# Lisa_CPU_Card_-_EasyEDA.net
KiCad netlist of a schematic drawn in EasyEDA
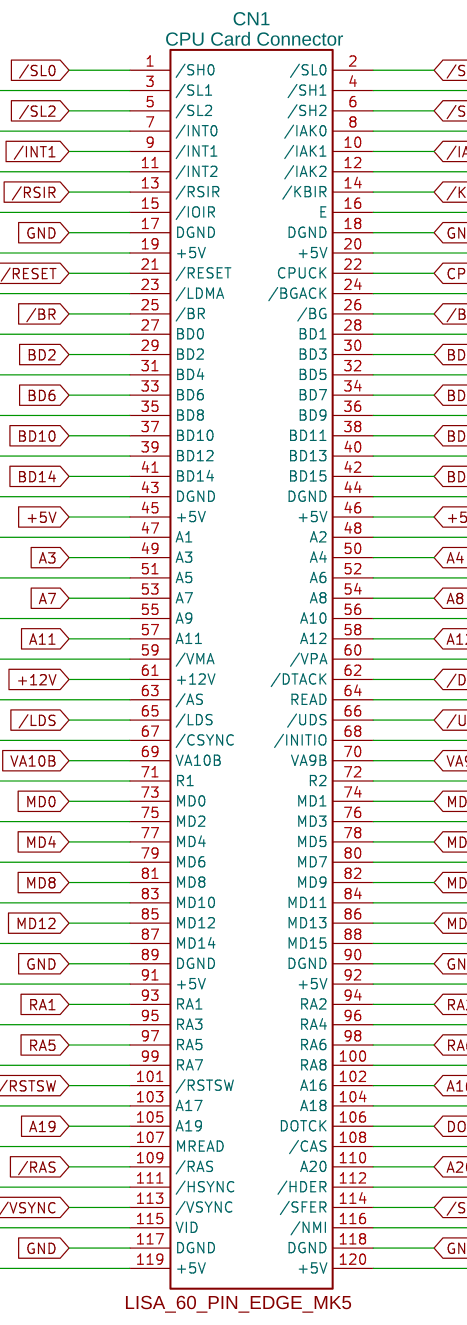
[diagram p0: CONNECTOR]
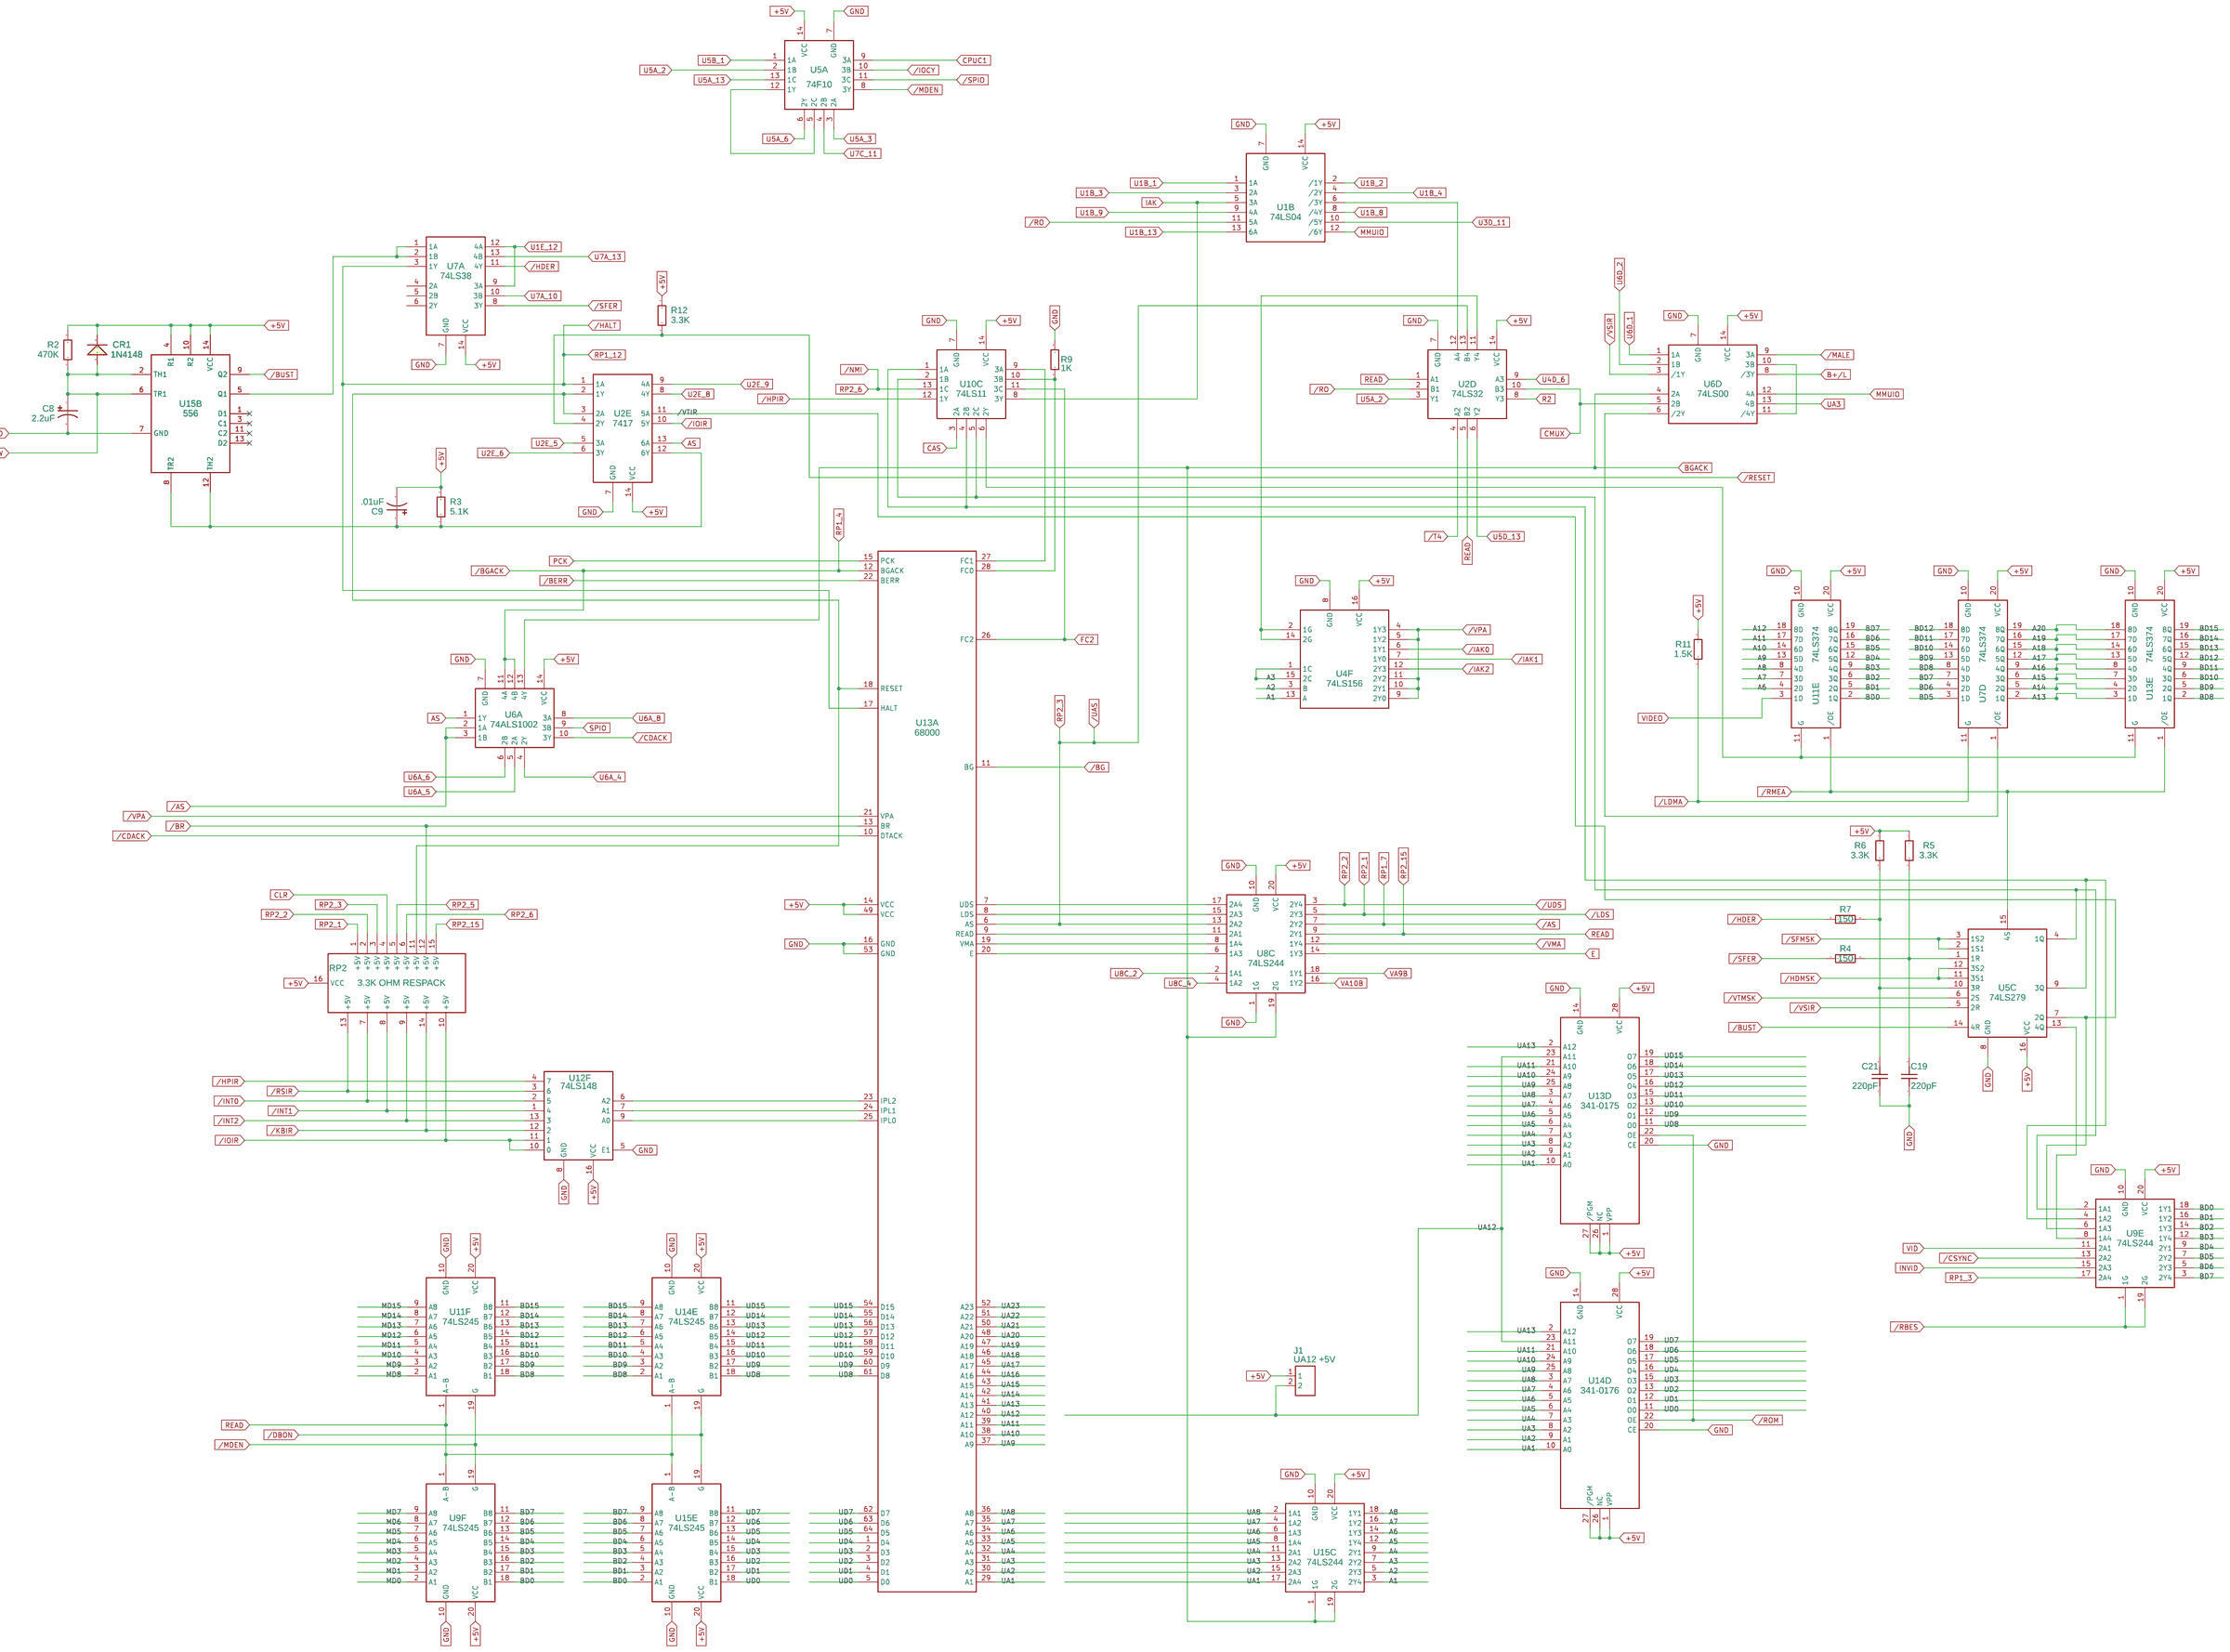
[diagram p1: CPU]
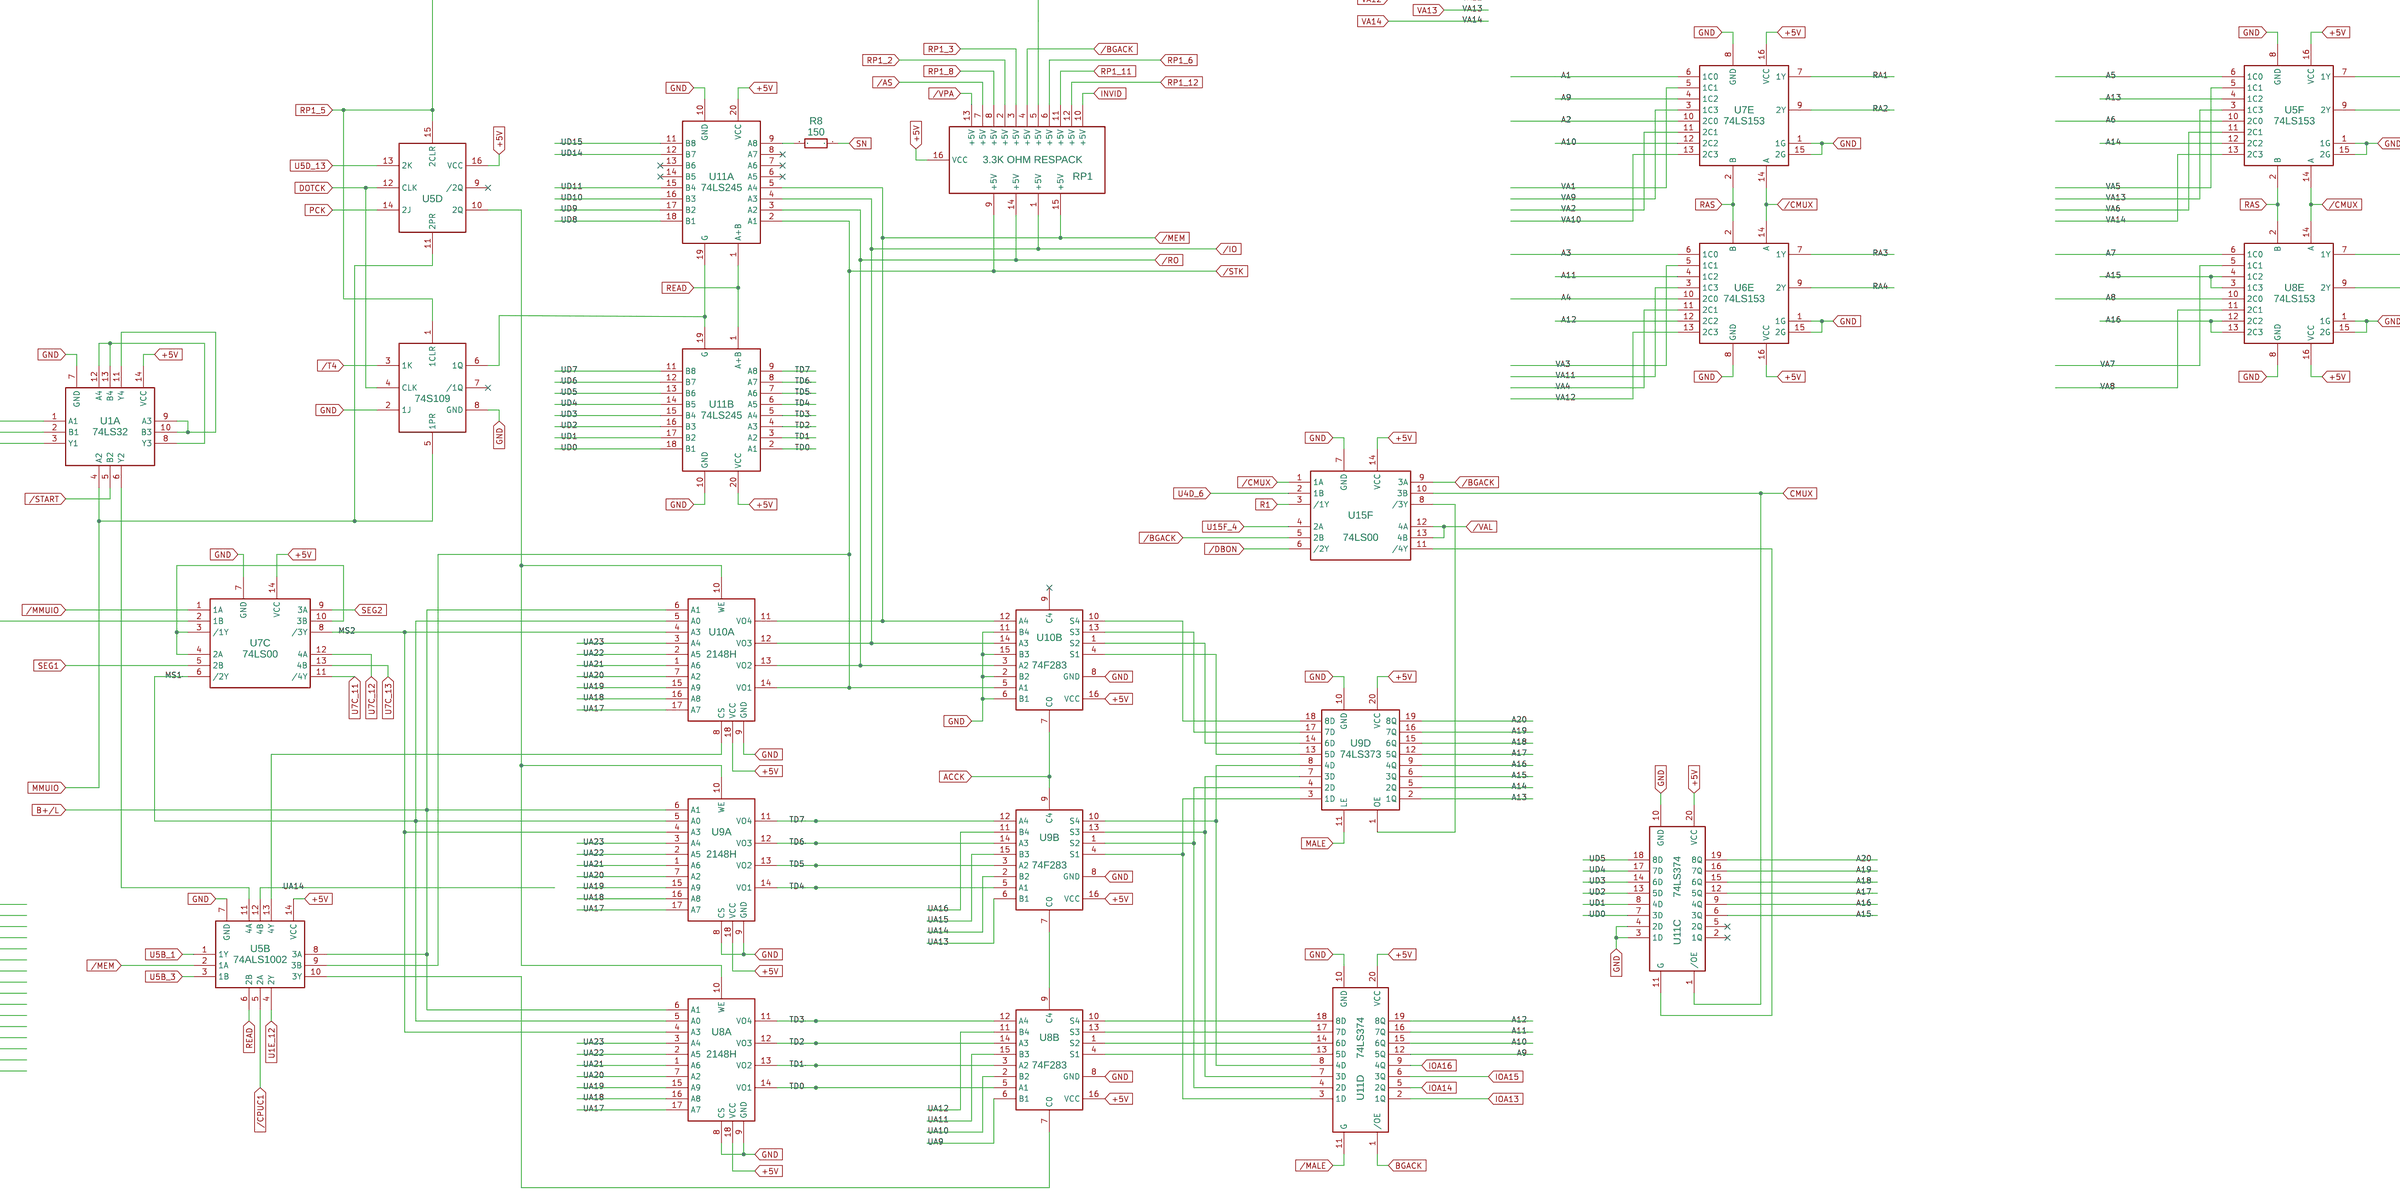
[diagram p2: MMU]
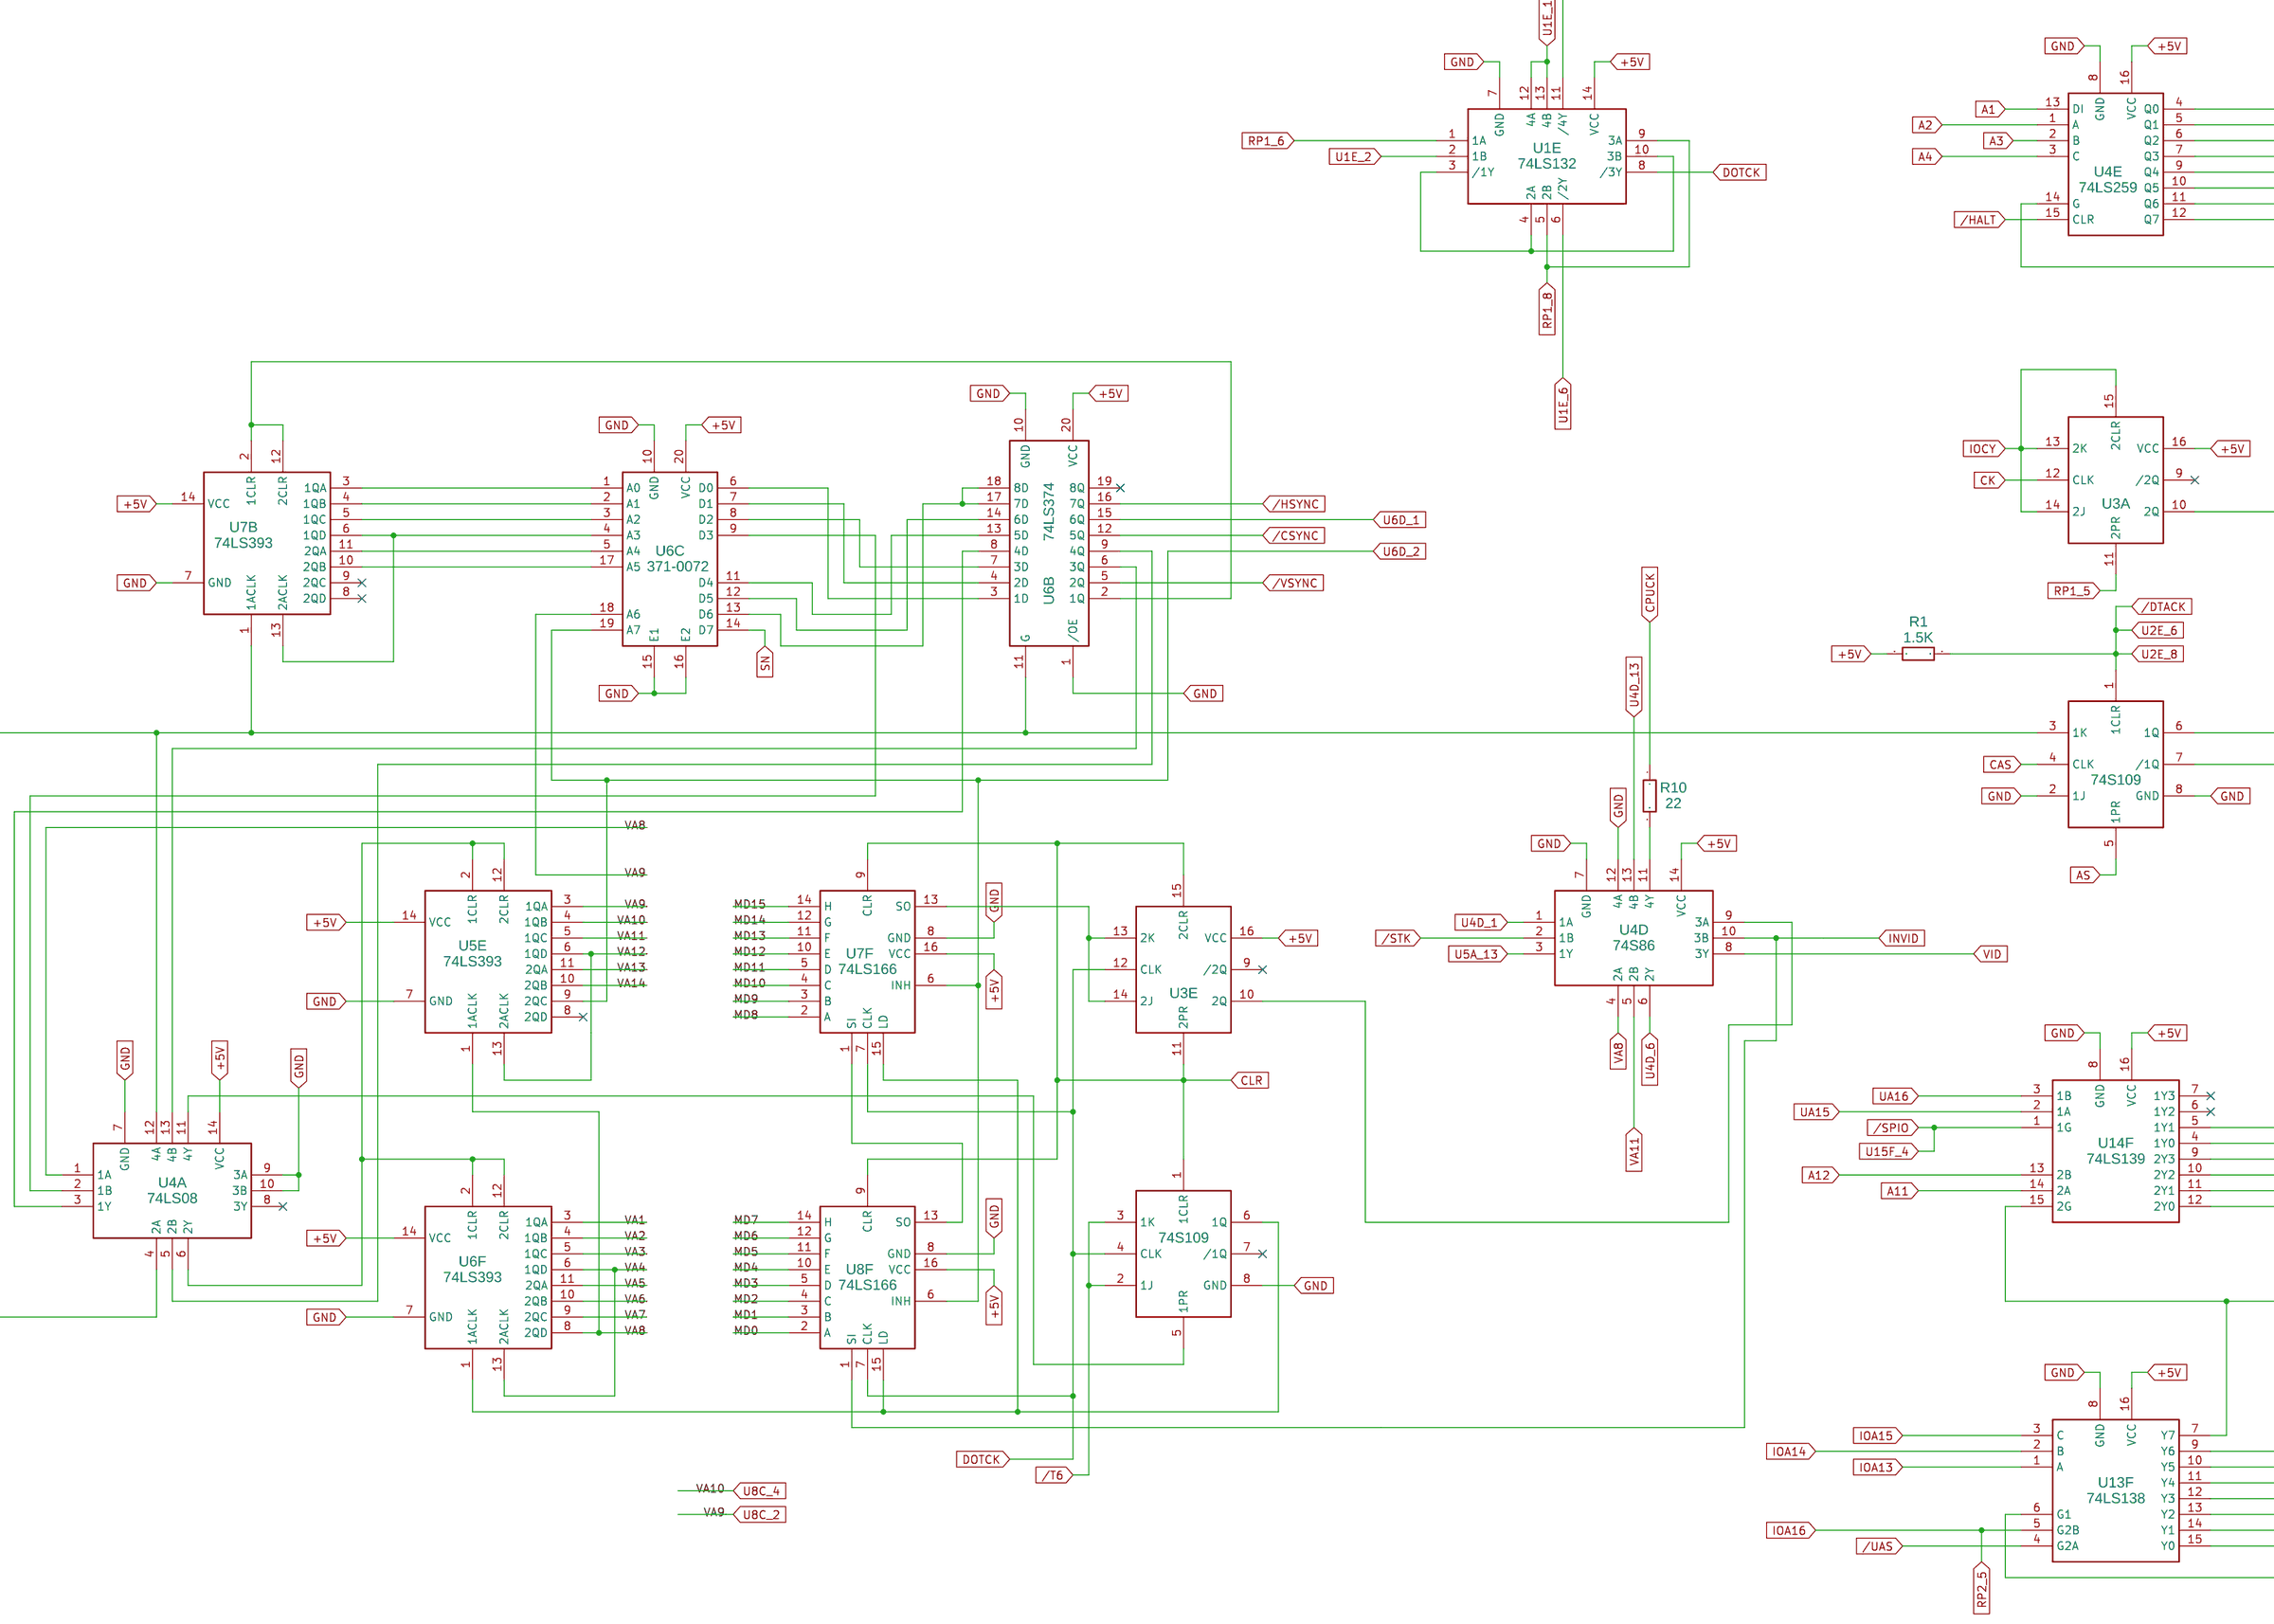
[diagram p3: VIDEO]
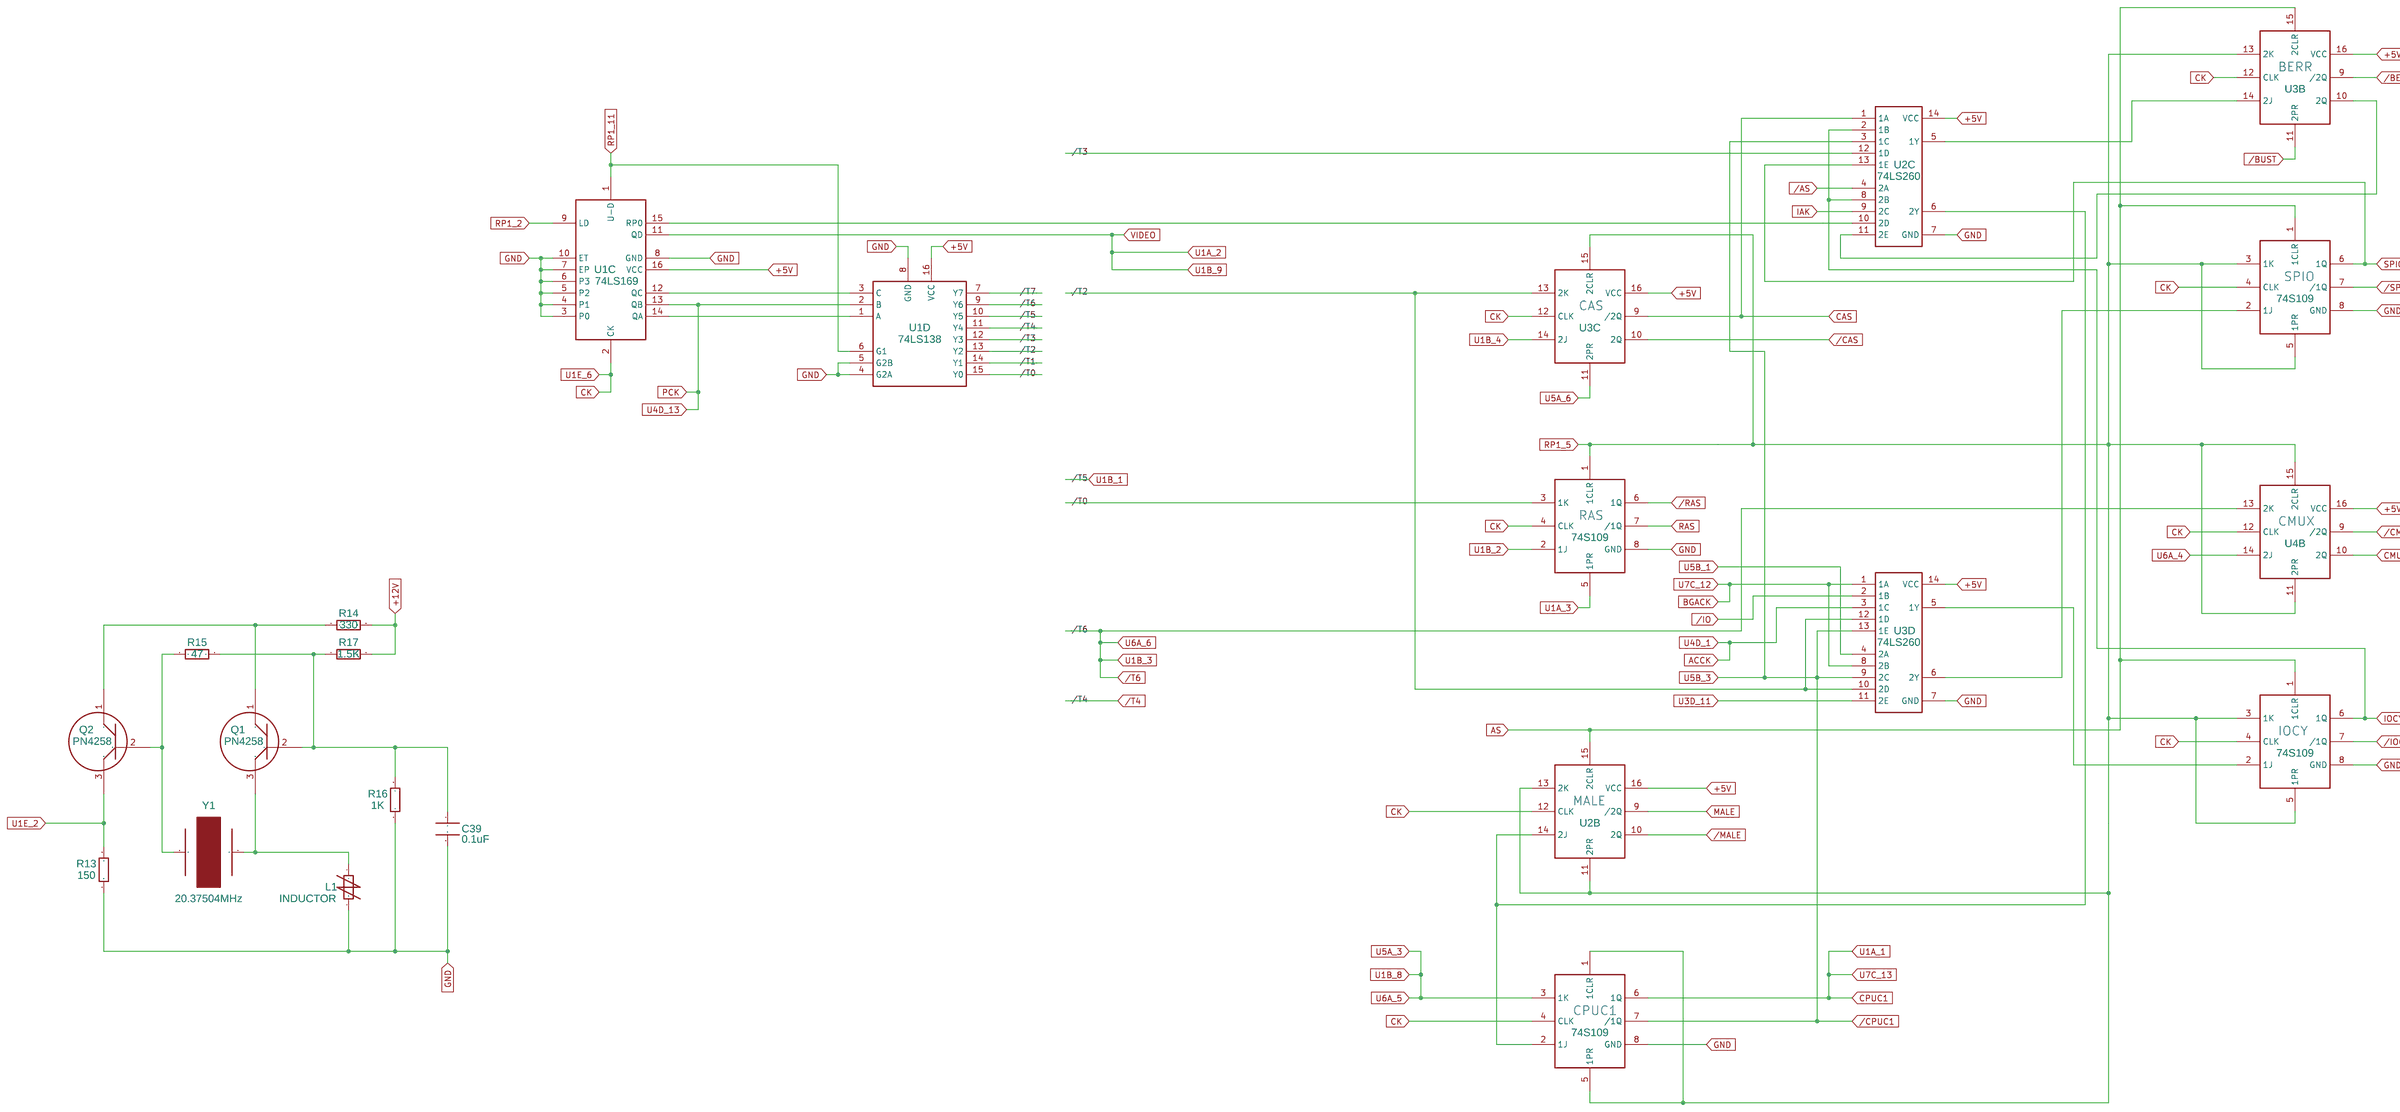
[diagram p4: CLOCK+IO]
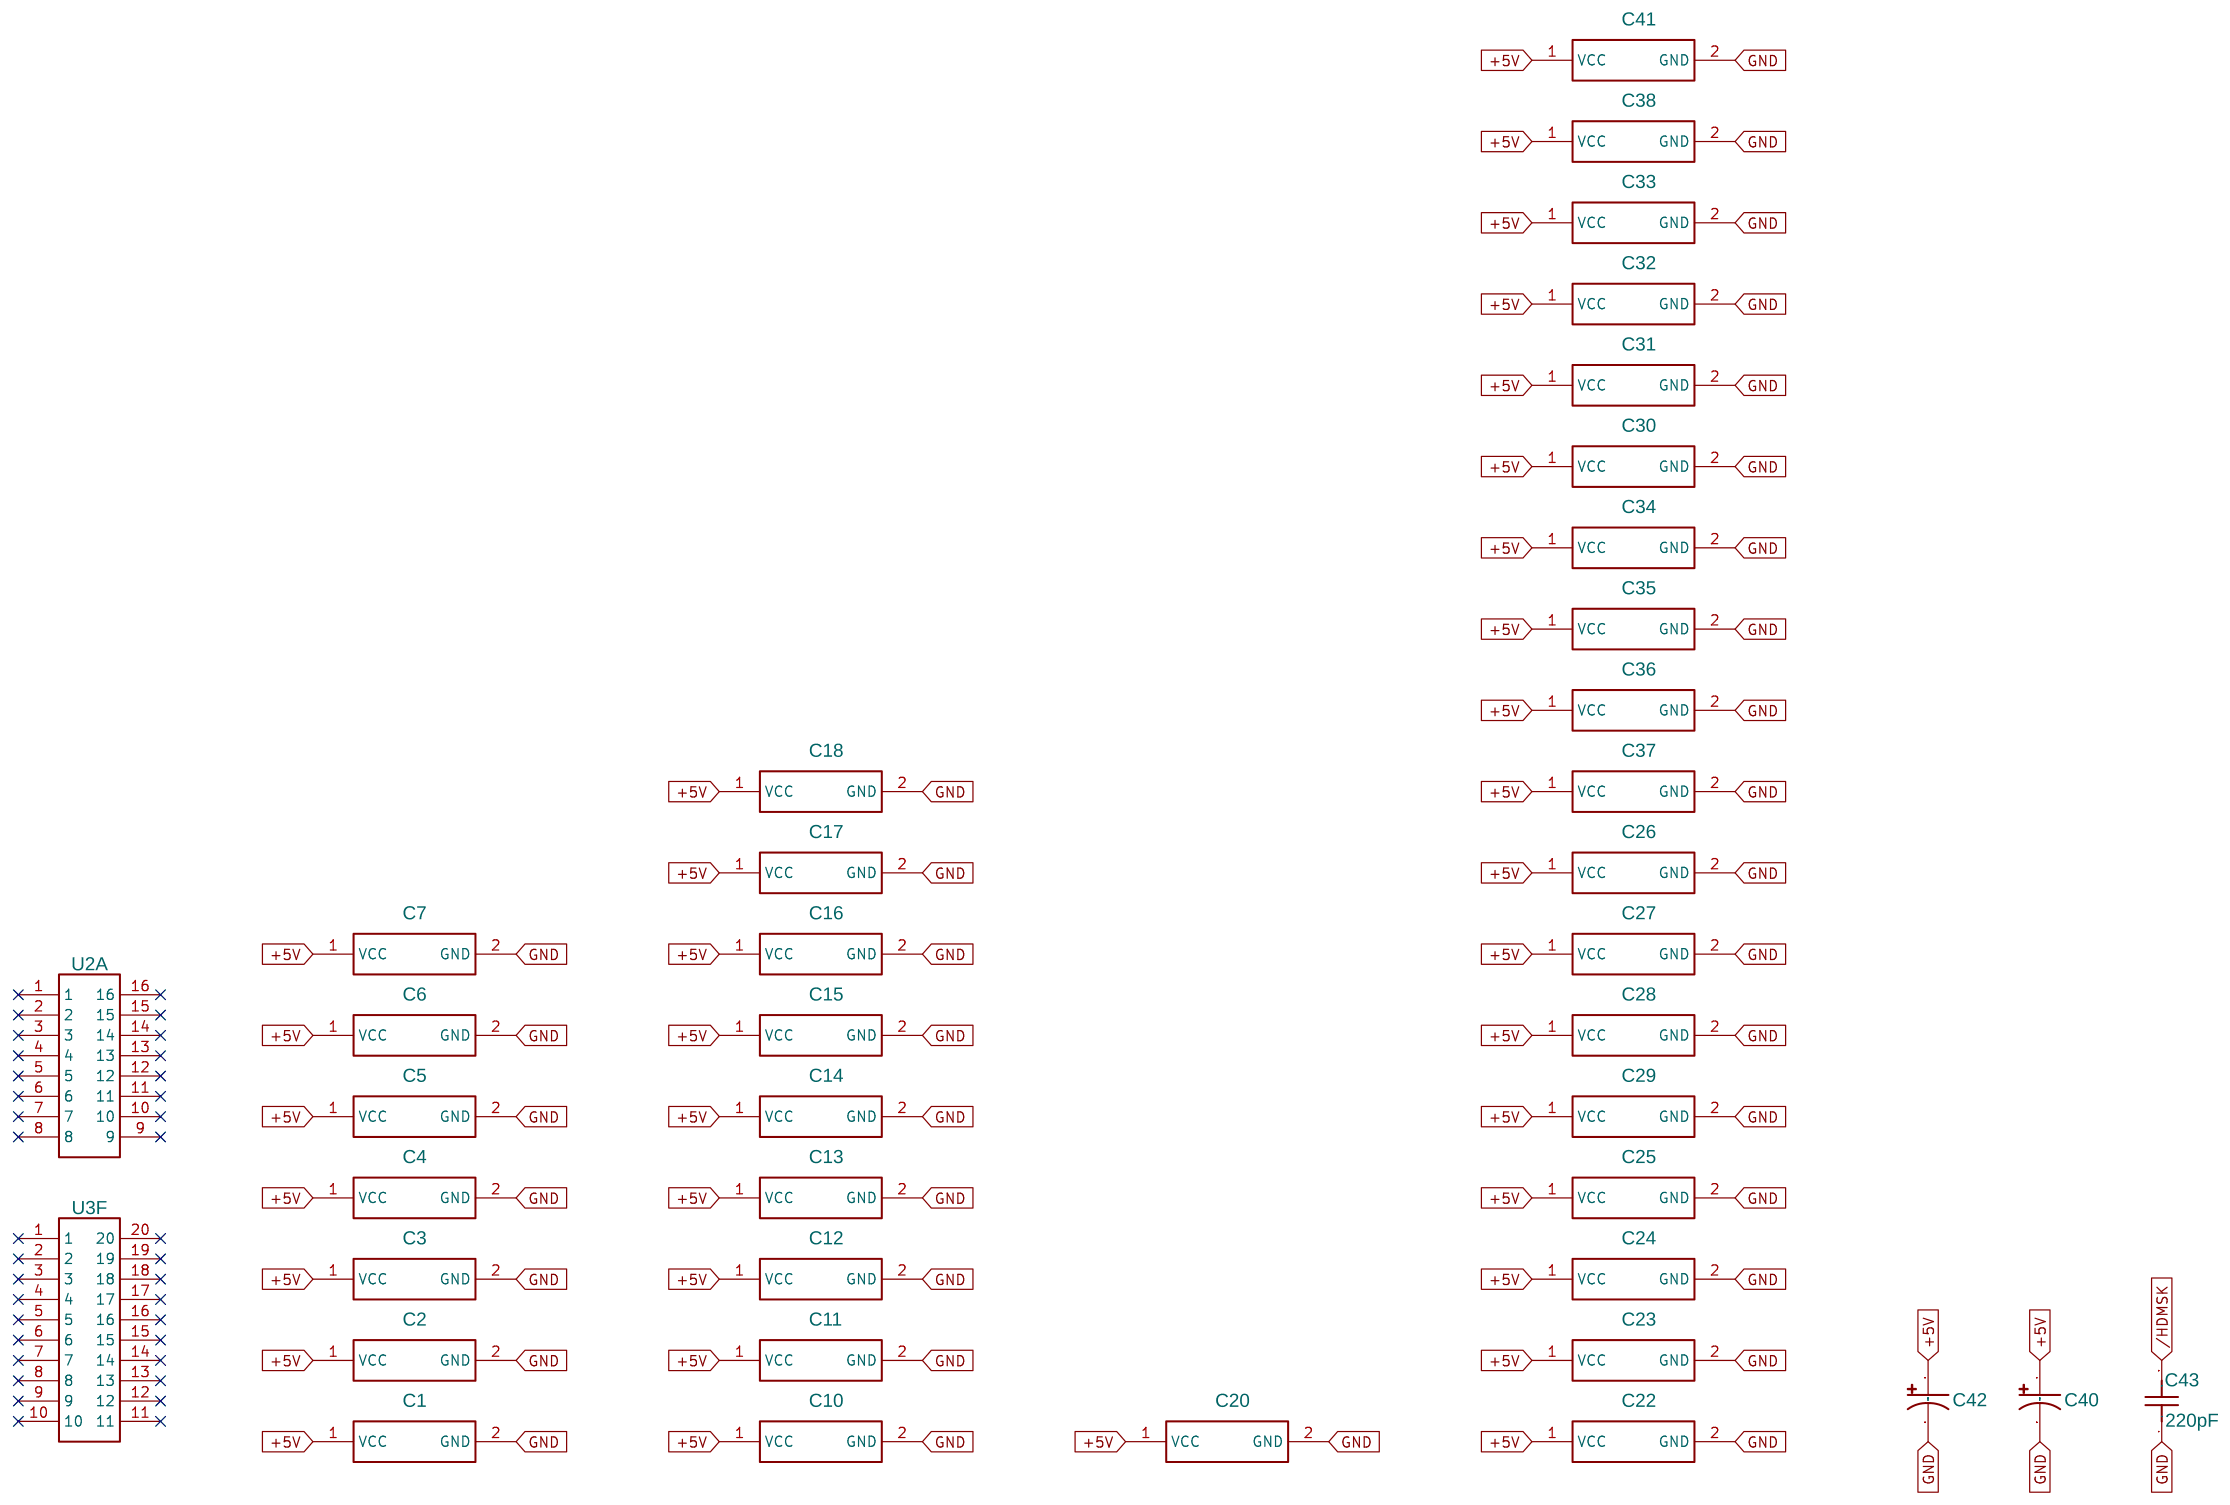
[diagram p5: MISC]

(export (version "E")
  (design (tool "Eeschema 10.0.6"))
  (components
    (comp (ref "CN1") (value "CPU Card Connector") (libsource (lib "") (part "Lisa CPU Connector")))
    (comp (ref "C8") (value "2.2uF") (libsource (lib "") (part "LISA_CPU_AXIAL_CAP_1")))
    (comp (ref "C9") (value ".01uF") (libsource (lib "") (part "LISA_CPU_AXIAL_CAP")))
    (comp (ref "C19") (value "220pF") (libsource (lib "") (part "LISA_CPU_CERAMIC_CAP")))
    (comp (ref "C21") (value "220pF") (libsource (lib "") (part "LISA_CPU_CERAMIC_CAP")))
    (comp (ref "CR1") (value "1N4148") (libsource (lib "") (part "LISA_CPU_DIODE")))
    (comp (ref "J1")
      (value "UA12 +5V")
      (fields (field (name "BOM_Manufacturer Part") "Jumper2") (field (name "BOM_Supplier Part") "C2940092"))
      (libsource (lib "") (part "JUMPER2"))
    )
    (comp (ref "R2") (value "470K") (libsource (lib "") (part "LISA_CPU_RESISTOR_1")))
    (comp (ref "R3") (value "5.1K") (libsource (lib "") (part "LISA_CPU_RESISTOR_1")))
    (comp (ref "R4") (value "150") (libsource (lib "") (part "LISA_CPU_RESISTOR_2")))
    (comp (ref "R5") (value "3.3K") (libsource (lib "") (part "LISA_CPU_RESISTOR")))
    (comp (ref "R6") (value "3.3K") (libsource (lib "") (part "LISA_CPU_RESISTOR")))
    (comp (ref "R7") (value "150") (libsource (lib "") (part "LISA_CPU_RESISTOR_2")))
    (comp (ref "R9") (value "1K") (libsource (lib "") (part "LISA_CPU_RESISTOR")))
    (comp (ref "R11") (value "1.5K") (libsource (lib "") (part "LISA_CPU_RESISTOR")))
    (comp (ref "R12") (value "3.3K") (libsource (lib "") (part "LISA_CPU_RESISTOR_1")))
    (comp (ref "RP2") (value "3.3K OHM RESPACK") (libsource (lib "") (part "LISA_CPU_RP2")))
    (comp (ref "U1B") (value "74LS04") (libsource (lib "") (part "LISA_CPU_74LS04")))
    (comp (ref "U2D") (value "74LS32") (libsource (lib "") (part "LISA_CPU_74LS32")))
    (comp (ref "U2E") (value "7417") (libsource (lib "") (part "LISA_CPU_7417")))
    (comp (ref "U4F") (value "74LS156") (libsource (lib "") (part "LISA_CPU_74LS156")))
    (comp (ref "U5A") (value "74F10") (libsource (lib "") (part "LISA_CPU_74F10")))
    (comp (ref "U5C") (value "74LS279") (libsource (lib "") (part "LISA_CPU_74LS279")))
    (comp (ref "U6A") (value "74ALS1002") (libsource (lib "") (part "LISA_CPU_74ALS1002")))
    (comp (ref "U6D") (value "74LS00") (libsource (lib "") (part "LISA_CPU_74LS00")))
    (comp (ref "U7A") (value "74LS38") (libsource (lib "") (part "LISA_CPU_74LS38")))
    (comp (ref "U7D") (value "74LS374") (libsource (lib "") (part "LISA_CPU_74LS374_1")))
    (comp (ref "U8C") (value "74LS244") (libsource (lib "") (part "LISA_CPU_74LS244_CTL")))
    (comp (ref "U9E") (value "74LS244") (libsource (lib "") (part "LISA_CPU_74LS244")))
    (comp (ref "U9F") (value "74LS245") (libsource (lib "") (part "LISA_CPU_74LS245_LOWER")))
    (comp (ref "U10C") (value "74LS11") (libsource (lib "") (part "LISA_CPU_74LS11")))
    (comp (ref "U11E") (value "74LS374") (libsource (lib "") (part "LISA_CPU_74LS374_2")))
    (comp (ref "U11F") (value "74LS245") (libsource (lib "") (part "LISA_CPU_74LS245_UPPER_1")))
    (comp (ref "U12F") (value "74LS148") (libsource (lib "") (part "LISA_CPU_74LS148")))
    (comp (ref "U13A") (value "68000") (libsource (lib "") (part "68000 (LISA)")))
    (comp (ref "U13D") (value "341-0175") (libsource (lib "") (part "LISA_CPU_EPROM")))
    (comp (ref "U13E") (value "74LS374") (libsource (lib "") (part "LISA_CPU_74LS374")))
    (comp (ref "U14D") (value "341-0176") (libsource (lib "") (part "LISA_CPU_EPROM_1")))
    (comp (ref "U14E") (value "74LS245") (libsource (lib "") (part "LISA_CPU_74LS245_UPPER")))
    (comp (ref "U15B") (value "556") (libsource (lib "") (part "LISA_CPU_556")))
    (comp (ref "U15C") (value "74LS244") (libsource (lib "") (part "LISA_CPU_74LS244_1")))
    (comp (ref "U15E") (value "74LS245") (libsource (lib "") (part "LISA_CPU_74LS245_LOWER_1")))
    (comp (ref "R8") (value "150") (libsource (lib "") (part "LISA_CPU_RESISTOR")))
    (comp (ref "RP1") (value "3.3K OHM RESPACK") (libsource (lib "") (part "LISA_CPU_RP1")))
    (comp (ref "U1A") (value "74LS32") (libsource (lib "") (part "LISA_CPU_74LS32")))
    (comp (ref "U5B") (value "74ALS1002") (libsource (lib "") (part "LISA_CPU_74ALS1002")))
    (comp (ref "U5D") (value "74S109") (libsource (lib "") (part "LISA_CPU_74S109")))
    (comp (ref "U5F") (value "74LS153") (libsource (lib "") (part "LISA_CPU_74LS153_UPPER")))
    (comp (ref "U6E") (value "74LS153") (libsource (lib "") (part "LISA_CPU_74LS153_LOWER_1")))
    (comp (ref "U7C") (value "74LS00") (libsource (lib "") (part "LISA_CPU_74LS00")))
    (comp (ref "U7E") (value "74LS153") (libsource (lib "") (part "LISA_CPU_74LS153_UPPER_1")))
    (comp (ref "U8A") (value "2148H") (libsource (lib "") (part "LISA_CPU_2148H")))
    (comp (ref "U8B") (value "74F283") (libsource (lib "") (part "LISA_CPU_74F283_1")))
    (comp (ref "U8E") (value "74LS153") (libsource (lib "") (part "LISA_CPU_74LS153_LOWER")))
    (comp (ref "U9A") (value "2148H") (libsource (lib "") (part "LISA_CPU_2148H_1")))
    (comp (ref "U9B") (value "74F283") (libsource (lib "") (part "LISA_CPU_74F283")))
    (comp (ref "U9D") (value "74LS373") (libsource (lib "") (part "LISA_CPU_74LS373")))
    (comp (ref "U10A") (value "2148H") (libsource (lib "") (part "LISA_CPU_2148H_2")))
    (comp (ref "U10B") (value "74F283") (libsource (lib "") (part "LISA_CPU_74F283_2")))
    (comp (ref "U11A") (value "74LS245") (libsource (lib "") (part "LISA_CPU_74LS245_U11A")))
    (comp (ref "U11B") (value "74LS245") (libsource (lib "") (part "LISA_CPU_74LS245_U11B")))
    (comp (ref "U11C") (value "74LS374") (libsource (lib "") (part "LISA_CPU_74LS374_1")))
    (comp (ref "U11D") (value "74LS374") (libsource (lib "") (part "LISA_CPU_74LS374")))
    (comp (ref "U15F") (value "74LS00") (libsource (lib "") (part "LISA_CPU_74LS00_1")))
    (comp (ref "R1") (value "1.5K") (libsource (lib "") (part "LISA_CPU_RESISTOR")))
    (comp (ref "R10") (value "22") (libsource (lib "") (part "LISA_CPU_RESISTOR_1")))
    (comp (ref "U1E") (value "74LS132") (libsource (lib "") (part "LISA_CPU_74LS132")))
    (comp (ref "U3A") (value "74S109") (libsource (lib "") (part "LISA_CPU_74S109_1")))
    (comp (ref "U3E") (value "74S109") (libsource (lib "") (part "LISA_CPU_74S109")))
    (comp (ref "U4A") (value "74LS08") (libsource (lib "") (part "LISA_CPU_74LS08")))
    (comp (ref "U4D") (value "74S86") (libsource (lib "") (part "LISA_CPU_74S86")))
    (comp (ref "U4E") (value "74LS259") (libsource (lib "") (part "LISA_CPU_74LS259")))
    (comp (ref "U5E") (value "74LS393") (libsource (lib "") (part "LISA_CPU_74LS393_2")))
    (comp (ref "U6B") (value "74LS374") (libsource (lib "") (part "LISA_CPU_74LS374")))
    (comp (ref "U6C") (value "371-0072") (libsource (lib "") (part "LISA_CPU_371-0072_VIDEO_ROM")))
    (comp (ref "U6F") (value "74LS393") (libsource (lib "") (part "LISA_CPU_74LS393_1")))
    (comp (ref "U7B") (value "74LS393") (libsource (lib "") (part "LISA_CPU_74LS393")))
    (comp (ref "U7F") (value "74LS166") (libsource (lib "") (part "LISA_CPU_74LS166_1")))
    (comp (ref "U8F") (value "74LS166") (libsource (lib "") (part "LISA_CPU_74LS166")))
    (comp (ref "U13F") (value "74LS138") (libsource (lib "") (part "LISA_CPU_74LS138")))
    (comp (ref "U14F") (value "74LS139") (libsource (lib "") (part "LISA_CPU_74LS139")))
    (comp (ref "C39") (value "0.1uF") (libsource (lib "") (part "LISA_CPU_GLASS_CAP")))
    (comp (ref "L1") (value "INDUCTOR") (libsource (lib "") (part "LISA_CPU_INDUCTOR")))
    (comp (ref "Q1") (value "PN4258") (libsource (lib "") (part "LISA_CPU_TRANSISTOR")))
    (comp (ref "Q2") (value "PN4258") (libsource (lib "") (part "LISA_CPU_TRANSISTOR")))
    (comp (ref "R13") (value "150") (libsource (lib "") (part "LISA_CPU_RESISTOR_1")))
    (comp (ref "R14") (value "330") (libsource (lib "") (part "LISA_CPU_RESISTOR")))
    (comp (ref "R15") (value "47") (libsource (lib "") (part "LISA_CPU_RESISTOR")))
    (comp (ref "R16") (value "1K") (libsource (lib "") (part "LISA_CPU_RESISTOR_1")))
    (comp (ref "R17") (value "1.5K") (libsource (lib "") (part "LISA_CPU_RESISTOR")))
    (comp (ref "U1C") (value "74LS169") (libsource (lib "") (part "LISA_CPU_74LS169")))
    (comp (ref "U1D") (value "74LS138") (libsource (lib "") (part "LISA_CPU_74LS138")))
    (comp (ref "U2B") (value "74S109") (libsource (lib "") (part "LISA_CPU_74S109_3")))
    (comp (ref "U2C") (value "74LS260") (libsource (lib "") (part "LISA_CPU_74LS260_1")))
    (comp (ref "U3B") (value "74S109") (libsource (lib "") (part "LISA_CPU_74S109_1")))
    (comp (ref "U3C") (value "74S109") (libsource (lib "") (part "LISA_CPU_74S109")))
    (comp (ref "U3D") (value "74LS260") (libsource (lib "") (part "LISA_CPU_74LS260")))
    (comp (ref "U4B") (value "74S109") (libsource (lib "") (part "LISA_CPU_74S109_2")))
    (comp (ref "Y1") (value "20.37504MHz") (libsource (lib "") (part "LISA_CPU_XTAL")))
    (comp (ref "C1")
      (value "LISA_CPU_DECOUPLER_CERAMIC_CAP")
      (libsource (lib "") (part "LISA_CPU_DECOUPLER_CERAMIC_CAP"))
    )
    (comp (ref "C2")
      (value "LISA_CPU_DECOUPLER_CERAMIC_CAP")
      (libsource (lib "") (part "LISA_CPU_DECOUPLER_CERAMIC_CAP"))
    )
    (comp (ref "C3")
      (value "LISA_CPU_DECOUPLER_CERAMIC_CAP")
      (libsource (lib "") (part "LISA_CPU_DECOUPLER_CERAMIC_CAP"))
    )
    (comp (ref "C4")
      (value "LISA_CPU_DECOUPLER_CERAMIC_CAP")
      (libsource (lib "") (part "LISA_CPU_DECOUPLER_CERAMIC_CAP"))
    )
    (comp (ref "C5")
      (value "LISA_CPU_DECOUPLER_CERAMIC_CAP")
      (libsource (lib "") (part "LISA_CPU_DECOUPLER_CERAMIC_CAP"))
    )
    (comp (ref "C6")
      (value "LISA_CPU_DECOUPLER_CERAMIC_CAP")
      (libsource (lib "") (part "LISA_CPU_DECOUPLER_CERAMIC_CAP"))
    )
    (comp (ref "C7")
      (value "LISA_CPU_DECOUPLER_CERAMIC_CAP")
      (libsource (lib "") (part "LISA_CPU_DECOUPLER_CERAMIC_CAP"))
    )
    (comp (ref "C10")
      (value "LISA_CPU_DECOUPLER_CERAMIC_CAP")
      (libsource (lib "") (part "LISA_CPU_DECOUPLER_CERAMIC_CAP"))
    )
    (comp (ref "C11")
      (value "LISA_CPU_DECOUPLER_CERAMIC_CAP")
      (libsource (lib "") (part "LISA_CPU_DECOUPLER_CERAMIC_CAP"))
    )
    (comp (ref "C12")
      (value "LISA_CPU_DECOUPLER_CERAMIC_CAP")
      (libsource (lib "") (part "LISA_CPU_DECOUPLER_CERAMIC_CAP"))
    )
    (comp (ref "C13")
      (value "LISA_CPU_DECOUPLER_CERAMIC_CAP")
      (libsource (lib "") (part "LISA_CPU_DECOUPLER_CERAMIC_CAP"))
    )
    (comp (ref "C14")
      (value "LISA_CPU_DECOUPLER_CERAMIC_CAP")
      (libsource (lib "") (part "LISA_CPU_DECOUPLER_CERAMIC_CAP"))
    )
    (comp (ref "C15")
      (value "LISA_CPU_DECOUPLER_CERAMIC_CAP")
      (libsource (lib "") (part "LISA_CPU_DECOUPLER_CERAMIC_CAP"))
    )
    (comp (ref "C16")
      (value "LISA_CPU_DECOUPLER_CERAMIC_CAP")
      (libsource (lib "") (part "LISA_CPU_DECOUPLER_CERAMIC_CAP"))
    )
    (comp (ref "C17")
      (value "LISA_CPU_DECOUPLER_CERAMIC_CAP")
      (libsource (lib "") (part "LISA_CPU_DECOUPLER_CERAMIC_CAP"))
    )
    (comp (ref "C18")
      (value "LISA_CPU_DECOUPLER_CERAMIC_CAP")
      (libsource (lib "") (part "LISA_CPU_DECOUPLER_CERAMIC_CAP"))
    )
    (comp (ref "C20")
      (value "LISA_CPU_DECOUPLER_CERAMIC_CAP")
      (libsource (lib "") (part "LISA_CPU_DECOUPLER_CERAMIC_CAP"))
    )
    (comp (ref "C22")
      (value "LISA_CPU_DECOUPLER_CERAMIC_CAP")
      (libsource (lib "") (part "LISA_CPU_DECOUPLER_CERAMIC_CAP"))
    )
    (comp (ref "C23")
      (value "LISA_CPU_DECOUPLER_CERAMIC_CAP")
      (libsource (lib "") (part "LISA_CPU_DECOUPLER_CERAMIC_CAP"))
    )
    (comp (ref "C24")
      (value "LISA_CPU_DECOUPLER_CERAMIC_CAP")
      (libsource (lib "") (part "LISA_CPU_DECOUPLER_CERAMIC_CAP"))
    )
    (comp (ref "C25")
      (value "LISA_CPU_DECOUPLER_CERAMIC_CAP")
      (libsource (lib "") (part "LISA_CPU_DECOUPLER_CERAMIC_CAP"))
    )
    (comp (ref "C26")
      (value "LISA_CPU_DECOUPLER_CERAMIC_CAP")
      (libsource (lib "") (part "LISA_CPU_DECOUPLER_CERAMIC_CAP"))
    )
    (comp (ref "C27")
      (value "LISA_CPU_DECOUPLER_CERAMIC_CAP")
      (libsource (lib "") (part "LISA_CPU_DECOUPLER_CERAMIC_CAP"))
    )
    (comp (ref "C28")
      (value "LISA_CPU_DECOUPLER_CERAMIC_CAP")
      (libsource (lib "") (part "LISA_CPU_DECOUPLER_CERAMIC_CAP"))
    )
    (comp (ref "C29")
      (value "LISA_CPU_DECOUPLER_CERAMIC_CAP")
      (libsource (lib "") (part "LISA_CPU_DECOUPLER_CERAMIC_CAP"))
    )
    (comp (ref "C30")
      (value "LISA_CPU_DECOUPLER_CERAMIC_CAP")
      (libsource (lib "") (part "LISA_CPU_DECOUPLER_CERAMIC_CAP"))
    )
    (comp (ref "C31")
      (value "LISA_CPU_DECOUPLER_CERAMIC_CAP")
      (libsource (lib "") (part "LISA_CPU_DECOUPLER_CERAMIC_CAP"))
    )
    (comp (ref "C32")
      (value "LISA_CPU_DECOUPLER_CERAMIC_CAP")
      (libsource (lib "") (part "LISA_CPU_DECOUPLER_CERAMIC_CAP"))
    )
    (comp (ref "C33")
      (value "LISA_CPU_DECOUPLER_CERAMIC_CAP")
      (libsource (lib "") (part "LISA_CPU_DECOUPLER_CERAMIC_CAP"))
    )
    (comp (ref "C34")
      (value "LISA_CPU_DECOUPLER_CERAMIC_CAP")
      (libsource (lib "") (part "LISA_CPU_DECOUPLER_CERAMIC_CAP"))
    )
    (comp (ref "C35")
      (value "LISA_CPU_DECOUPLER_CERAMIC_CAP")
      (libsource (lib "") (part "LISA_CPU_DECOUPLER_CERAMIC_CAP"))
    )
    (comp (ref "C36")
      (value "LISA_CPU_DECOUPLER_CERAMIC_CAP")
      (libsource (lib "") (part "LISA_CPU_DECOUPLER_CERAMIC_CAP"))
    )
    (comp (ref "C37")
      (value "LISA_CPU_DECOUPLER_CERAMIC_CAP")
      (libsource (lib "") (part "LISA_CPU_DECOUPLER_CERAMIC_CAP"))
    )
    (comp (ref "C38")
      (value "LISA_CPU_DECOUPLER_CERAMIC_CAP")
      (libsource (lib "") (part "LISA_CPU_DECOUPLER_CERAMIC_CAP"))
    )
    (comp (ref "C40") (value "LISA_CPU_AXIAL_CAP") (libsource (lib "") (part "LISA_CPU_AXIAL_CAP")))
    (comp (ref "C41")
      (value "LISA_CPU_DECOUPLER_CERAMIC_CAP")
      (libsource (lib "") (part "LISA_CPU_DECOUPLER_CERAMIC_CAP"))
    )
    (comp (ref "C42") (value "LISA_CPU_AXIAL_CAP") (libsource (lib "") (part "LISA_CPU_AXIAL_CAP")))
    (comp (ref "C43") (value "220pF") (libsource (lib "") (part "LISA_CPU_CERAMIC_CAP")))
    (comp (ref "U2A") (value "LISA_EMPTY_DIP_16") (libsource (lib "") (part "LISA_EMPTY_DIP_16")))
    (comp (ref "U3F") (value "LISA_EMPTY_DIP_20") (libsource (lib "") (part "LISA_EMPTY_DIP_20")))
  )
  (nets
    (net (code "1") (name "+5V") (class "Default")
      (node (ref "C1") (pin "1") (pinfunction "VCC_1") (pintype "unspecified"))
      (node (ref "C10") (pin "1") (pinfunction "VCC_1") (pintype "unspecified"))
      (node (ref "C11") (pin "1") (pinfunction "VCC_1") (pintype "unspecified"))
      (node (ref "C12") (pin "1") (pinfunction "VCC_1") (pintype "unspecified"))
      (node (ref "C13") (pin "1") (pinfunction "VCC_1") (pintype "unspecified"))
      (node (ref "C14") (pin "1") (pinfunction "VCC_1") (pintype "unspecified"))
      (node (ref "C15") (pin "1") (pinfunction "VCC_1") (pintype "unspecified"))
      (node (ref "C16") (pin "1") (pinfunction "VCC_1") (pintype "unspecified"))
      (node (ref "C17") (pin "1") (pinfunction "VCC_1") (pintype "unspecified"))
      (node (ref "C18") (pin "1") (pinfunction "VCC_1") (pintype "unspecified"))
      (node (ref "C2") (pin "1") (pinfunction "VCC_1") (pintype "unspecified"))
      (node (ref "C20") (pin "1") (pinfunction "VCC_1") (pintype "unspecified"))
      (node (ref "C22") (pin "1") (pinfunction "VCC_1") (pintype "unspecified"))
      (node (ref "C23") (pin "1") (pinfunction "VCC_1") (pintype "unspecified"))
      (node (ref "C24") (pin "1") (pinfunction "VCC_1") (pintype "unspecified"))
      (node (ref "C25") (pin "1") (pinfunction "VCC_1") (pintype "unspecified"))
      (node (ref "C26") (pin "1") (pinfunction "VCC_1") (pintype "unspecified"))
      (node (ref "C27") (pin "1") (pinfunction "VCC_1") (pintype "unspecified"))
      (node (ref "C28") (pin "1") (pinfunction "VCC_1") (pintype "unspecified"))
      (node (ref "C29") (pin "1") (pinfunction "VCC_1") (pintype "unspecified"))
      (node (ref "C3") (pin "1") (pinfunction "VCC_1") (pintype "unspecified"))
      (node (ref "C30") (pin "1") (pinfunction "VCC_1") (pintype "unspecified"))
      (node (ref "C31") (pin "1") (pinfunction "VCC_1") (pintype "unspecified"))
      (node (ref "C32") (pin "1") (pinfunction "VCC_1") (pintype "unspecified"))
      (node (ref "C33") (pin "1") (pinfunction "VCC_1") (pintype "unspecified"))
      (node (ref "C34") (pin "1") (pinfunction "VCC_1") (pintype "unspecified"))
      (node (ref "C35") (pin "1") (pinfunction "VCC_1") (pintype "unspecified"))
      (node (ref "C36") (pin "1") (pinfunction "VCC_1") (pintype "unspecified"))
      (node (ref "C37") (pin "1") (pinfunction "VCC_1") (pintype "unspecified"))
      (node (ref "C38") (pin "1") (pinfunction "VCC_1") (pintype "unspecified"))
      (node (ref "C4") (pin "1") (pinfunction "VCC_1") (pintype "unspecified"))
      (node (ref "C40") (pin "1") (pinfunction "1_1") (pintype "unspecified"))
      (node (ref "C41") (pin "1") (pinfunction "VCC_1") (pintype "unspecified"))
      (node (ref "C42") (pin "1") (pinfunction "1_1") (pintype "unspecified"))
      (node (ref "C5") (pin "1") (pinfunction "VCC_1") (pintype "unspecified"))
      (node (ref "C6") (pin "1") (pinfunction "VCC_1") (pintype "unspecified"))
      (node (ref "C7") (pin "1") (pinfunction "VCC_1") (pintype "unspecified"))
      (node (ref "C9") (pin "2") (pinfunction "2_2") (pintype "unspecified"))
      (node (ref "CN1") (pin "119") (pinfunction "+5V_119") (pintype "unspecified"))
      (node (ref "CN1") (pin "120") (pinfunction "+5V_120") (pintype "unspecified"))
      (node (ref "CN1") (pin "19") (pinfunction "+5V_19") (pintype "unspecified"))
      (node (ref "CN1") (pin "20") (pinfunction "+5V_20") (pintype "unspecified"))
      (node (ref "CN1") (pin "45") (pinfunction "+5V_45") (pintype "unspecified"))
      (node (ref "CN1") (pin "46") (pinfunction "+5V_46") (pintype "unspecified"))
      (node (ref "CN1") (pin "91") (pinfunction "+5V_91") (pintype "unspecified"))
      (node (ref "CN1") (pin "92") (pinfunction "+5V_92") (pintype "unspecified"))
      (node (ref "CR1") (pin "2") (pinfunction "2_2") (pintype "unspecified"))
      (node (ref "J1") (pin "1") (pinfunction "1_1") (pintype "unspecified"))
      (node (ref "R1") (pin "2") (pinfunction "2_2") (pintype "unspecified"))
      (node (ref "R11") (pin "1") (pinfunction "1_1") (pintype "unspecified"))
      (node (ref "R12") (pin "2") (pinfunction "2_2") (pintype "unspecified"))
      (node (ref "R2") (pin "2") (pinfunction "2_2") (pintype "unspecified"))
      (node (ref "R3") (pin "2") (pinfunction "2_2") (pintype "unspecified"))
      (node (ref "R5") (pin "1") (pinfunction "1_1") (pintype "unspecified"))
      (node (ref "R6") (pin "1") (pinfunction "1_1") (pintype "unspecified"))
      (node (ref "RP1") (pin "16") (pinfunction "VCC_16") (pintype "unspecified"))
      (node (ref "RP2") (pin "16") (pinfunction "VCC_16") (pintype "unspecified"))
      (node (ref "U10A") (pin "18") (pinfunction "VCC_18") (pintype "unspecified"))
      (node (ref "U10B") (pin "16") (pinfunction "VCC_16") (pintype "unspecified"))
      (node (ref "U10C") (pin "14") (pinfunction "VCC_14") (pintype "unspecified"))
      (node (ref "U11A") (pin "20") (pinfunction "VCC_20") (pintype "unspecified"))
      (node (ref "U11B") (pin "20") (pinfunction "VCC_20") (pintype "unspecified"))
      (node (ref "U11C") (pin "20") (pinfunction "VCC_20") (pintype "unspecified"))
      (node (ref "U11D") (pin "20") (pinfunction "VCC_20") (pintype "unspecified"))
      (node (ref "U11E") (pin "20") (pinfunction "VCC_20") (pintype "unspecified"))
      (node (ref "U11F") (pin "20") (pinfunction "VCC_20") (pintype "unspecified"))
      (node (ref "U12F") (pin "16") (pinfunction "VCC_16") (pintype "unspecified"))
      (node (ref "U13A") (pin "14") (pinfunction "VCC_14") (pintype "unspecified"))
      (node (ref "U13A") (pin "49") (pinfunction "VCC_49") (pintype "unspecified"))
      (node (ref "U13D") (pin "1") (pinfunction "VPP_1") (pintype "unspecified"))
      (node (ref "U13D") (pin "26") (pinfunction "NC_26") (pintype "unspecified"))
      (node (ref "U13D") (pin "27") (pinfunction "/PGM_27") (pintype "unspecified"))
      (node (ref "U13D") (pin "28") (pinfunction "VCC_28") (pintype "unspecified"))
      (node (ref "U13E") (pin "20") (pinfunction "VCC_20") (pintype "unspecified"))
      (node (ref "U13F") (pin "16") (pinfunction "VCC_16") (pintype "unspecified"))
      (node (ref "U14D") (pin "1") (pinfunction "VPP_1") (pintype "unspecified"))
      (node (ref "U14D") (pin "26") (pinfunction "NC_26") (pintype "unspecified"))
      (node (ref "U14D") (pin "27") (pinfunction "/PGM_27") (pintype "unspecified"))
      (node (ref "U14D") (pin "28") (pinfunction "VCC_28") (pintype "unspecified"))
      (node (ref "U14E") (pin "20") (pinfunction "VCC_20") (pintype "unspecified"))
      (node (ref "U14F") (pin "16") (pinfunction "VCC_16") (pintype "unspecified"))
      (node (ref "U15B") (pin "10") (pinfunction "R2_10") (pintype "unspecified"))
      (node (ref "U15B") (pin "14") (pinfunction "VCC_14") (pintype "unspecified"))
      (node (ref "U15B") (pin "4") (pinfunction "R1_4") (pintype "unspecified"))
      (node (ref "U15C") (pin "20") (pinfunction "VCC_20") (pintype "unspecified"))
      (node (ref "U15E") (pin "20") (pinfunction "VCC_20") (pintype "unspecified"))
      (node (ref "U15F") (pin "14") (pinfunction "VCC_14") (pintype "unspecified"))
      (node (ref "U1A") (pin "14") (pinfunction "VCC_14") (pintype "unspecified"))
      (node (ref "U1B") (pin "14") (pinfunction "VCC_14") (pintype "unspecified"))
      (node (ref "U1C") (pin "16") (pinfunction "VCC_16") (pintype "unspecified"))
      (node (ref "U1D") (pin "16") (pinfunction "VCC_16") (pintype "unspecified"))
      (node (ref "U1E") (pin "14") (pinfunction "VCC_14") (pintype "unspecified"))
      (node (ref "U2B") (pin "16") (pinfunction "VCC_16") (pintype "unspecified"))
      (node (ref "U2C") (pin "14") (pinfunction "VCC_14") (pintype "unspecified"))
      (node (ref "U2D") (pin "14") (pinfunction "VCC_14") (pintype "unspecified"))
      (node (ref "U2E") (pin "14") (pinfunction "VCC_14") (pintype "unspecified"))
      (node (ref "U3A") (pin "16") (pinfunction "VCC_16") (pintype "unspecified"))
      (node (ref "U3B") (pin "16") (pinfunction "VCC_16") (pintype "unspecified"))
      (node (ref "U3C") (pin "16") (pinfunction "VCC_16") (pintype "unspecified"))
      (node (ref "U3D") (pin "14") (pinfunction "VCC_14") (pintype "unspecified"))
      (node (ref "U3E") (pin "16") (pinfunction "VCC_16") (pintype "unspecified"))
      (node (ref "U4A") (pin "14") (pinfunction "VCC_14") (pintype "unspecified"))
      (node (ref "U4B") (pin "16") (pinfunction "VCC_16") (pintype "unspecified"))
      (node (ref "U4D") (pin "14") (pinfunction "VCC_14") (pintype "unspecified"))
      (node (ref "U4E") (pin "16") (pinfunction "VCC_16") (pintype "unspecified"))
      (node (ref "U4F") (pin "16") (pinfunction "VCC_16") (pintype "unspecified"))
      (node (ref "U5A") (pin "14") (pinfunction "VCC_14") (pintype "unspecified"))
      (node (ref "U5B") (pin "14") (pinfunction "VCC_14") (pintype "unspecified"))
      (node (ref "U5C") (pin "16") (pinfunction "VCC_16") (pintype "unspecified"))
      (node (ref "U5D") (pin "16") (pinfunction "VCC_16") (pintype "unspecified"))
      (node (ref "U5E") (pin "14") (pinfunction "VCC_14") (pintype "unspecified"))
      (node (ref "U5F") (pin "16") (pinfunction "VCC_16") (pintype "unspecified"))
      (node (ref "U6A") (pin "14") (pinfunction "VCC_14") (pintype "unspecified"))
      (node (ref "U6B") (pin "20") (pinfunction "VCC_20") (pintype "unspecified"))
      (node (ref "U6C") (pin "20") (pinfunction "VCC_20") (pintype "unspecified"))
      (node (ref "U6D") (pin "14") (pinfunction "VCC_14") (pintype "unspecified"))
      (node (ref "U6E") (pin "16") (pinfunction "VCC_16") (pintype "unspecified"))
      (node (ref "U6F") (pin "14") (pinfunction "VCC_14") (pintype "unspecified"))
      (node (ref "U7A") (pin "14") (pinfunction "VCC_14") (pintype "unspecified"))
      (node (ref "U7B") (pin "14") (pinfunction "VCC_14") (pintype "unspecified"))
      (node (ref "U7C") (pin "14") (pinfunction "VCC_14") (pintype "unspecified"))
      (node (ref "U7D") (pin "20") (pinfunction "VCC_20") (pintype "unspecified"))
      (node (ref "U7E") (pin "16") (pinfunction "VCC_16") (pintype "unspecified"))
      (node (ref "U7F") (pin "16") (pinfunction "VCC_16") (pintype "unspecified"))
      (node (ref "U8A") (pin "18") (pinfunction "VCC_18") (pintype "unspecified"))
      (node (ref "U8B") (pin "16") (pinfunction "VCC_16") (pintype "unspecified"))
      (node (ref "U8C") (pin "20") (pinfunction "VCC_20") (pintype "unspecified"))
      (node (ref "U8E") (pin "16") (pinfunction "VCC_16") (pintype "unspecified"))
      (node (ref "U8F") (pin "16") (pinfunction "VCC_16") (pintype "unspecified"))
      (node (ref "U9A") (pin "18") (pinfunction "VCC_18") (pintype "unspecified"))
      (node (ref "U9B") (pin "16") (pinfunction "VCC_16") (pintype "unspecified"))
      (node (ref "U9D") (pin "20") (pinfunction "VCC_20") (pintype "unspecified"))
      (node (ref "U9E") (pin "20") (pinfunction "VCC_20") (pintype "unspecified"))
      (node (ref "U9F") (pin "20") (pinfunction "VCC_20") (pintype "unspecified"))
    )
    (net (code "2") (name "+12V") (class "Default")
      (node (ref "CN1") (pin "61") (pinfunction "+12V_61") (pintype "unspecified"))
      (node (ref "R14") (pin "2") (pinfunction "2_2") (pintype "unspecified"))
      (node (ref "R17") (pin "2") (pinfunction "2_2") (pintype "unspecified"))
    )
    (net (code "3") (name "A1") (class "Default")
      (node (ref "CN1") (pin "47") (pinfunction "A1_47") (pintype "unspecified"))
      (node (ref "U15C") (pin "3") (pinfunction "2Y4_3") (pintype "unspecified"))
      (node (ref "U4E") (pin "13") (pinfunction "DI_13") (pintype "unspecified"))
      (node (ref "U4F") (pin "13") (pinfunction "A_13") (pintype "unspecified"))
      (node (ref "U7E") (pin "6") (pinfunction "1C0_6") (pintype "unspecified"))
    )
    (net (code "4") (name "A2") (class "Default")
      (node (ref "CN1") (pin "48") (pinfunction "A2_48") (pintype "unspecified"))
      (node (ref "U15C") (pin "5") (pinfunction "2Y3_5") (pintype "unspecified"))
      (node (ref "U4E") (pin "1") (pinfunction "A_1") (pintype "unspecified"))
      (node (ref "U4F") (pin "3") (pinfunction "B_3") (pintype "unspecified"))
      (node (ref "U7E") (pin "10") (pinfunction "2C0_10") (pintype "unspecified"))
    )
    (net (code "5") (name "A3") (class "Default")
      (node (ref "CN1") (pin "49") (pinfunction "A3_49") (pintype "unspecified"))
      (node (ref "U15C") (pin "7") (pinfunction "2Y2_7") (pintype "unspecified"))
      (node (ref "U4E") (pin "2") (pinfunction "B_2") (pintype "unspecified"))
      (node (ref "U4F") (pin "1") (pinfunction "1C_1") (pintype "unspecified"))
      (node (ref "U4F") (pin "15") (pinfunction "2C_15") (pintype "unspecified"))
      (node (ref "U6E") (pin "6") (pinfunction "1C0_6") (pintype "unspecified"))
    )
    (net (code "6") (name "A4") (class "Default")
      (node (ref "CN1") (pin "50") (pinfunction "A4_50") (pintype "unspecified"))
      (node (ref "U15C") (pin "9") (pinfunction "2Y1_9") (pintype "unspecified"))
      (node (ref "U4E") (pin "3") (pinfunction "C_3") (pintype "unspecified"))
      (node (ref "U6E") (pin "10") (pinfunction "2C0_10") (pintype "unspecified"))
    )
    (net (code "7") (name "A5") (class "Default")
      (node (ref "CN1") (pin "51") (pinfunction "A5_51") (pintype "unspecified"))
      (node (ref "U15C") (pin "12") (pinfunction "1Y4_12") (pintype "unspecified"))
      (node (ref "U5F") (pin "6") (pinfunction "1C0_6") (pintype "unspecified"))
    )
    (net (code "8") (name "A6") (class "Default")
      (node (ref "CN1") (pin "52") (pinfunction "A6_52") (pintype "unspecified"))
      (node (ref "U11E") (pin "4") (pinfunction "2D_4") (pintype "unspecified"))
      (node (ref "U15C") (pin "14") (pinfunction "1Y3_14") (pintype "unspecified"))
      (node (ref "U5F") (pin "10") (pinfunction "2C0_10") (pintype "unspecified"))
    )
    (net (code "9") (name "A7") (class "Default")
      (node (ref "CN1") (pin "53") (pinfunction "A7_53") (pintype "unspecified"))
      (node (ref "U11E") (pin "7") (pinfunction "3D_7") (pintype "unspecified"))
      (node (ref "U15C") (pin "16") (pinfunction "1Y2_16") (pintype "unspecified"))
      (node (ref "U8E") (pin "6") (pinfunction "1C0_6") (pintype "unspecified"))
    )
    (net (code "10") (name "A8") (class "Default")
      (node (ref "CN1") (pin "54") (pinfunction "A8_54") (pintype "unspecified"))
      (node (ref "U11E") (pin "8") (pinfunction "4D_8") (pintype "unspecified"))
      (node (ref "U15C") (pin "18") (pinfunction "1Y1_18") (pintype "unspecified"))
      (node (ref "U8E") (pin "10") (pinfunction "2C0_10") (pintype "unspecified"))
    )
    (net (code "11") (name "A9") (class "Default")
      (node (ref "CN1") (pin "55") (pinfunction "A9_55") (pintype "unspecified"))
      (node (ref "U11D") (pin "12") (pinfunction "5Q_12") (pintype "unspecified"))
      (node (ref "U11E") (pin "13") (pinfunction "5D_13") (pintype "unspecified"))
      (node (ref "U7E") (pin "4") (pinfunction "1C2_4") (pintype "unspecified"))
    )
    (net (code "12") (name "A10") (class "Default")
      (node (ref "CN1") (pin "56") (pinfunction "A10_56") (pintype "unspecified"))
      (node (ref "U11D") (pin "15") (pinfunction "6Q_15") (pintype "unspecified"))
      (node (ref "U11E") (pin "14") (pinfunction "6D_14") (pintype "unspecified"))
      (node (ref "U7E") (pin "12") (pinfunction "2C2_12") (pintype "unspecified"))
    )
    (net (code "13") (name "A11") (class "Default")
      (node (ref "CN1") (pin "57") (pinfunction "A11_57") (pintype "unspecified"))
      (node (ref "U11D") (pin "16") (pinfunction "7Q_16") (pintype "unspecified"))
      (node (ref "U11E") (pin "17") (pinfunction "7D_17") (pintype "unspecified"))
      (node (ref "U14F") (pin "14") (pinfunction "2A_14") (pintype "unspecified"))
      (node (ref "U6E") (pin "4") (pinfunction "1C2_4") (pintype "unspecified"))
    )
    (net (code "14") (name "A12") (class "Default")
      (node (ref "CN1") (pin "58") (pinfunction "A12_58") (pintype "unspecified"))
      (node (ref "U11D") (pin "19") (pinfunction "8Q_19") (pintype "unspecified"))
      (node (ref "U11E") (pin "18") (pinfunction "8D_18") (pintype "unspecified"))
      (node (ref "U14F") (pin "13") (pinfunction "2B_13") (pintype "unspecified"))
      (node (ref "U6E") (pin "12") (pinfunction "2C2_12") (pintype "unspecified"))
    )
    (net (code "15") (name "A13") (class "Default")
      (node (ref "U13E") (pin "3") (pinfunction "1D_3") (pintype "unspecified"))
      (node (ref "U5F") (pin "4") (pinfunction "1C2_4") (pintype "unspecified"))
      (node (ref "U7D") (pin "2") (pinfunction "1Q_2") (pintype "unspecified"))
      (node (ref "U9D") (pin "2") (pinfunction "1Q_2") (pintype "unspecified"))
    )
    (net (code "16") (name "A14") (class "Default")
      (node (ref "U13E") (pin "4") (pinfunction "2D_4") (pintype "unspecified"))
      (node (ref "U5F") (pin "12") (pinfunction "2C2_12") (pintype "unspecified"))
      (node (ref "U7D") (pin "5") (pinfunction "2Q_5") (pintype "unspecified"))
      (node (ref "U9D") (pin "5") (pinfunction "2Q_5") (pintype "unspecified"))
    )
    (net (code "17") (name "A15") (class "Default")
      (node (ref "U11C") (pin "6") (pinfunction "3Q_6") (pintype "unspecified"))
      (node (ref "U13E") (pin "7") (pinfunction "3D_7") (pintype "unspecified"))
      (node (ref "U7D") (pin "6") (pinfunction "3Q_6") (pintype "unspecified"))
      (node (ref "U8E") (pin "3") (pinfunction "1C3_3") (pintype "unspecified"))
      (node (ref "U8E") (pin "4") (pinfunction "1C2_4") (pintype "unspecified"))
      (node (ref "U9D") (pin "6") (pinfunction "3Q_6") (pintype "unspecified"))
    )
    (net (code "18") (name "A16") (class "Default")
      (node (ref "CN1") (pin "102") (pinfunction "A16_102") (pintype "unspecified"))
      (node (ref "U11C") (pin "9") (pinfunction "4Q_9") (pintype "unspecified"))
      (node (ref "U13E") (pin "8") (pinfunction "4D_8") (pintype "unspecified"))
      (node (ref "U7D") (pin "9") (pinfunction "4Q_9") (pintype "unspecified"))
      (node (ref "U8E") (pin "12") (pinfunction "2C2_12") (pintype "unspecified"))
      (node (ref "U8E") (pin "13") (pinfunction "2C3_13") (pintype "unspecified"))
      (node (ref "U9D") (pin "9") (pinfunction "4Q_9") (pintype "unspecified"))
    )
    (net (code "19") (name "A17") (class "Default")
      (node (ref "CN1") (pin "103") (pinfunction "A17_103") (pintype "unspecified"))
      (node (ref "U11C") (pin "12") (pinfunction "5Q_12") (pintype "unspecified"))
      (node (ref "U13E") (pin "13") (pinfunction "5D_13") (pintype "unspecified"))
      (node (ref "U7D") (pin "12") (pinfunction "5Q_12") (pintype "unspecified"))
      (node (ref "U9D") (pin "12") (pinfunction "5Q_12") (pintype "unspecified"))
    )
    (net (code "20") (name "A18") (class "Default")
      (node (ref "CN1") (pin "104") (pinfunction "A18_104") (pintype "unspecified"))
      (node (ref "U11C") (pin "15") (pinfunction "6Q_15") (pintype "unspecified"))
      (node (ref "U13E") (pin "14") (pinfunction "6D_14") (pintype "unspecified"))
      (node (ref "U7D") (pin "15") (pinfunction "6Q_15") (pintype "unspecified"))
      (node (ref "U9D") (pin "15") (pinfunction "6Q_15") (pintype "unspecified"))
    )
    (net (code "21") (name "A19") (class "Default")
      (node (ref "CN1") (pin "105") (pinfunction "A19_105") (pintype "unspecified"))
      (node (ref "U11C") (pin "16") (pinfunction "7Q_16") (pintype "unspecified"))
      (node (ref "U13E") (pin "17") (pinfunction "7D_17") (pintype "unspecified"))
      (node (ref "U7D") (pin "16") (pinfunction "7Q_16") (pintype "unspecified"))
      (node (ref "U9D") (pin "16") (pinfunction "7Q_16") (pintype "unspecified"))
    )
    (net (code "22") (name "A20") (class "Default")
      (node (ref "CN1") (pin "110") (pinfunction "A20_110") (pintype "unspecified"))
      (node (ref "U11C") (pin "19") (pinfunction "8Q_19") (pintype "unspecified"))
      (node (ref "U13E") (pin "18") (pinfunction "8D_18") (pintype "unspecified"))
      (node (ref "U7D") (pin "19") (pinfunction "8Q_19") (pintype "unspecified"))
      (node (ref "U9D") (pin "19") (pinfunction "8Q_19") (pintype "unspecified"))
    )
    (net (code "23") (name "ACCK") (class "Default")
      (node (ref "U10B") (pin "7") (pinfunction "C0_7") (pintype "unspecified"))
      (node (ref "U3D") (pin "3") (pinfunction "1C_3") (pintype "unspecified"))
      (node (ref "U4D") (pin "1") (pinfunction "1A_1") (pintype "unspecified"))
      (node (ref "U9B") (pin "9") (pinfunction "C4_9") (pintype "unspecified"))
    )
    (net (code "24") (name "AS") (class "Default")
      (node (ref "U2B") (pin "15") (pinfunction "2CLR_15") (pintype "unspecified"))
      (node (ref "U2E") (pin "13") (pinfunction "6A_13") (pintype "unspecified"))
      (node (ref "U3A") (pin "5") (pinfunction "1PR_5") (pintype "unspecified"))
      (node (ref "U3B") (pin "1") (pinfunction "1CLR_1") (pintype "unspecified"))
      (node (ref "U3B") (pin "15") (pinfunction "2CLR_15") (pintype "unspecified"))
      (node (ref "U4B") (pin "1") (pinfunction "1CLR_1") (pintype "unspecified"))
      (node (ref "U6A") (pin "1") (pinfunction "1Y_1") (pintype "unspecified"))
    )
    (net (code "25") (name "B+{slash}L") (class "Default")
      (node (ref "U10A") (pin "6") (pinfunction "A1_6") (pintype "unspecified"))
      (node (ref "U5B") (pin "8") (pinfunction "3A_8") (pintype "unspecified"))
      (node (ref "U6D") (pin "8") (pinfunction "/3Y_8") (pintype "unspecified"))
      (node (ref "U8A") (pin "6") (pinfunction "A1_6") (pintype "unspecified"))
      (node (ref "U9A") (pin "6") (pinfunction "A1_6") (pintype "unspecified"))
    )
    (net (code "26") (name "BD0") (class "Default")
      (node (ref "CN1") (pin "27") (pinfunction "BD0_27") (pintype "unspecified"))
      (node (ref "U11E") (pin "2") (pinfunction "1Q_2") (pintype "unspecified"))
      (node (ref "U15E") (pin "2") (pinfunction "A1_2") (pintype "unspecified"))
      (node (ref "U9E") (pin "18") (pinfunction "1Y1_18") (pintype "unspecified"))
      (node (ref "U9F") (pin "18") (pinfunction "B1_18") (pintype "unspecified"))
    )
    (net (code "27") (name "BD1") (class "Default")
      (node (ref "CN1") (pin "28") (pinfunction "BD1_28") (pintype "unspecified"))
      (node (ref "U11E") (pin "5") (pinfunction "2Q_5") (pintype "unspecified"))
      (node (ref "U15E") (pin "3") (pinfunction "A2_3") (pintype "unspecified"))
      (node (ref "U9E") (pin "16") (pinfunction "1Y2_16") (pintype "unspecified"))
      (node (ref "U9F") (pin "17") (pinfunction "B2_17") (pintype "unspecified"))
    )
    (net (code "28") (name "BD2") (class "Default")
      (node (ref "CN1") (pin "29") (pinfunction "BD2_29") (pintype "unspecified"))
      (node (ref "U11E") (pin "6") (pinfunction "3Q_6") (pintype "unspecified"))
      (node (ref "U15E") (pin "4") (pinfunction "A3_4") (pintype "unspecified"))
      (node (ref "U9E") (pin "14") (pinfunction "1Y3_14") (pintype "unspecified"))
      (node (ref "U9F") (pin "16") (pinfunction "B3_16") (pintype "unspecified"))
    )
    (net (code "29") (name "BD3") (class "Default")
      (node (ref "CN1") (pin "30") (pinfunction "BD3_30") (pintype "unspecified"))
      (node (ref "U11E") (pin "9") (pinfunction "4Q_9") (pintype "unspecified"))
      (node (ref "U15E") (pin "5") (pinfunction "A4_5") (pintype "unspecified"))
      (node (ref "U9E") (pin "12") (pinfunction "1Y4_12") (pintype "unspecified"))
      (node (ref "U9F") (pin "15") (pinfunction "B4_15") (pintype "unspecified"))
    )
    (net (code "30") (name "BD4") (class "Default")
      (node (ref "CN1") (pin "31") (pinfunction "BD4_31") (pintype "unspecified"))
      (node (ref "U11E") (pin "12") (pinfunction "5Q_12") (pintype "unspecified"))
      (node (ref "U15E") (pin "6") (pinfunction "A5_6") (pintype "unspecified"))
      (node (ref "U9E") (pin "9") (pinfunction "2Y1_9") (pintype "unspecified"))
      (node (ref "U9F") (pin "14") (pinfunction "B5_14") (pintype "unspecified"))
    )
    (net (code "31") (name "BD5") (class "Default")
      (node (ref "CN1") (pin "32") (pinfunction "BD5_32") (pintype "unspecified"))
      (node (ref "U11E") (pin "15") (pinfunction "6Q_15") (pintype "unspecified"))
      (node (ref "U15E") (pin "7") (pinfunction "A6_7") (pintype "unspecified"))
      (node (ref "U7D") (pin "3") (pinfunction "1D_3") (pintype "unspecified"))
      (node (ref "U9E") (pin "7") (pinfunction "2Y2_7") (pintype "unspecified"))
      (node (ref "U9F") (pin "13") (pinfunction "B6_13") (pintype "unspecified"))
    )
    (net (code "32") (name "BD6") (class "Default")
      (node (ref "CN1") (pin "33") (pinfunction "BD6_33") (pintype "unspecified"))
      (node (ref "U11E") (pin "16") (pinfunction "7Q_16") (pintype "unspecified"))
      (node (ref "U15E") (pin "8") (pinfunction "A7_8") (pintype "unspecified"))
      (node (ref "U7D") (pin "4") (pinfunction "2D_4") (pintype "unspecified"))
      (node (ref "U9E") (pin "5") (pinfunction "2Y3_5") (pintype "unspecified"))
      (node (ref "U9F") (pin "12") (pinfunction "B7_12") (pintype "unspecified"))
    )
    (net (code "33") (name "BD7") (class "Default")
      (node (ref "CN1") (pin "34") (pinfunction "BD7_34") (pintype "unspecified"))
      (node (ref "U11E") (pin "19") (pinfunction "8Q_19") (pintype "unspecified"))
      (node (ref "U15E") (pin "9") (pinfunction "A8_9") (pintype "unspecified"))
      (node (ref "U7D") (pin "7") (pinfunction "3D_7") (pintype "unspecified"))
      (node (ref "U9E") (pin "3") (pinfunction "2Y4_3") (pintype "unspecified"))
      (node (ref "U9F") (pin "11") (pinfunction "B8_11") (pintype "unspecified"))
    )
    (net (code "34") (name "BD8") (class "Default")
      (node (ref "CN1") (pin "35") (pinfunction "BD8_35") (pintype "unspecified"))
      (node (ref "U11F") (pin "18") (pinfunction "B1_18") (pintype "unspecified"))
      (node (ref "U13E") (pin "2") (pinfunction "1Q_2") (pintype "unspecified"))
      (node (ref "U14E") (pin "2") (pinfunction "A1_2") (pintype "unspecified"))
      (node (ref "U7D") (pin "8") (pinfunction "4D_8") (pintype "unspecified"))
    )
    (net (code "35") (name "BD9") (class "Default")
      (node (ref "CN1") (pin "36") (pinfunction "BD9_36") (pintype "unspecified"))
      (node (ref "U11F") (pin "17") (pinfunction "B2_17") (pintype "unspecified"))
      (node (ref "U13E") (pin "5") (pinfunction "2Q_5") (pintype "unspecified"))
      (node (ref "U14E") (pin "3") (pinfunction "A2_3") (pintype "unspecified"))
      (node (ref "U7D") (pin "13") (pinfunction "5D_13") (pintype "unspecified"))
    )
    (net (code "36") (name "BD10") (class "Default")
      (node (ref "CN1") (pin "37") (pinfunction "BD10_37") (pintype "unspecified"))
      (node (ref "U11F") (pin "16") (pinfunction "B3_16") (pintype "unspecified"))
      (node (ref "U13E") (pin "6") (pinfunction "3Q_6") (pintype "unspecified"))
      (node (ref "U14E") (pin "4") (pinfunction "A3_4") (pintype "unspecified"))
      (node (ref "U7D") (pin "14") (pinfunction "6D_14") (pintype "unspecified"))
    )
    (net (code "37") (name "BD11") (class "Default")
      (node (ref "CN1") (pin "38") (pinfunction "BD11_38") (pintype "unspecified"))
      (node (ref "U11F") (pin "15") (pinfunction "B4_15") (pintype "unspecified"))
      (node (ref "U13E") (pin "9") (pinfunction "4Q_9") (pintype "unspecified"))
      (node (ref "U14E") (pin "5") (pinfunction "A4_5") (pintype "unspecified"))
      (node (ref "U7D") (pin "17") (pinfunction "7D_17") (pintype "unspecified"))
    )
    (net (code "38") (name "BD12") (class "Default")
      (node (ref "CN1") (pin "39") (pinfunction "BD12_39") (pintype "unspecified"))
      (node (ref "U11F") (pin "14") (pinfunction "B5_14") (pintype "unspecified"))
      (node (ref "U13E") (pin "12") (pinfunction "5Q_12") (pintype "unspecified"))
      (node (ref "U14E") (pin "6") (pinfunction "A5_6") (pintype "unspecified"))
      (node (ref "U7D") (pin "18") (pinfunction "8D_18") (pintype "unspecified"))
    )
    (net (code "39") (name "BD13") (class "Default")
      (node (ref "CN1") (pin "40") (pinfunction "BD13_40") (pintype "unspecified"))
      (node (ref "U11F") (pin "13") (pinfunction "B6_13") (pintype "unspecified"))
      (node (ref "U13E") (pin "15") (pinfunction "6Q_15") (pintype "unspecified"))
      (node (ref "U14E") (pin "7") (pinfunction "A6_7") (pintype "unspecified"))
    )
    (net (code "40") (name "BD14") (class "Default")
      (node (ref "CN1") (pin "41") (pinfunction "BD14_41") (pintype "unspecified"))
      (node (ref "U11F") (pin "12") (pinfunction "B7_12") (pintype "unspecified"))
      (node (ref "U13E") (pin "16") (pinfunction "7Q_16") (pintype "unspecified"))
      (node (ref "U14E") (pin "8") (pinfunction "A7_8") (pintype "unspecified"))
    )
    (net (code "41") (name "BD15") (class "Default")
      (node (ref "CN1") (pin "42") (pinfunction "BD15_42") (pintype "unspecified"))
      (node (ref "U11F") (pin "11") (pinfunction "B8_11") (pintype "unspecified"))
      (node (ref "U13E") (pin "19") (pinfunction "8Q_19") (pintype "unspecified"))
      (node (ref "U14E") (pin "9") (pinfunction "A8_9") (pintype "unspecified"))
    )
    (net (code "42") (name "BGACK") (class "Default")
      (node (ref "U11D") (pin "1") (pinfunction "/OE_1") (pintype "unspecified"))
      (node (ref "U15C") (pin "1") (pinfunction "1G_1") (pintype "unspecified"))
      (node (ref "U15C") (pin "19") (pinfunction "2G_19") (pintype "unspecified"))
      (node (ref "U3D") (pin "1") (pinfunction "1A_1") (pintype "unspecified"))
      (node (ref "U3D") (pin "8") (pinfunction "2B_8") (pintype "unspecified"))
      (node (ref "U6A") (pin "13") (pinfunction "4Y_13") (pintype "unspecified"))
      (node (ref "U6D") (pin "4") (pinfunction "2A_4") (pintype "unspecified"))
      (node (ref "U7C") (pin "12") (pinfunction "4A_12") (pintype "unspecified"))
      (node (ref "U8C") (pin "19") (pinfunction "2G_19") (pintype "unspecified"))
    )
    (net (code "43") (name "CAS") (class "Default")
      (node (ref "U10C") (pin "3") (pinfunction "2A_3") (pintype "unspecified"))
      (node (ref "U2C") (pin "1") (pinfunction "1A_1") (pintype "unspecified"))
      (node (ref "U3A") (pin "4") (pinfunction "CLK_4") (pintype "unspecified"))
      (node (ref "U3C") (pin "9") (pinfunction "/2Q_9") (pintype "unspecified"))
    )
    (net (code "44") (name "CK") (class "Default")
      (node (ref "U1C") (pin "2") (pinfunction "CK_2") (pintype "unspecified"))
      (node (ref "U1E") (pin "6") (pinfunction "/2Y_6") (pintype "unspecified"))
      (node (ref "U2B") (pin "12") (pinfunction "CLK_12") (pintype "unspecified"))
      (node (ref "U2B") (pin "4") (pinfunction "CLK_4") (pintype "unspecified"))
      (node (ref "U3A") (pin "12") (pinfunction "CLK_12") (pintype "unspecified"))
      (node (ref "U3B") (pin "12") (pinfunction "CLK_12") (pintype "unspecified"))
      (node (ref "U3B") (pin "4") (pinfunction "CLK_4") (pintype "unspecified"))
      (node (ref "U3C") (pin "12") (pinfunction "CLK_12") (pintype "unspecified"))
      (node (ref "U3C") (pin "4") (pinfunction "CLK_4") (pintype "unspecified"))
      (node (ref "U4B") (pin "12") (pinfunction "CLK_12") (pintype "unspecified"))
      (node (ref "U4B") (pin "4") (pinfunction "CLK_4") (pintype "unspecified"))
    )
    (net (code "45") (name "CLR") (class "Default")
      (node (ref "RP2") (pin "4") (pinfunction "+5V_4") (pintype "unspecified"))
      (node (ref "U3E") (pin "1") (pinfunction "1CLR_1") (pintype "unspecified"))
      (node (ref "U3E") (pin "11") (pinfunction "2PR_11") (pintype "unspecified"))
      (node (ref "U3E") (pin "15") (pinfunction "2CLR_15") (pintype "unspecified"))
      (node (ref "U7F") (pin "9") (pinfunction "CLR_9") (pintype "unspecified"))
      (node (ref "U8F") (pin "9") (pinfunction "CLR_9") (pintype "unspecified"))
    )
    (net (code "46") (name "CMUX") (class "Default")
      (node (ref "U11C") (pin "1") (pinfunction "/OE_1") (pintype "unspecified"))
      (node (ref "U15F") (pin "10") (pinfunction "3B_10") (pintype "unspecified"))
      (node (ref "U2D") (pin "10") (pinfunction "B3_10") (pintype "unspecified"))
      (node (ref "U4A") (pin "4") (pinfunction "2A_4") (pintype "unspecified"))
      (node (ref "U4B") (pin "10") (pinfunction "2Q_10") (pintype "unspecified"))
      (node (ref "U6D") (pin "5") (pinfunction "2B_5") (pintype "unspecified"))
    )
    (net (code "47") (name "CPUC1") (class "Default")
      (node (ref "U1A") (pin "1") (pinfunction "A1_1") (pintype "unspecified"))
      (node (ref "U2B") (pin "6") (pinfunction "1Q_6") (pintype "unspecified"))
      (node (ref "U5A") (pin "9") (pinfunction "3A_9") (pintype "unspecified"))
      (node (ref "U7C") (pin "13") (pinfunction "4B_13") (pintype "unspecified"))
    )
    (net (code "48") (name "CPUCK") (class "Default")
      (node (ref "CN1") (pin "22") (pinfunction "CPUCK_22") (pintype "unspecified"))
      (node (ref "R10") (pin "1") (pinfunction "1_1") (pintype "unspecified"))
    )
    (net (code "49") (name "DOTCK") (class "Default")
      (node (ref "CN1") (pin "106") (pinfunction "DOTCK_106") (pintype "unspecified"))
      (node (ref "U1E") (pin "8") (pinfunction "/3Y_8") (pintype "unspecified"))
      (node (ref "U3E") (pin "12") (pinfunction "CLK_12") (pintype "unspecified"))
      (node (ref "U3E") (pin "4") (pinfunction "CLK_4") (pintype "unspecified"))
      (node (ref "U5D") (pin "12") (pinfunction "CLK_12") (pintype "unspecified"))
      (node (ref "U5D") (pin "4") (pinfunction "CLK_4") (pintype "unspecified"))
      (node (ref "U7F") (pin "7") (pinfunction "CLK_7") (pintype "unspecified"))
      (node (ref "U8F") (pin "7") (pinfunction "CLK_7") (pintype "unspecified"))
    )
    (net (code "50") (name "E") (class "Default")
      (node (ref "CN1") (pin "16") (pinfunction "E_16") (pintype "unspecified"))
      (node (ref "U8C") (pin "14") (pinfunction "1Y3_14") (pintype "unspecified"))
    )
    (net (code "51") (name "FC2") (class "Default")
      (node (ref "U10C") (pin "11") (pinfunction "3C_11") (pintype "unspecified"))
      (node (ref "U13A") (pin "26") (pinfunction "FC2_26") (pintype "unspecified"))
      (node (ref "U7C") (pin "2") (pinfunction "1B_2") (pintype "unspecified"))
    )
    (net (code "52") (name "GND") (class "Default")
      (node (ref "C1") (pin "2") (pinfunction "GND_2") (pintype "unspecified"))
      (node (ref "C10") (pin "2") (pinfunction "GND_2") (pintype "unspecified"))
      (node (ref "C11") (pin "2") (pinfunction "GND_2") (pintype "unspecified"))
      (node (ref "C12") (pin "2") (pinfunction "GND_2") (pintype "unspecified"))
      (node (ref "C13") (pin "2") (pinfunction "GND_2") (pintype "unspecified"))
      (node (ref "C14") (pin "2") (pinfunction "GND_2") (pintype "unspecified"))
      (node (ref "C15") (pin "2") (pinfunction "GND_2") (pintype "unspecified"))
      (node (ref "C16") (pin "2") (pinfunction "GND_2") (pintype "unspecified"))
      (node (ref "C17") (pin "2") (pinfunction "GND_2") (pintype "unspecified"))
      (node (ref "C18") (pin "2") (pinfunction "GND_2") (pintype "unspecified"))
      (node (ref "C19") (pin "1") (pinfunction "1_1") (pintype "unspecified"))
      (node (ref "C2") (pin "2") (pinfunction "GND_2") (pintype "unspecified"))
      (node (ref "C20") (pin "2") (pinfunction "GND_2") (pintype "unspecified"))
      (node (ref "C21") (pin "1") (pinfunction "1_1") (pintype "unspecified"))
      (node (ref "C22") (pin "2") (pinfunction "GND_2") (pintype "unspecified"))
      (node (ref "C23") (pin "2") (pinfunction "GND_2") (pintype "unspecified"))
      (node (ref "C24") (pin "2") (pinfunction "GND_2") (pintype "unspecified"))
      (node (ref "C25") (pin "2") (pinfunction "GND_2") (pintype "unspecified"))
      (node (ref "C26") (pin "2") (pinfunction "GND_2") (pintype "unspecified"))
      (node (ref "C27") (pin "2") (pinfunction "GND_2") (pintype "unspecified"))
      (node (ref "C28") (pin "2") (pinfunction "GND_2") (pintype "unspecified"))
      (node (ref "C29") (pin "2") (pinfunction "GND_2") (pintype "unspecified"))
      (node (ref "C3") (pin "2") (pinfunction "GND_2") (pintype "unspecified"))
      (node (ref "C30") (pin "2") (pinfunction "GND_2") (pintype "unspecified"))
      (node (ref "C31") (pin "2") (pinfunction "GND_2") (pintype "unspecified"))
      (node (ref "C32") (pin "2") (pinfunction "GND_2") (pintype "unspecified"))
      (node (ref "C33") (pin "2") (pinfunction "GND_2") (pintype "unspecified"))
      (node (ref "C34") (pin "2") (pinfunction "GND_2") (pintype "unspecified"))
      (node (ref "C35") (pin "2") (pinfunction "GND_2") (pintype "unspecified"))
      (node (ref "C36") (pin "2") (pinfunction "GND_2") (pintype "unspecified"))
      (node (ref "C37") (pin "2") (pinfunction "GND_2") (pintype "unspecified"))
      (node (ref "C38") (pin "2") (pinfunction "GND_2") (pintype "unspecified"))
      (node (ref "C39") (pin "2") (pinfunction "2_2") (pintype "unspecified"))
      (node (ref "C4") (pin "2") (pinfunction "GND_2") (pintype "unspecified"))
      (node (ref "C40") (pin "2") (pinfunction "2_2") (pintype "unspecified"))
      (node (ref "C41") (pin "2") (pinfunction "GND_2") (pintype "unspecified"))
      (node (ref "C42") (pin "2") (pinfunction "2_2") (pintype "unspecified"))
      (node (ref "C43") (pin "1") (pinfunction "1_1") (pintype "unspecified"))
      (node (ref "C5") (pin "2") (pinfunction "GND_2") (pintype "unspecified"))
      (node (ref "C6") (pin "2") (pinfunction "GND_2") (pintype "unspecified"))
      (node (ref "C7") (pin "2") (pinfunction "GND_2") (pintype "unspecified"))
      (node (ref "C8") (pin "2") (pinfunction "2_2") (pintype "unspecified"))
      (node (ref "CN1") (pin "117") (pinfunction "DGND_117") (pintype "unspecified"))
      (node (ref "CN1") (pin "118") (pinfunction "DGND_118") (pintype "unspecified"))
      (node (ref "CN1") (pin "17") (pinfunction "DGND_17") (pintype "unspecified"))
      (node (ref "CN1") (pin "18") (pinfunction "DGND_18") (pintype "unspecified"))
      (node (ref "CN1") (pin "43") (pinfunction "DGND_43") (pintype "unspecified"))
      (node (ref "CN1") (pin "44") (pinfunction "DGND_44") (pintype "unspecified"))
      (node (ref "CN1") (pin "89") (pinfunction "DGND_89") (pintype "unspecified"))
      (node (ref "CN1") (pin "90") (pinfunction "DGND_90") (pintype "unspecified"))
      (node (ref "L1") (pin "2") (pinfunction "2_2") (pintype "unspecified"))
      (node (ref "R13") (pin "1") (pinfunction "1_1") (pintype "unspecified"))
      (node (ref "R16") (pin "1") (pinfunction "1_1") (pintype "unspecified"))
      (node (ref "R9") (pin "1") (pinfunction "1_1") (pintype "unspecified"))
      (node (ref "U10A") (pin "9") (pinfunction "GND_9") (pintype "unspecified"))
      (node (ref "U10B") (pin "11") (pinfunction "B4_11") (pintype "unspecified"))
      (node (ref "U10B") (pin "15") (pinfunction "B3_15") (pintype "unspecified"))
      (node (ref "U10B") (pin "2") (pinfunction "B2_2") (pintype "unspecified"))
      (node (ref "U10B") (pin "6") (pinfunction "B1_6") (pintype "unspecified"))
      (node (ref "U10B") (pin "8") (pinfunction "GND_8") (pintype "unspecified"))
      (node (ref "U10C") (pin "7") (pinfunction "GND_7") (pintype "unspecified"))
      (node (ref "U11A") (pin "10") (pinfunction "GND_10") (pintype "unspecified"))
      (node (ref "U11B") (pin "10") (pinfunction "GND_10") (pintype "unspecified"))
      (node (ref "U11C") (pin "10") (pinfunction "GND_10") (pintype "unspecified"))
      (node (ref "U11C") (pin "3") (pinfunction "1D_3") (pintype "unspecified"))
      (node (ref "U11C") (pin "4") (pinfunction "2D_4") (pintype "unspecified"))
      (node (ref "U11D") (pin "10") (pinfunction "GND_10") (pintype "unspecified"))
      (node (ref "U11E") (pin "10") (pinfunction "GND_10") (pintype "unspecified"))
      (node (ref "U11F") (pin "10") (pinfunction "GND_10") (pintype "unspecified"))
      (node (ref "U12F") (pin "5") (pinfunction "E1_5") (pintype "unspecified"))
      (node (ref "U12F") (pin "8") (pinfunction "GND_8") (pintype "unspecified"))
      (node (ref "U13A") (pin "16") (pinfunction "GND_16") (pintype "unspecified"))
      (node (ref "U13A") (pin "53") (pinfunction "GND_53") (pintype "unspecified"))
      (node (ref "U13D") (pin "14") (pinfunction "GND_14") (pintype "unspecified"))
      (node (ref "U13D") (pin "20") (pinfunction "CE_20") (pintype "unspecified"))
      (node (ref "U13E") (pin "10") (pinfunction "GND_10") (pintype "unspecified"))
      (node (ref "U13F") (pin "8") (pinfunction "GND_8") (pintype "unspecified"))
      (node (ref "U14D") (pin "14") (pinfunction "GND_14") (pintype "unspecified"))
      (node (ref "U14D") (pin "20") (pinfunction "CE_20") (pintype "unspecified"))
      (node (ref "U14E") (pin "10") (pinfunction "GND_10") (pintype "unspecified"))
      (node (ref "U14F") (pin "8") (pinfunction "GND_8") (pintype "unspecified"))
      (node (ref "U15B") (pin "7") (pinfunction "GND_7") (pintype "unspecified"))
      (node (ref "U15C") (pin "10") (pinfunction "GND_10") (pintype "unspecified"))
      (node (ref "U15E") (pin "10") (pinfunction "GND_10") (pintype "unspecified"))
      (node (ref "U15F") (pin "7") (pinfunction "GND_7") (pintype "unspecified"))
      (node (ref "U1A") (pin "7") (pinfunction "GND_7") (pintype "unspecified"))
      (node (ref "U1B") (pin "7") (pinfunction "GND_7") (pintype "unspecified"))
      (node (ref "U1C") (pin "10") (pinfunction "ET_10") (pintype "unspecified"))
      (node (ref "U1C") (pin "3") (pinfunction "P0_3") (pintype "unspecified"))
      (node (ref "U1C") (pin "4") (pinfunction "P1_4") (pintype "unspecified"))
      (node (ref "U1C") (pin "5") (pinfunction "P2_5") (pintype "unspecified"))
      (node (ref "U1C") (pin "6") (pinfunction "P3_6") (pintype "unspecified"))
      (node (ref "U1C") (pin "7") (pinfunction "EP_7") (pintype "unspecified"))
      (node (ref "U1C") (pin "8") (pinfunction "GND_8") (pintype "unspecified"))
      (node (ref "U1D") (pin "4") (pinfunction "G2A_4") (pintype "unspecified"))
      (node (ref "U1D") (pin "5") (pinfunction "G2B_5") (pintype "unspecified"))
      (node (ref "U1D") (pin "8") (pinfunction "GND_8") (pintype "unspecified"))
      (node (ref "U1E") (pin "7") (pinfunction "GND_7") (pintype "unspecified"))
      (node (ref "U2B") (pin "8") (pinfunction "GND_8") (pintype "unspecified"))
      (node (ref "U2C") (pin "7") (pinfunction "GND_7") (pintype "unspecified"))
      (node (ref "U2D") (pin "7") (pinfunction "GND_7") (pintype "unspecified"))
      (node (ref "U2E") (pin "7") (pinfunction "GND_7") (pintype "unspecified"))
      (node (ref "U3A") (pin "2") (pinfunction "1J_2") (pintype "unspecified"))
      (node (ref "U3A") (pin "8") (pinfunction "GND_8") (pintype "unspecified"))
      (node (ref "U3B") (pin "8") (pinfunction "GND_8") (pintype "unspecified"))
      (node (ref "U3C") (pin "8") (pinfunction "GND_8") (pintype "unspecified"))
      (node (ref "U3D") (pin "7") (pinfunction "GND_7") (pintype "unspecified"))
      (node (ref "U3E") (pin "8") (pinfunction "GND_8") (pintype "unspecified"))
      (node (ref "U4A") (pin "10") (pinfunction "3B_10") (pintype "unspecified"))
      (node (ref "U4A") (pin "7") (pinfunction "GND_7") (pintype "unspecified"))
      (node (ref "U4A") (pin "9") (pinfunction "3A_9") (pintype "unspecified"))
      (node (ref "U4B") (pin "8") (pinfunction "GND_8") (pintype "unspecified"))
      (node (ref "U4D") (pin "12") (pinfunction "4A_12") (pintype "unspecified"))
      (node (ref "U4D") (pin "7") (pinfunction "GND_7") (pintype "unspecified"))
      (node (ref "U4E") (pin "8") (pinfunction "GND_8") (pintype "unspecified"))
      (node (ref "U4F") (pin "8") (pinfunction "GND_8") (pintype "unspecified"))
      (node (ref "U5A") (pin "7") (pinfunction "GND_7") (pintype "unspecified"))
      (node (ref "U5B") (pin "7") (pinfunction "GND_7") (pintype "unspecified"))
      (node (ref "U5C") (pin "8") (pinfunction "GND_8") (pintype "unspecified"))
      (node (ref "U5D") (pin "2") (pinfunction "1J_2") (pintype "unspecified"))
      (node (ref "U5D") (pin "8") (pinfunction "GND_8") (pintype "unspecified"))
      (node (ref "U5E") (pin "7") (pinfunction "GND_7") (pintype "unspecified"))
      (node (ref "U5F") (pin "1") (pinfunction "1G_1") (pintype "unspecified"))
      (node (ref "U5F") (pin "15") (pinfunction "2G_15") (pintype "unspecified"))
      (node (ref "U5F") (pin "8") (pinfunction "GND_8") (pintype "unspecified"))
      (node (ref "U6A") (pin "7") (pinfunction "GND_7") (pintype "unspecified"))
      (node (ref "U6B") (pin "1") (pinfunction "/OE_1") (pintype "unspecified"))
      (node (ref "U6B") (pin "10") (pinfunction "GND_10") (pintype "unspecified"))
      (node (ref "U6C") (pin "10") (pinfunction "GND_10") (pintype "unspecified"))
      (node (ref "U6C") (pin "15") (pinfunction "E1_15") (pintype "unspecified"))
      (node (ref "U6C") (pin "16") (pinfunction "E2_16") (pintype "unspecified"))
      (node (ref "U6D") (pin "7") (pinfunction "GND_7") (pintype "unspecified"))
      (node (ref "U6E") (pin "1") (pinfunction "1G_1") (pintype "unspecified"))
      (node (ref "U6E") (pin "15") (pinfunction "2G_15") (pintype "unspecified"))
      (node (ref "U6E") (pin "8") (pinfunction "GND_8") (pintype "unspecified"))
      (node (ref "U6F") (pin "7") (pinfunction "GND_7") (pintype "unspecified"))
      (node (ref "U7A") (pin "7") (pinfunction "GND_7") (pintype "unspecified"))
      (node (ref "U7B") (pin "7") (pinfunction "GND_7") (pintype "unspecified"))
      (node (ref "U7C") (pin "7") (pinfunction "GND_7") (pintype "unspecified"))
      (node (ref "U7D") (pin "10") (pinfunction "GND_10") (pintype "unspecified"))
      (node (ref "U7E") (pin "1") (pinfunction "1G_1") (pintype "unspecified"))
      (node (ref "U7E") (pin "15") (pinfunction "2G_15") (pintype "unspecified"))
      (node (ref "U7E") (pin "8") (pinfunction "GND_8") (pintype "unspecified"))
      (node (ref "U7F") (pin "8") (pinfunction "GND_8") (pintype "unspecified"))
      (node (ref "U8A") (pin "8") (pinfunction "CS_8") (pintype "unspecified"))
      (node (ref "U8A") (pin "9") (pinfunction "GND_9") (pintype "unspecified"))
      (node (ref "U8B") (pin "8") (pinfunction "GND_8") (pintype "unspecified"))
      (node (ref "U8C") (pin "1") (pinfunction "1G_1") (pintype "unspecified"))
      (node (ref "U8C") (pin "10") (pinfunction "GND_10") (pintype "unspecified"))
      (node (ref "U8E") (pin "1") (pinfunction "1G_1") (pintype "unspecified"))
      (node (ref "U8E") (pin "15") (pinfunction "2G_15") (pintype "unspecified"))
      (node (ref "U8E") (pin "8") (pinfunction "GND_8") (pintype "unspecified"))
      (node (ref "U8F") (pin "8") (pinfunction "GND_8") (pintype "unspecified"))
      (node (ref "U9A") (pin "8") (pinfunction "CS_8") (pintype "unspecified"))
      (node (ref "U9A") (pin "9") (pinfunction "GND_9") (pintype "unspecified"))
      (node (ref "U9B") (pin "8") (pinfunction "GND_8") (pintype "unspecified"))
      (node (ref "U9D") (pin "10") (pinfunction "GND_10") (pintype "unspecified"))
      (node (ref "U9E") (pin "10") (pinfunction "GND_10") (pintype "unspecified"))
      (node (ref "U9F") (pin "10") (pinfunction "GND_10") (pintype "unspecified"))
    )
    (net (code "53") (name "IAK") (class "Default")
      (node (ref "U10C") (pin "8") (pinfunction "3Y_8") (pintype "unspecified"))
      (node (ref "U1B") (pin "5") (pinfunction "3A_5") (pintype "unspecified"))
      (node (ref "U2C") (pin "9") (pinfunction "2C_9") (pintype "unspecified"))
    )
    (net (code "54") (name "INVID") (class "Default")
      (node (ref "RP1") (pin "10") (pinfunction "+5V_10") (pintype "unspecified"))
      (node (ref "U4D") (pin "10") (pinfunction "3B_10") (pintype "unspecified"))
      (node (ref "U8F") (pin "1") (pinfunction "SI_1") (pintype "unspecified"))
      (node (ref "U9E") (pin "15") (pinfunction "2A3_15") (pintype "unspecified"))
    )
    (net (code "55") (name "IOA13") (class "Default")
      (node (ref "U11D") (pin "2") (pinfunction "1Q_2") (pintype "unspecified"))
      (node (ref "U13F") (pin "1") (pinfunction "A_1") (pintype "unspecified"))
    )
    (net (code "56") (name "IOA14") (class "Default")
      (node (ref "U11D") (pin "5") (pinfunction "2Q_5") (pintype "unspecified"))
      (node (ref "U13F") (pin "2") (pinfunction "B_2") (pintype "unspecified"))
    )
    (net (code "57") (name "IOA15") (class "Default")
      (node (ref "U11D") (pin "6") (pinfunction "3Q_6") (pintype "unspecified"))
      (node (ref "U13F") (pin "3") (pinfunction "C_3") (pintype "unspecified"))
    )
    (net (code "58") (name "IOA16") (class "Default")
      (node (ref "RP2") (pin "5") (pinfunction "+5V_5") (pintype "unspecified"))
      (node (ref "U11D") (pin "9") (pinfunction "4Q_9") (pintype "unspecified"))
      (node (ref "U13F") (pin "5") (pinfunction "G2B_5") (pintype "unspecified"))
    )
    (net (code "59") (name "IOCY") (class "Default")
      (node (ref "U2C") (pin "2") (pinfunction "1B_2") (pintype "unspecified"))
      (node (ref "U2C") (pin "8") (pinfunction "2B_8") (pintype "unspecified"))
      (node (ref "U3A") (pin "13") (pinfunction "2K_13") (pintype "unspecified"))
      (node (ref "U3A") (pin "14") (pinfunction "2J_14") (pintype "unspecified"))
      (node (ref "U3A") (pin "15") (pinfunction "2CLR_15") (pintype "unspecified"))
      (node (ref "U4B") (pin "6") (pinfunction "1Q_6") (pintype "unspecified"))
    )
    (net (code "60") (name "MALE") (class "Default")
      (node (ref "U2B") (pin "9") (pinfunction "/2Q_9") (pintype "unspecified"))
      (node (ref "U9D") (pin "11") (pinfunction "LE_11") (pintype "unspecified"))
    )
    (net (code "61") (name "MD0") (class "Default")
      (node (ref "CN1") (pin "73") (pinfunction "MD0_73") (pintype "unspecified"))
      (node (ref "U8F") (pin "2") (pinfunction "A_2") (pintype "unspecified"))
      (node (ref "U9F") (pin "2") (pinfunction "A1_2") (pintype "unspecified"))
    )
    (net (code "62") (name "MD1") (class "Default")
      (node (ref "CN1") (pin "74") (pinfunction "MD1_74") (pintype "unspecified"))
      (node (ref "U8F") (pin "3") (pinfunction "B_3") (pintype "unspecified"))
      (node (ref "U9F") (pin "3") (pinfunction "A2_3") (pintype "unspecified"))
    )
    (net (code "63") (name "MD2") (class "Default")
      (node (ref "CN1") (pin "75") (pinfunction "MD2_75") (pintype "unspecified"))
      (node (ref "U8F") (pin "4") (pinfunction "C_4") (pintype "unspecified"))
      (node (ref "U9F") (pin "4") (pinfunction "A3_4") (pintype "unspecified"))
    )
    (net (code "64") (name "MD3") (class "Default")
      (node (ref "CN1") (pin "76") (pinfunction "MD3_76") (pintype "unspecified"))
      (node (ref "U8F") (pin "5") (pinfunction "D_5") (pintype "unspecified"))
      (node (ref "U9F") (pin "5") (pinfunction "A4_5") (pintype "unspecified"))
    )
    (net (code "65") (name "MD4") (class "Default")
      (node (ref "CN1") (pin "77") (pinfunction "MD4_77") (pintype "unspecified"))
      (node (ref "U8F") (pin "10") (pinfunction "E_10") (pintype "unspecified"))
      (node (ref "U9F") (pin "6") (pinfunction "A5_6") (pintype "unspecified"))
    )
    (net (code "66") (name "MD5") (class "Default")
      (node (ref "CN1") (pin "78") (pinfunction "MD5_78") (pintype "unspecified"))
      (node (ref "U8F") (pin "11") (pinfunction "F_11") (pintype "unspecified"))
      (node (ref "U9F") (pin "7") (pinfunction "A6_7") (pintype "unspecified"))
    )
    (net (code "67") (name "MD6") (class "Default")
      (node (ref "CN1") (pin "79") (pinfunction "MD6_79") (pintype "unspecified"))
      (node (ref "U8F") (pin "12") (pinfunction "G_12") (pintype "unspecified"))
      (node (ref "U9F") (pin "8") (pinfunction "A7_8") (pintype "unspecified"))
    )
    (net (code "68") (name "MD7") (class "Default")
      (node (ref "CN1") (pin "80") (pinfunction "MD7_80") (pintype "unspecified"))
      (node (ref "U8F") (pin "14") (pinfunction "H_14") (pintype "unspecified"))
      (node (ref "U9F") (pin "9") (pinfunction "A8_9") (pintype "unspecified"))
    )
    (net (code "69") (name "MD8") (class "Default")
      (node (ref "CN1") (pin "81") (pinfunction "MD8_81") (pintype "unspecified"))
      (node (ref "U11F") (pin "2") (pinfunction "A1_2") (pintype "unspecified"))
      (node (ref "U7F") (pin "2") (pinfunction "A_2") (pintype "unspecified"))
    )
    (net (code "70") (name "MD9") (class "Default")
      (node (ref "CN1") (pin "82") (pinfunction "MD9_82") (pintype "unspecified"))
      (node (ref "U11F") (pin "3") (pinfunction "A2_3") (pintype "unspecified"))
      (node (ref "U7F") (pin "3") (pinfunction "B_3") (pintype "unspecified"))
    )
    (net (code "71") (name "MD10") (class "Default")
      (node (ref "CN1") (pin "83") (pinfunction "MD10_83") (pintype "unspecified"))
      (node (ref "U11F") (pin "4") (pinfunction "A3_4") (pintype "unspecified"))
      (node (ref "U7F") (pin "4") (pinfunction "C_4") (pintype "unspecified"))
    )
    (net (code "72") (name "MD11") (class "Default")
      (node (ref "CN1") (pin "84") (pinfunction "MD11_84") (pintype "unspecified"))
      (node (ref "U11F") (pin "5") (pinfunction "A4_5") (pintype "unspecified"))
      (node (ref "U7F") (pin "5") (pinfunction "D_5") (pintype "unspecified"))
    )
    (net (code "73") (name "MD12") (class "Default")
      (node (ref "CN1") (pin "85") (pinfunction "MD12_85") (pintype "unspecified"))
      (node (ref "U11F") (pin "6") (pinfunction "A5_6") (pintype "unspecified"))
      (node (ref "U7F") (pin "10") (pinfunction "E_10") (pintype "unspecified"))
    )
    (net (code "74") (name "MD13") (class "Default")
      (node (ref "CN1") (pin "86") (pinfunction "MD13_86") (pintype "unspecified"))
      (node (ref "U11F") (pin "7") (pinfunction "A6_7") (pintype "unspecified"))
      (node (ref "U7F") (pin "11") (pinfunction "F_11") (pintype "unspecified"))
    )
    (net (code "75") (name "MD14") (class "Default")
      (node (ref "CN1") (pin "87") (pinfunction "MD14_87") (pintype "unspecified"))
      (node (ref "U11F") (pin "8") (pinfunction "A7_8") (pintype "unspecified"))
      (node (ref "U7F") (pin "12") (pinfunction "G_12") (pintype "unspecified"))
    )
    (net (code "76") (name "MD15") (class "Default")
      (node (ref "CN1") (pin "88") (pinfunction "MD15_88") (pintype "unspecified"))
      (node (ref "U11F") (pin "9") (pinfunction "A8_9") (pintype "unspecified"))
      (node (ref "U7F") (pin "14") (pinfunction "H_14") (pintype "unspecified"))
    )
    (net (code "77") (name "MMUIO") (class "Default")
      (node (ref "U1A") (pin "4") (pinfunction "A2_4") (pintype "unspecified"))
      (node (ref "U1B") (pin "12") (pinfunction "/6Y_12") (pintype "unspecified"))
      (node (ref "U5D") (pin "11") (pinfunction "2PR_11") (pintype "unspecified"))
      (node (ref "U5D") (pin "5") (pinfunction "1PR_5") (pintype "unspecified"))
      (node (ref "U6D") (pin "12") (pinfunction "4A_12") (pintype "unspecified"))
    )
    (net (code "78") (name "MREAD") (class "Default")
      (node (ref "CN1") (pin "107") (pinfunction "MREAD_107") (pintype "unspecified"))
      (node (ref "U1E") (pin "11") (pinfunction "/4Y_11") (pintype "unspecified"))
    )
    (net (code "79") (name "MS1") (class "Default")
      (node (ref "U10A") (pin "5") (pinfunction "A0_5") (pintype "unspecified"))
      (node (ref "U7C") (pin "6") (pinfunction "/2Y_6") (pintype "unspecified"))
      (node (ref "U8A") (pin "5") (pinfunction "A0_5") (pintype "unspecified"))
      (node (ref "U9A") (pin "5") (pinfunction "A0_5") (pintype "unspecified"))
    )
    (net (code "80") (name "MS2") (class "Default")
      (node (ref "U10A") (pin "4") (pinfunction "A3_4") (pintype "unspecified"))
      (node (ref "U7C") (pin "8") (pinfunction "/3Y_8") (pintype "unspecified"))
      (node (ref "U8A") (pin "4") (pinfunction "A3_4") (pintype "unspecified"))
      (node (ref "U9A") (pin "4") (pinfunction "A3_4") (pintype "unspecified"))
    )
    (net (code "81") (name "Net-(C39-Pad1)") (class "Default")
      (node (ref "C39") (pin "1") (pinfunction "1_1") (pintype "unspecified"))
      (node (ref "Q1") (pin "2") (pinfunction "2_2") (pintype "unspecified"))
      (node (ref "R15") (pin "2") (pinfunction "2_2") (pintype "unspecified"))
      (node (ref "R16") (pin "2") (pinfunction "2_2") (pintype "unspecified"))
      (node (ref "R17") (pin "1") (pinfunction "1_1") (pintype "unspecified"))
    )
    (net (code "82") (name "Net-(L1-Pad1)") (class "Default")
      (node (ref "L1") (pin "1") (pinfunction "1_1") (pintype "unspecified"))
      (node (ref "Q1") (pin "3") (pinfunction "3_3") (pintype "unspecified"))
      (node (ref "Y1") (pin "2") (pinfunction "2_2") (pintype "unspecified"))
    )
    (net (code "83") (name "Net-(Q1-Pad1)") (class "Default")
      (node (ref "Q1") (pin "1") (pinfunction "1_1") (pintype "unspecified"))
      (node (ref "Q2") (pin "1") (pinfunction "1_1") (pintype "unspecified"))
      (node (ref "R14") (pin "1") (pinfunction "1_1") (pintype "unspecified"))
    )
    (net (code "84") (name "Net-(Q2-Pad2)") (class "Default")
      (node (ref "Q2") (pin "2") (pinfunction "2_2") (pintype "unspecified"))
      (node (ref "R15") (pin "1") (pinfunction "1_1") (pintype "unspecified"))
      (node (ref "Y1") (pin "1") (pinfunction "1_1") (pintype "unspecified"))
    )
    (net (code "85") (name "Net-(U1A-A3)") (class "Default")
      (node (ref "U1A") (pin "10") (pinfunction "B3_10") (pintype "unspecified"))
      (node (ref "U1A") (pin "11") (pinfunction "Y4_11") (pintype "unspecified"))
      (node (ref "U1A") (pin "9") (pinfunction "A3_9") (pintype "unspecified"))
    )
    (net (code "86") (name "Net-(U1A-A4)") (class "Default")
      (node (ref "U1A") (pin "12") (pinfunction "A4_12") (pintype "unspecified"))
      (node (ref "U1A") (pin "13") (pinfunction "B4_13") (pintype "unspecified"))
      (node (ref "U1A") (pin "8") (pinfunction "Y3_8") (pintype "unspecified"))
    )
    (net (code "87") (name "Net-(U1A-Y2)") (class "Default")
      (node (ref "U1A") (pin "6") (pinfunction "Y2_6") (pintype "unspecified"))
      (node (ref "U5B") (pin "11") (pinfunction "4A_11") (pintype "unspecified"))
    )
    (net (code "88") (name "Net-(U1B-{slash}3Y)") (class "Default")
      (node (ref "U1B") (pin "6") (pinfunction "/3Y_6") (pintype "unspecified"))
      (node (ref "U2D") (pin "12") (pinfunction "A4_12") (pintype "unspecified"))
    )
    (net (code "89") (name "Net-(U1C-QA)") (class "Default")
      (node (ref "U1C") (pin "14") (pinfunction "QA_14") (pintype "unspecified"))
      (node (ref "U1D") (pin "1") (pinfunction "A_1") (pintype "unspecified"))
    )
    (net (code "90") (name "Net-(U1C-QC)") (class "Default")
      (node (ref "U1C") (pin "12") (pinfunction "QC_12") (pintype "unspecified"))
      (node (ref "U1D") (pin "3") (pinfunction "C_3") (pintype "unspecified"))
    )
    (net (code "91") (name "Net-(U1C-RP0)") (class "Default")
      (node (ref "U1C") (pin "15") (pinfunction "RP0_15") (pintype "unspecified"))
      (node (ref "U2C") (pin "10") (pinfunction "2D_10") (pintype "unspecified"))
    )
    (net (code "92") (name "Net-(U1E-2A)") (class "Default")
      (node (ref "U1E") (pin "10") (pinfunction "3B_10") (pintype "unspecified"))
      (node (ref "U1E") (pin "3") (pinfunction "/1Y_3") (pintype "unspecified"))
      (node (ref "U1E") (pin "4") (pinfunction "2A_4") (pintype "unspecified"))
    )
    (net (code "93") (name "Net-(U2B-1J)") (class "Default")
      (node (ref "U2B") (pin "14") (pinfunction "2J_14") (pintype "unspecified"))
      (node (ref "U2B") (pin "2") (pinfunction "1J_2") (pintype "unspecified"))
      (node (ref "U2C") (pin "6") (pinfunction "2Y_6") (pintype "unspecified"))
    )
    (net (code "94") (name "Net-(U2C-1Y)") (class "Default")
      (node (ref "U2C") (pin "5") (pinfunction "1Y_5") (pintype "unspecified"))
      (node (ref "U3B") (pin "14") (pinfunction "2J_14") (pintype "unspecified"))
    )
    (net (code "95") (name "Net-(U2C-2E)") (class "Default")
      (node (ref "U2C") (pin "11") (pinfunction "2E_11") (pintype "unspecified"))
      (node (ref "U3B") (pin "10") (pinfunction "2Q_10") (pintype "unspecified"))
    )
    (net (code "96") (name "Net-(U2D-Y4)") (class "Default")
      (node (ref "U2D") (pin "11") (pinfunction "Y4_11") (pintype "unspecified"))
      (node (ref "U4F") (pin "14") (pinfunction "2G_14") (pintype "unspecified"))
      (node (ref "U4F") (pin "2") (pinfunction "1G_2") (pintype "unspecified"))
    )
    (net (code "97") (name "Net-(U3B-1J)") (class "Default")
      (node (ref "U3B") (pin "2") (pinfunction "1J_2") (pintype "unspecified"))
      (node (ref "U3D") (pin "6") (pinfunction "2Y_6") (pintype "unspecified"))
    )
    (net (code "98") (name "Net-(U3D-1Y)") (class "Default")
      (node (ref "U3D") (pin "5") (pinfunction "1Y_5") (pintype "unspecified"))
      (node (ref "U4B") (pin "2") (pinfunction "1J_2") (pintype "unspecified"))
    )
    (net (code "99") (name "Net-(U3E-1PR)") (class "Default")
      (node (ref "U3E") (pin "5") (pinfunction "1PR_5") (pintype "unspecified"))
      (node (ref "U4A") (pin "11") (pinfunction "4Y_11") (pintype "unspecified"))
    )
    (net (code "100") (name "Net-(U3E-1Q)") (class "Default")
      (node (ref "U3E") (pin "6") (pinfunction "1Q_6") (pintype "unspecified"))
      (node (ref "U6F") (pin "1") (pinfunction "1ACLK_1") (pintype "unspecified"))
      (node (ref "U7F") (pin "15") (pinfunction "LD_15") (pintype "unspecified"))
      (node (ref "U8F") (pin "15") (pinfunction "LD_15") (pintype "unspecified"))
    )
    (net (code "101") (name "Net-(U3E-2J)") (class "Default")
      (node (ref "U3E") (pin "13") (pinfunction "2K_13") (pintype "unspecified"))
      (node (ref "U3E") (pin "14") (pinfunction "2J_14") (pintype "unspecified"))
      (node (ref "U7F") (pin "13") (pinfunction "SO_13") (pintype "unspecified"))
    )
    (net (code "102") (name "Net-(U3E-2Q)") (class "Default")
      (node (ref "U3E") (pin "10") (pinfunction "2Q_10") (pintype "unspecified"))
      (node (ref "U4D") (pin "9") (pinfunction "3A_9") (pintype "unspecified"))
    )
    (net (code "103") (name "Net-(U4A-1B)") (class "Default")
      (node (ref "U4A") (pin "2") (pinfunction "1B_2") (pintype "unspecified"))
      (node (ref "U6C") (pin "9") (pinfunction "D3_9") (pintype "unspecified"))
    )
    (net (code "104") (name "Net-(U4A-1Y)") (class "Default")
      (node (ref "U4A") (pin "3") (pinfunction "1Y_3") (pintype "unspecified"))
      (node (ref "U6B") (pin "8") (pinfunction "4D_8") (pintype "unspecified"))
    )
    (net (code "105") (name "Net-(U4A-2B)") (class "Default")
      (node (ref "U4A") (pin "5") (pinfunction "2B_5") (pintype "unspecified"))
      (node (ref "U6B") (pin "9") (pinfunction "4Q_9") (pintype "unspecified"))
    )
    (net (code "106") (name "Net-(U4A-2Y)") (class "Default")
      (node (ref "U4A") (pin "6") (pinfunction "2Y_6") (pintype "unspecified"))
      (node (ref "U5E") (pin "12") (pinfunction "2CLR_12") (pintype "unspecified"))
      (node (ref "U5E") (pin "2") (pinfunction "1CLR_2") (pintype "unspecified"))
      (node (ref "U6F") (pin "12") (pinfunction "2CLR_12") (pintype "unspecified"))
      (node (ref "U6F") (pin "2") (pinfunction "1CLR_2") (pintype "unspecified"))
    )
    (net (code "107") (name "Net-(U4A-4B)") (class "Default")
      (node (ref "U4A") (pin "13") (pinfunction "4B_13") (pintype "unspecified"))
      (node (ref "U6B") (pin "6") (pinfunction "3Q_6") (pintype "unspecified"))
    )
    (net (code "108") (name "Net-(U4D-4Y)") (class "Default")
      (node (ref "R10") (pin "2") (pinfunction "2_2") (pintype "unspecified"))
      (node (ref "U4D") (pin "11") (pinfunction "4Y_11") (pintype "unspecified"))
    )
    (net (code "109") (name "Net-(U5A-1Y)") (class "Default")
      (node (ref "U5A") (pin "12") (pinfunction "1Y_12") (pintype "unspecified"))
      (node (ref "U5A") (pin "5") (pinfunction "2C_5") (pintype "unspecified"))
    )
    (net (code "110") (name "Net-(U5B-3Y)") (class "Default")
      (node (ref "U5B") (pin "10") (pinfunction "3Y_10") (pintype "unspecified"))
      (node (ref "U8B") (pin "7") (pinfunction "C0_7") (pintype "unspecified"))
    )
    (net (code "111") (name "Net-(U5C-1R)") (class "Default")
      (node (ref "C19") (pin "2") (pinfunction "2_2") (pintype "unspecified"))
      (node (ref "R4") (pin "2") (pinfunction "2_2") (pintype "unspecified"))
      (node (ref "R5") (pin "2") (pinfunction "2_2") (pintype "unspecified"))
      (node (ref "U5C") (pin "1") (pinfunction "1R_1") (pintype "unspecified"))
    )
    (net (code "112") (name "Net-(U5C-3R)") (class "Default")
      (node (ref "C21") (pin "2") (pinfunction "2_2") (pintype "unspecified"))
      (node (ref "R6") (pin "2") (pinfunction "2_2") (pintype "unspecified"))
      (node (ref "R7") (pin "2") (pinfunction "2_2") (pintype "unspecified"))
      (node (ref "U5C") (pin "10") (pinfunction "3R_10") (pintype "unspecified"))
    )
    (net (code "113") (name "Net-(U5C-4Q)") (class "Default")
      (node (ref "U5C") (pin "13") (pinfunction "4Q_13") (pintype "unspecified"))
      (node (ref "U9E") (pin "8") (pinfunction "1A4_8") (pintype "unspecified"))
    )
    (net (code "114") (name "Net-(U6B-1D)") (class "Default")
      (node (ref "U6B") (pin "3") (pinfunction "1D_3") (pintype "unspecified"))
      (node (ref "U6C") (pin "6") (pinfunction "D0_6") (pintype "unspecified"))
    )
    (net (code "115") (name "Net-(U6B-1Q)") (class "Default")
      (node (ref "U6B") (pin "2") (pinfunction "1Q_2") (pintype "unspecified"))
      (node (ref "U7B") (pin "12") (pinfunction "2CLR_12") (pintype "unspecified"))
      (node (ref "U7B") (pin "2") (pinfunction "1CLR_2") (pintype "unspecified"))
    )
    (net (code "116") (name "Net-(U6B-2D)") (class "Default")
      (node (ref "U6B") (pin "4") (pinfunction "2D_4") (pintype "unspecified"))
      (node (ref "U6C") (pin "7") (pinfunction "D1_7") (pintype "unspecified"))
    )
    (net (code "117") (name "Net-(U6B-3D)") (class "Default")
      (node (ref "U6B") (pin "7") (pinfunction "3D_7") (pintype "unspecified"))
      (node (ref "U6C") (pin "8") (pinfunction "D2_8") (pintype "unspecified"))
    )
    (net (code "118") (name "Net-(U6B-5D)") (class "Default")
      (node (ref "U6B") (pin "13") (pinfunction "5D_13") (pintype "unspecified"))
      (node (ref "U6C") (pin "11") (pinfunction "D4_11") (pintype "unspecified"))
    )
    (net (code "119") (name "Net-(U6B-6D)") (class "Default")
      (node (ref "U6B") (pin "14") (pinfunction "6D_14") (pintype "unspecified"))
      (node (ref "U6C") (pin "12") (pinfunction "D5_12") (pintype "unspecified"))
    )
    (net (code "120") (name "Net-(U6B-7D)") (class "Default")
      (node (ref "U6B") (pin "17") (pinfunction "7D_17") (pintype "unspecified"))
      (node (ref "U6B") (pin "18") (pinfunction "8D_18") (pintype "unspecified"))
      (node (ref "U6C") (pin "13") (pinfunction "D6_13") (pintype "unspecified"))
    )
    (net (code "121") (name "Net-(U6C-A0)") (class "Default")
      (node (ref "U6C") (pin "1") (pinfunction "A0_1") (pintype "unspecified"))
      (node (ref "U7B") (pin "3") (pinfunction "1QA_3") (pintype "unspecified"))
    )
    (net (code "122") (name "Net-(U6C-A1)") (class "Default")
      (node (ref "U6C") (pin "2") (pinfunction "A1_2") (pintype "unspecified"))
      (node (ref "U7B") (pin "4") (pinfunction "1QB_4") (pintype "unspecified"))
    )
    (net (code "123") (name "Net-(U6C-A2)") (class "Default")
      (node (ref "U6C") (pin "3") (pinfunction "A2_3") (pintype "unspecified"))
      (node (ref "U7B") (pin "5") (pinfunction "1QC_5") (pintype "unspecified"))
    )
    (net (code "124") (name "Net-(U6C-A3)") (class "Default")
      (node (ref "U6C") (pin "4") (pinfunction "A3_4") (pintype "unspecified"))
      (node (ref "U7B") (pin "13") (pinfunction "2ACLK_13") (pintype "unspecified"))
      (node (ref "U7B") (pin "6") (pinfunction "1QD_6") (pintype "unspecified"))
    )
    (net (code "125") (name "Net-(U6C-A4)") (class "Default")
      (node (ref "U6C") (pin "5") (pinfunction "A4_5") (pintype "unspecified"))
      (node (ref "U7B") (pin "11") (pinfunction "2QA_11") (pintype "unspecified"))
    )
    (net (code "126") (name "Net-(U6C-A5)") (class "Default")
      (node (ref "U6C") (pin "17") (pinfunction "A5_17") (pintype "unspecified"))
      (node (ref "U7B") (pin "10") (pinfunction "2QB_10") (pintype "unspecified"))
    )
    (net (code "127") (name "Net-(U6D-3B)") (class "Default")
      (node (ref "U6D") (pin "10") (pinfunction "3B_10") (pintype "unspecified"))
      (node (ref "U6D") (pin "11") (pinfunction "/4Y_11") (pintype "unspecified"))
    )
    (net (code "128") (name "Net-(U6D-{slash}2Y)") (class "Default")
      (node (ref "U6D") (pin "6") (pinfunction "/2Y_6") (pintype "unspecified"))
      (node (ref "U7D") (pin "1") (pinfunction "/OE_1") (pintype "unspecified"))
    )
    (net (code "129") (name "Net-(U7C-2A)") (class "Default")
      (node (ref "U7C") (pin "10") (pinfunction "3B_10") (pintype "unspecified"))
      (node (ref "U7C") (pin "3") (pinfunction "/1Y_3") (pintype "unspecified"))
      (node (ref "U7C") (pin "4") (pinfunction "2A_4") (pintype "unspecified"))
    )
    (net (code "130") (name "Net-(U7F-SI)") (class "Default")
      (node (ref "U7F") (pin "1") (pinfunction "SI_1") (pintype "unspecified"))
      (node (ref "U8F") (pin "13") (pinfunction "SO_13") (pintype "unspecified"))
    )
    (net (code "131") (name "Net-(U8B-C4)") (class "Default")
      (node (ref "U8B") (pin "9") (pinfunction "C4_9") (pintype "unspecified"))
      (node (ref "U9B") (pin "7") (pinfunction "C0_7") (pintype "unspecified"))
    )
    (net (code "132") (name "Net-(U10A-CS)") (class "Default")
      (node (ref "U10A") (pin "8") (pinfunction "CS_8") (pintype "unspecified"))
      (node (ref "U5B") (pin "13") (pinfunction "4Y_13") (pintype "unspecified"))
    )
    (net (code "133") (name "Net-(U10A-WE)") (class "Default")
      (node (ref "U10A") (pin "10") (pinfunction "WE_10") (pintype "unspecified"))
      (node (ref "U5D") (pin "10") (pinfunction "2Q_10") (pintype "unspecified"))
      (node (ref "U8A") (pin "10") (pinfunction "WE_10") (pintype "unspecified"))
      (node (ref "U9A") (pin "10") (pinfunction "WE_10") (pintype "unspecified"))
    )
    (net (code "134") (name "Net-(U10B-S1)") (class "Default")
      (node (ref "U10B") (pin "4") (pinfunction "S1_4") (pintype "unspecified"))
      (node (ref "U9D") (pin "13") (pinfunction "5D_13") (pintype "unspecified"))
    )
    (net (code "135") (name "Net-(U10B-S2)") (class "Default")
      (node (ref "U10B") (pin "1") (pinfunction "S2_1") (pintype "unspecified"))
      (node (ref "U9D") (pin "14") (pinfunction "6D_14") (pintype "unspecified"))
    )
    (net (code "136") (name "Net-(U10B-S3)") (class "Default")
      (node (ref "U10B") (pin "13") (pinfunction "S3_13") (pintype "unspecified"))
      (node (ref "U9D") (pin "17") (pinfunction "7D_17") (pintype "unspecified"))
    )
    (net (code "137") (name "Net-(U10B-S4)") (class "Default")
      (node (ref "U10B") (pin "10") (pinfunction "S4_10") (pintype "unspecified"))
      (node (ref "U9D") (pin "18") (pinfunction "8D_18") (pintype "unspecified"))
    )
    (net (code "138") (name "Net-(U10C-1A)") (class "Default")
      (node (ref "U10C") (pin "1") (pinfunction "1A_1") (pintype "unspecified"))
      (node (ref "U10C") (pin "4") (pinfunction "2B_4") (pintype "unspecified"))
      (node (ref "U5C") (pin "9") (pinfunction "3Q_9") (pintype "unspecified"))
      (node (ref "U9E") (pin "4") (pinfunction "1A2_4") (pintype "unspecified"))
    )
    (net (code "139") (name "Net-(U10C-1B)") (class "Default")
      (node (ref "U10C") (pin "2") (pinfunction "1B_2") (pintype "unspecified"))
      (node (ref "U10C") (pin "5") (pinfunction "2C_5") (pintype "unspecified"))
      (node (ref "U5C") (pin "4") (pinfunction "1Q_4") (pintype "unspecified"))
      (node (ref "U9E") (pin "2") (pinfunction "1A1_2") (pintype "unspecified"))
    )
    (net (code "140") (name "Net-(U10C-2Y)") (class "Default")
      (node (ref "U10C") (pin "6") (pinfunction "2Y_6") (pintype "unspecified"))
      (node (ref "U11E") (pin "11") (pinfunction "G_11") (pintype "unspecified"))
      (node (ref "U13E") (pin "11") (pinfunction "G_11") (pintype "unspecified"))
    )
    (net (code "141") (name "Net-(U10C-3A)") (class "Default")
      (node (ref "U10C") (pin "9") (pinfunction "3A_9") (pintype "unspecified"))
      (node (ref "U13A") (pin "27") (pinfunction "FC1_27") (pintype "unspecified"))
    )
    (net (code "142") (name "Net-(U10C-3B)") (class "Default")
      (node (ref "R9") (pin "2") (pinfunction "2_2") (pintype "unspecified"))
      (node (ref "U10C") (pin "10") (pinfunction "3B_10") (pintype "unspecified"))
      (node (ref "U13A") (pin "28") (pinfunction "FC0_28") (pintype "unspecified"))
    )
    (net (code "143") (name "Net-(U11A-A8)") (class "Default")
      (node (ref "R8") (pin "2") (pinfunction "2_2") (pintype "unspecified"))
      (node (ref "U11A") (pin "9") (pinfunction "A8_9") (pintype "unspecified"))
    )
    (net (code "144") (name "Net-(U11A-G)") (class "Default")
      (node (ref "U11A") (pin "19") (pinfunction "G_19") (pintype "unspecified"))
      (node (ref "U11B") (pin "19") (pinfunction "G_19") (pintype "unspecified"))
      (node (ref "U5D") (pin "6") (pinfunction "1Q_6") (pintype "unspecified"))
    )
    (net (code "145") (name "Net-(U11C-G)") (class "Default")
      (node (ref "U11C") (pin "11") (pinfunction "G_11") (pintype "unspecified"))
      (node (ref "U15F") (pin "11") (pinfunction "/4Y_11") (pintype "unspecified"))
    )
    (net (code "146") (name "Net-(U11D-1D)") (class "Default")
      (node (ref "U11D") (pin "3") (pinfunction "1D_3") (pintype "unspecified"))
      (node (ref "U9B") (pin "4") (pinfunction "S1_4") (pintype "unspecified"))
      (node (ref "U9D") (pin "3") (pinfunction "1D_3") (pintype "unspecified"))
    )
    (net (code "147") (name "Net-(U11D-2D)") (class "Default")
      (node (ref "U11D") (pin "4") (pinfunction "2D_4") (pintype "unspecified"))
      (node (ref "U9B") (pin "1") (pinfunction "S2_1") (pintype "unspecified"))
      (node (ref "U9D") (pin "4") (pinfunction "2D_4") (pintype "unspecified"))
    )
    (net (code "148") (name "Net-(U11D-3D)") (class "Default")
      (node (ref "U11D") (pin "7") (pinfunction "3D_7") (pintype "unspecified"))
      (node (ref "U9B") (pin "13") (pinfunction "S3_13") (pintype "unspecified"))
      (node (ref "U9D") (pin "7") (pinfunction "3D_7") (pintype "unspecified"))
    )
    (net (code "149") (name "Net-(U11D-4D)") (class "Default")
      (node (ref "U11D") (pin "8") (pinfunction "4D_8") (pintype "unspecified"))
      (node (ref "U9B") (pin "10") (pinfunction "S4_10") (pintype "unspecified"))
      (node (ref "U9D") (pin "8") (pinfunction "4D_8") (pintype "unspecified"))
    )
    (net (code "150") (name "Net-(U11D-5D)") (class "Default")
      (node (ref "U11D") (pin "13") (pinfunction "5D_13") (pintype "unspecified"))
      (node (ref "U8B") (pin "4") (pinfunction "S1_4") (pintype "unspecified"))
    )
    (net (code "151") (name "Net-(U11D-6D)") (class "Default")
      (node (ref "U11D") (pin "14") (pinfunction "6D_14") (pintype "unspecified"))
      (node (ref "U8B") (pin "1") (pinfunction "S2_1") (pintype "unspecified"))
    )
    (net (code "152") (name "Net-(U11D-7D)") (class "Default")
      (node (ref "U11D") (pin "17") (pinfunction "7D_17") (pintype "unspecified"))
      (node (ref "U8B") (pin "13") (pinfunction "S3_13") (pintype "unspecified"))
    )
    (net (code "153") (name "Net-(U11D-8D)") (class "Default")
      (node (ref "U11D") (pin "18") (pinfunction "8D_18") (pintype "unspecified"))
      (node (ref "U8B") (pin "10") (pinfunction "S4_10") (pintype "unspecified"))
    )
    (net (code "154") (name "Net-(U12F-A0)") (class "Default")
      (node (ref "U12F") (pin "9") (pinfunction "A0_9") (pintype "unspecified"))
      (node (ref "U13A") (pin "25") (pinfunction "IPL0_25") (pintype "unspecified"))
    )
    (net (code "155") (name "Net-(U12F-A1)") (class "Default")
      (node (ref "U12F") (pin "7") (pinfunction "A1_7") (pintype "unspecified"))
      (node (ref "U13A") (pin "24") (pinfunction "IPL1_24") (pintype "unspecified"))
    )
    (net (code "156") (name "Net-(U12F-A2)") (class "Default")
      (node (ref "U12F") (pin "6") (pinfunction "A2_6") (pintype "unspecified"))
      (node (ref "U13A") (pin "23") (pinfunction "IPL2_23") (pintype "unspecified"))
    )
    (net (code "157") (name "Net-(U13A-E)") (class "Default")
      (node (ref "U13A") (pin "20") (pinfunction "E_20") (pintype "unspecified"))
      (node (ref "U8C") (pin "6") (pinfunction "1A3_6") (pintype "unspecified"))
    )
    (net (code "158") (name "Net-(U13A-LDS)") (class "Default")
      (node (ref "U13A") (pin "8") (pinfunction "LDS_8") (pintype "unspecified"))
      (node (ref "U8C") (pin "15") (pinfunction "2A3_15") (pintype "unspecified"))
    )
    (net (code "159") (name "Net-(U13A-READ)") (class "Default")
      (node (ref "U13A") (pin "9") (pinfunction "READ_9") (pintype "unspecified"))
      (node (ref "U8C") (pin "11") (pinfunction "2A1_11") (pintype "unspecified"))
    )
    (net (code "160") (name "Net-(U13A-RESET)") (class "Default")
      (node (ref "RP2") (pin "11") (pinfunction "+5V_11") (pintype "unspecified"))
      (node (ref "U13A") (pin "18") (pinfunction "RESET_18") (pintype "unspecified"))
      (node (ref "U2E") (pin "2") (pinfunction "1Y_2") (pintype "unspecified"))
      (node (ref "U2E") (pin "3") (pinfunction "2A_3") (pintype "unspecified"))
    )
    (net (code "161") (name "Net-(U13A-UDS)") (class "Default")
      (node (ref "U13A") (pin "7") (pinfunction "UDS_7") (pintype "unspecified"))
      (node (ref "U8C") (pin "17") (pinfunction "2A4_17") (pintype "unspecified"))
    )
    (net (code "162") (name "Net-(U13A-VMA)") (class "Default")
      (node (ref "U13A") (pin "19") (pinfunction "VMA_19") (pintype "unspecified"))
      (node (ref "U8C") (pin "8") (pinfunction "1A4_8") (pintype "unspecified"))
    )
    (net (code "163") (name "Net-(U13F-G1)") (class "Default")
      (node (ref "U13F") (pin "6") (pinfunction "G1_6") (pintype "unspecified"))
      (node (ref "U3A") (pin "10") (pinfunction "2Q_10") (pintype "unspecified"))
    )
    (net (code "164") (name "Net-(U14F-2Y0)") (class "Default")
      (node (ref "U14F") (pin "12") (pinfunction "2Y0_12") (pintype "unspecified"))
      (node (ref "U4E") (pin "14") (pinfunction "G_14") (pintype "unspecified"))
    )
    (net (code "165") (name "Net-(U15B-Q1)") (class "Default")
      (node (ref "U15B") (pin "5") (pinfunction "Q1_5") (pintype "unspecified"))
      (node (ref "U7A") (pin "1") (pinfunction "1A_1") (pintype "unspecified"))
      (node (ref "U7A") (pin "2") (pinfunction "1B_2") (pintype "unspecified"))
    )
    (net (code "166") (name "Net-(U15B-TH2)") (class "Default")
      (node (ref "C9") (pin "1") (pinfunction "1_1") (pintype "unspecified"))
      (node (ref "R3") (pin "1") (pinfunction "1_1") (pintype "unspecified"))
      (node (ref "U15B") (pin "12") (pinfunction "TH2_12") (pintype "unspecified"))
      (node (ref "U15B") (pin "8") (pinfunction "TR2_8") (pintype "unspecified"))
      (node (ref "U2E") (pin "12") (pinfunction "6Y_12") (pintype "unspecified"))
    )
    (net (code "167") (name "Net-(U15F-{slash}3Y)") (class "Default")
      (node (ref "U15F") (pin "8") (pinfunction "/3Y_8") (pintype "unspecified"))
      (node (ref "U9D") (pin "1") (pinfunction "OE_1") (pintype "unspecified"))
    )
    (net (code "168") (name "PCK") (class "Default")
      (node (ref "U13A") (pin "15") (pinfunction "PCK_15") (pintype "unspecified"))
      (node (ref "U1C") (pin "13") (pinfunction "QB_13") (pintype "unspecified"))
      (node (ref "U1D") (pin "2") (pinfunction "B_2") (pintype "unspecified"))
      (node (ref "U4D") (pin "13") (pinfunction "4B_13") (pintype "unspecified"))
      (node (ref "U5D") (pin "14") (pinfunction "2J_14") (pintype "unspecified"))
    )
    (net (code "169") (name "R1") (class "Default")
      (node (ref "CN1") (pin "71") (pinfunction "R1_71") (pintype "unspecified"))
      (node (ref "U15F") (pin "3") (pinfunction "/1Y_3") (pintype "unspecified"))
    )
    (net (code "170") (name "R2") (class "Default")
      (node (ref "CN1") (pin "72") (pinfunction "R2_72") (pintype "unspecified"))
      (node (ref "U2D") (pin "8") (pinfunction "Y3_8") (pintype "unspecified"))
    )
    (net (code "171") (name "RA1") (class "Default")
      (node (ref "CN1") (pin "93") (pinfunction "RA1_93") (pintype "unspecified"))
      (node (ref "U7E") (pin "7") (pinfunction "1Y_7") (pintype "unspecified"))
    )
    (net (code "172") (name "RA2") (class "Default")
      (node (ref "CN1") (pin "94") (pinfunction "RA2_94") (pintype "unspecified"))
      (node (ref "U7E") (pin "9") (pinfunction "2Y_9") (pintype "unspecified"))
    )
    (net (code "173") (name "RA3") (class "Default")
      (node (ref "CN1") (pin "95") (pinfunction "RA3_95") (pintype "unspecified"))
      (node (ref "U6E") (pin "7") (pinfunction "1Y_7") (pintype "unspecified"))
    )
    (net (code "174") (name "RA4") (class "Default")
      (node (ref "CN1") (pin "96") (pinfunction "RA4_96") (pintype "unspecified"))
      (node (ref "U6E") (pin "9") (pinfunction "2Y_9") (pintype "unspecified"))
    )
    (net (code "175") (name "RA5") (class "Default")
      (node (ref "CN1") (pin "97") (pinfunction "RA5_97") (pintype "unspecified"))
      (node (ref "U5F") (pin "7") (pinfunction "1Y_7") (pintype "unspecified"))
    )
    (net (code "176") (name "RA6") (class "Default")
      (node (ref "CN1") (pin "98") (pinfunction "RA6_98") (pintype "unspecified"))
      (node (ref "U5F") (pin "9") (pinfunction "2Y_9") (pintype "unspecified"))
    )
    (net (code "177") (name "RA7") (class "Default")
      (node (ref "CN1") (pin "99") (pinfunction "RA7_99") (pintype "unspecified"))
      (node (ref "U8E") (pin "7") (pinfunction "1Y_7") (pintype "unspecified"))
    )
    (net (code "178") (name "RA8") (class "Default")
      (node (ref "CN1") (pin "100") (pinfunction "RA8_100") (pintype "unspecified"))
      (node (ref "U8E") (pin "9") (pinfunction "2Y_9") (pintype "unspecified"))
    )
    (net (code "179") (name "RAS") (class "Default")
      (node (ref "U3C") (pin "7") (pinfunction "/1Q_7") (pintype "unspecified"))
      (node (ref "U5F") (pin "2") (pinfunction "B_2") (pintype "unspecified"))
      (node (ref "U6E") (pin "2") (pinfunction "B_2") (pintype "unspecified"))
      (node (ref "U7E") (pin "2") (pinfunction "B_2") (pintype "unspecified"))
      (node (ref "U8E") (pin "2") (pinfunction "B_2") (pintype "unspecified"))
    )
    (net (code "180") (name "READ") (class "Default")
      (node (ref "CN1") (pin "64") (pinfunction "READ_64") (pintype "unspecified"))
      (node (ref "RP2") (pin "15") (pinfunction "+5V_15") (pintype "unspecified"))
      (node (ref "U11A") (pin "1") (pinfunction "A+B_1") (pintype "unspecified"))
      (node (ref "U11B") (pin "1") (pinfunction "A+B_1") (pintype "unspecified"))
      (node (ref "U11F") (pin "1") (pinfunction "A-B_1") (pintype "unspecified"))
      (node (ref "U14E") (pin "1") (pinfunction "A-B_1") (pintype "unspecified"))
      (node (ref "U15E") (pin "1") (pinfunction "A-B_1") (pintype "unspecified"))
      (node (ref "U2D") (pin "1") (pinfunction "A1_1") (pintype "unspecified"))
      (node (ref "U2D") (pin "5") (pinfunction "B2_5") (pintype "unspecified"))
      (node (ref "U5B") (pin "6") (pinfunction "2B_6") (pintype "unspecified"))
      (node (ref "U8C") (pin "9") (pinfunction "2Y1_9") (pintype "unspecified"))
      (node (ref "U9F") (pin "1") (pinfunction "A-B_1") (pintype "unspecified"))
    )
    (net (code "181") (name "RP1_2") (class "Default")
      (node (ref "RP1") (pin "2") (pinfunction "+5V_2") (pintype "unspecified"))
      (node (ref "U1C") (pin "9") (pinfunction "LD_9") (pintype "unspecified"))
    )
    (net (code "182") (name "RP1_3") (class "Default")
      (node (ref "RP1") (pin "3") (pinfunction "+5V_3") (pintype "unspecified"))
      (node (ref "U9E") (pin "17") (pinfunction "2A4_17") (pintype "unspecified"))
    )
    (net (code "183") (name "RP1_4") (class "Default")
      (node (ref "CN1") (pin "24") (pinfunction "/BGACK_24") (pintype "unspecified"))
      (node (ref "RP1") (pin "4") (pinfunction "+5V_4") (pintype "unspecified"))
      (node (ref "U13A") (pin "12") (pinfunction "BGACK_12") (pintype "unspecified"))
      (node (ref "U15F") (pin "5") (pinfunction "2B_5") (pintype "unspecified"))
      (node (ref "U15F") (pin "9") (pinfunction "3A_9") (pintype "unspecified"))
      (node (ref "U6A") (pin "11") (pinfunction "4A_11") (pintype "unspecified"))
      (node (ref "U6A") (pin "12") (pinfunction "4B_12") (pintype "unspecified"))
    )
    (net (code "184") (name "RP1_5") (class "Default")
      (node (ref "RP1") (pin "5") (pinfunction "+5V_5") (pintype "unspecified"))
      (node (ref "U2B") (pin "1") (pinfunction "1CLR_1") (pintype "unspecified"))
      (node (ref "U2B") (pin "11") (pinfunction "2PR_11") (pintype "unspecified"))
      (node (ref "U2B") (pin "13") (pinfunction "2K_13") (pintype "unspecified"))
      (node (ref "U2B") (pin "5") (pinfunction "1PR_5") (pintype "unspecified"))
      (node (ref "U3A") (pin "11") (pinfunction "2PR_11") (pintype "unspecified"))
      (node (ref "U3B") (pin "13") (pinfunction "2K_13") (pintype "unspecified"))
      (node (ref "U3B") (pin "3") (pinfunction "1K_3") (pintype "unspecified"))
      (node (ref "U3B") (pin "5") (pinfunction "1PR_5") (pintype "unspecified"))
      (node (ref "U3C") (pin "1") (pinfunction "1CLR_1") (pintype "unspecified"))
      (node (ref "U3C") (pin "15") (pinfunction "2CLR_15") (pintype "unspecified"))
      (node (ref "U4B") (pin "11") (pinfunction "2PR_11") (pintype "unspecified"))
      (node (ref "U4B") (pin "15") (pinfunction "2CLR_15") (pintype "unspecified"))
      (node (ref "U4B") (pin "3") (pinfunction "1K_3") (pintype "unspecified"))
      (node (ref "U4B") (pin "5") (pinfunction "1PR_5") (pintype "unspecified"))
      (node (ref "U5D") (pin "1") (pinfunction "1CLR_1") (pintype "unspecified"))
      (node (ref "U5D") (pin "15") (pinfunction "2CLR_15") (pintype "unspecified"))
    )
    (net (code "185") (name "RP1_6") (class "Default")
      (node (ref "RP1") (pin "6") (pinfunction "+5V_6") (pintype "unspecified"))
      (node (ref "U1E") (pin "1") (pinfunction "1A_1") (pintype "unspecified"))
    )
    (net (code "186") (name "RP1_7") (class "Default")
      (node (ref "CN1") (pin "63") (pinfunction "/AS_63") (pintype "unspecified"))
      (node (ref "RP1") (pin "7") (pinfunction "+5V_7") (pintype "unspecified"))
      (node (ref "U2C") (pin "4") (pinfunction "2A_4") (pintype "unspecified"))
      (node (ref "U6A") (pin "2") (pinfunction "1A_2") (pintype "unspecified"))
      (node (ref "U6A") (pin "3") (pinfunction "1B_3") (pintype "unspecified"))
      (node (ref "U8C") (pin "7") (pinfunction "2Y2_7") (pintype "unspecified"))
    )
    (net (code "187") (name "RP1_8") (class "Default")
      (node (ref "RP1") (pin "8") (pinfunction "+5V_8") (pintype "unspecified"))
      (node (ref "U1E") (pin "5") (pinfunction "2B_5") (pintype "unspecified"))
      (node (ref "U1E") (pin "9") (pinfunction "3A_9") (pintype "unspecified"))
    )
    (net (code "188") (name "RP1_11") (class "Default")
      (node (ref "RP1") (pin "11") (pinfunction "+5V_11") (pintype "unspecified"))
      (node (ref "U1C") (pin "1") (pinfunction "U-D_1") (pintype "unspecified"))
      (node (ref "U1D") (pin "6") (pinfunction "G1_6") (pintype "unspecified"))
    )
    (net (code "189") (name "RP1_12") (class "Default")
      (node (ref "RP1") (pin "12") (pinfunction "+5V_12") (pintype "unspecified"))
      (node (ref "U13A") (pin "17") (pinfunction "HALT_17") (pintype "unspecified"))
      (node (ref "U2E") (pin "1") (pinfunction "1A_1") (pintype "unspecified"))
      (node (ref "U4E") (pin "15") (pinfunction "CLR_15") (pintype "unspecified"))
      (node (ref "U7A") (pin "3") (pinfunction "1Y_3") (pintype "unspecified"))
    )
    (net (code "190") (name "RP2_1") (class "Default")
      (node (ref "CN1") (pin "65") (pinfunction "/LDS_65") (pintype "unspecified"))
      (node (ref "RP2") (pin "1") (pinfunction "+5V_1") (pintype "unspecified"))
      (node (ref "U8C") (pin "5") (pinfunction "2Y3_5") (pintype "unspecified"))
    )
    (net (code "191") (name "RP2_2") (class "Default")
      (node (ref "CN1") (pin "66") (pinfunction "/UDS_66") (pintype "unspecified"))
      (node (ref "RP2") (pin "2") (pinfunction "+5V_2") (pintype "unspecified"))
      (node (ref "U8C") (pin "3") (pinfunction "2Y4_3") (pintype "unspecified"))
    )
    (net (code "192") (name "RP2_3") (class "Default")
      (node (ref "RP2") (pin "3") (pinfunction "+5V_3") (pintype "unspecified"))
      (node (ref "U13A") (pin "6") (pinfunction "AS_6") (pintype "unspecified"))
      (node (ref "U13F") (pin "4") (pinfunction "G2A_4") (pintype "unspecified"))
      (node (ref "U2D") (pin "13") (pinfunction "B4_13") (pintype "unspecified"))
      (node (ref "U8C") (pin "13") (pinfunction "2A2_13") (pintype "unspecified"))
    )
    (net (code "193") (name "RP2_6") (class "Default")
      (node (ref "CN1") (pin "116") (pinfunction "/NMI_116") (pintype "unspecified"))
      (node (ref "RP2") (pin "6") (pinfunction "+5V_6") (pintype "unspecified"))
      (node (ref "U10C") (pin "13") (pinfunction "1C_13") (pintype "unspecified"))
    )
    (net (code "194") (name "SEG1") (class "Default")
      (node (ref "U4E") (pin "6") (pinfunction "Q2_6") (pintype "unspecified"))
      (node (ref "U7C") (pin "5") (pinfunction "2B_5") (pintype "unspecified"))
    )
    (net (code "195") (name "SEG2") (class "Default")
      (node (ref "U4E") (pin "7") (pinfunction "Q3_7") (pintype "unspecified"))
      (node (ref "U7C") (pin "9") (pinfunction "3A_9") (pintype "unspecified"))
    )
    (net (code "196") (name "SN") (class "Default")
      (node (ref "R8") (pin "1") (pinfunction "1_1") (pintype "unspecified"))
      (node (ref "U6C") (pin "14") (pinfunction "D7_14") (pintype "unspecified"))
    )
    (net (code "197") (name "SPIO") (class "Default")
      (node (ref "U2C") (pin "13") (pinfunction "1E_13") (pintype "unspecified"))
      (node (ref "U3B") (pin "6") (pinfunction "1Q_6") (pintype "unspecified"))
      (node (ref "U6A") (pin "9") (pinfunction "3B_9") (pintype "unspecified"))
    )
    (net (code "198") (name "TD0") (class "Default")
      (node (ref "U11B") (pin "2") (pinfunction "A1_2") (pintype "unspecified"))
      (node (ref "U8A") (pin "14") (pinfunction "VO1_14") (pintype "unspecified"))
      (node (ref "U8B") (pin "5") (pinfunction "A1_5") (pintype "unspecified"))
    )
    (net (code "199") (name "TD1") (class "Default")
      (node (ref "U11B") (pin "3") (pinfunction "A2_3") (pintype "unspecified"))
      (node (ref "U8A") (pin "13") (pinfunction "VO2_13") (pintype "unspecified"))
      (node (ref "U8B") (pin "3") (pinfunction "A2_3") (pintype "unspecified"))
    )
    (net (code "200") (name "TD2") (class "Default")
      (node (ref "U11B") (pin "4") (pinfunction "A3_4") (pintype "unspecified"))
      (node (ref "U8A") (pin "12") (pinfunction "VO3_12") (pintype "unspecified"))
      (node (ref "U8B") (pin "14") (pinfunction "A3_14") (pintype "unspecified"))
    )
    (net (code "201") (name "TD3") (class "Default")
      (node (ref "U11B") (pin "5") (pinfunction "A4_5") (pintype "unspecified"))
      (node (ref "U8A") (pin "11") (pinfunction "VO4_11") (pintype "unspecified"))
      (node (ref "U8B") (pin "12") (pinfunction "A4_12") (pintype "unspecified"))
    )
    (net (code "202") (name "TD4") (class "Default")
      (node (ref "U11B") (pin "6") (pinfunction "A5_6") (pintype "unspecified"))
      (node (ref "U9A") (pin "14") (pinfunction "VO1_14") (pintype "unspecified"))
      (node (ref "U9B") (pin "5") (pinfunction "A1_5") (pintype "unspecified"))
    )
    (net (code "203") (name "TD5") (class "Default")
      (node (ref "U11B") (pin "7") (pinfunction "A6_7") (pintype "unspecified"))
      (node (ref "U9A") (pin "13") (pinfunction "VO2_13") (pintype "unspecified"))
      (node (ref "U9B") (pin "3") (pinfunction "A2_3") (pintype "unspecified"))
    )
    (net (code "204") (name "TD6") (class "Default")
      (node (ref "U11B") (pin "8") (pinfunction "A7_8") (pintype "unspecified"))
      (node (ref "U9A") (pin "12") (pinfunction "VO3_12") (pintype "unspecified"))
      (node (ref "U9B") (pin "14") (pinfunction "A3_14") (pintype "unspecified"))
    )
    (net (code "205") (name "TD7") (class "Default")
      (node (ref "U11B") (pin "9") (pinfunction "A8_9") (pintype "unspecified"))
      (node (ref "U9A") (pin "11") (pinfunction "VO4_11") (pintype "unspecified"))
      (node (ref "U9B") (pin "12") (pinfunction "A4_12") (pintype "unspecified"))
    )
    (net (code "206") (name "U1A_2") (class "Default")
      (node (ref "U11E") (pin "3") (pinfunction "1D_3") (pintype "unspecified"))
      (node (ref "U1A") (pin "2") (pinfunction "B1_2") (pintype "unspecified"))
      (node (ref "U1B") (pin "9") (pinfunction "4A_9") (pintype "unspecified"))
      (node (ref "U1C") (pin "11") (pinfunction "QD_11") (pintype "unspecified"))
      (node (ref "U3A") (pin "3") (pinfunction "1K_3") (pintype "unspecified"))
      (node (ref "U4A") (pin "12") (pinfunction "4A_12") (pintype "unspecified"))
      (node (ref "U6B") (pin "11") (pinfunction "G_11") (pintype "unspecified"))
      (node (ref "U7B") (pin "1") (pinfunction "1ACLK_1") (pintype "unspecified"))
    )
    (net (code "207") (name "U1A_3") (class "Default")
      (node (ref "U1A") (pin "3") (pinfunction "Y1_3") (pintype "unspecified"))
      (node (ref "U3C") (pin "5") (pinfunction "1PR_5") (pintype "unspecified"))
    )
    (net (code "208") (name "U1B_1") (class "Default")
      (node (ref "U1B") (pin "1") (pinfunction "1A_1") (pintype "unspecified"))
      (node (ref "U1D") (pin "10") (pinfunction "Y5_10") (pintype "unspecified"))
    )
    (net (code "209") (name "U1B_2") (class "Default")
      (node (ref "U1B") (pin "2") (pinfunction "/1Y_2") (pintype "unspecified"))
      (node (ref "U3C") (pin "2") (pinfunction "1J_2") (pintype "unspecified"))
    )
    (net (code "210") (name "U1B_3") (class "Default")
      (node (ref "U1B") (pin "3") (pinfunction "2A_3") (pintype "unspecified"))
      (node (ref "U1D") (pin "9") (pinfunction "Y6_9") (pintype "unspecified"))
      (node (ref "U3E") (pin "2") (pinfunction "1J_2") (pintype "unspecified"))
      (node (ref "U3E") (pin "3") (pinfunction "1K_3") (pintype "unspecified"))
      (node (ref "U4B") (pin "13") (pinfunction "2K_13") (pintype "unspecified"))
      (node (ref "U6A") (pin "6") (pinfunction "2B_6") (pintype "unspecified"))
    )
    (net (code "211") (name "U1B_4") (class "Default")
      (node (ref "U1B") (pin "4") (pinfunction "/2Y_4") (pintype "unspecified"))
      (node (ref "U3C") (pin "14") (pinfunction "2J_14") (pintype "unspecified"))
    )
    (net (code "212") (name "U1B_8") (class "Default")
      (node (ref "U1B") (pin "8") (pinfunction "/4Y_8") (pintype "unspecified"))
      (node (ref "U2B") (pin "3") (pinfunction "1K_3") (pintype "unspecified"))
      (node (ref "U5A") (pin "3") (pinfunction "2A_3") (pintype "unspecified"))
      (node (ref "U6A") (pin "5") (pinfunction "2A_5") (pintype "unspecified"))
    )
    (net (code "213") (name "U1B_13") (class "Default")
      (node (ref "U14F") (pin "5") (pinfunction "1Y1_5") (pintype "unspecified"))
      (node (ref "U1B") (pin "13") (pinfunction "6A_13") (pintype "unspecified"))
      (node (ref "U7C") (pin "1") (pinfunction "1A_1") (pintype "unspecified"))
    )
    (net (code "214") (name "U1E_2") (class "Default")
      (node (ref "Q2") (pin "3") (pinfunction "3_3") (pintype "unspecified"))
      (node (ref "R13") (pin "2") (pinfunction "2_2") (pintype "unspecified"))
      (node (ref "U1E") (pin "2") (pinfunction "1B_2") (pintype "unspecified"))
    )
    (net (code "215") (name "U1E_12") (class "Default")
      (node (ref "U1E") (pin "12") (pinfunction "4A_12") (pintype "unspecified"))
      (node (ref "U1E") (pin "13") (pinfunction "4B_13") (pintype "unspecified"))
      (node (ref "U5B") (pin "4") (pinfunction "2Y_4") (pintype "unspecified"))
      (node (ref "U7A") (pin "12") (pinfunction "4A_12") (pintype "unspecified"))
      (node (ref "U7A") (pin "9") (pinfunction "3A_9") (pintype "unspecified"))
    )
    (net (code "216") (name "U2E_5") (class "Default")
      (node (ref "U2E") (pin "5") (pinfunction "3A_5") (pintype "unspecified"))
      (node (ref "U3A") (pin "6") (pinfunction "1Q_6") (pintype "unspecified"))
    )
    (net (code "217") (name "U2E_6") (class "Default")
      (node (ref "CN1") (pin "62") (pinfunction "/DTACK_62") (pintype "unspecified"))
      (node (ref "R1") (pin "1") (pinfunction "1_1") (pintype "unspecified"))
      (node (ref "U2E") (pin "6") (pinfunction "3Y_6") (pintype "unspecified"))
      (node (ref "U2E") (pin "8") (pinfunction "4Y_8") (pintype "unspecified"))
      (node (ref "U3A") (pin "1") (pinfunction "1CLR_1") (pintype "unspecified"))
    )
    (net (code "218") (name "U2E_9") (class "Default")
      (node (ref "U13F") (pin "7") (pinfunction "Y7_7") (pintype "unspecified"))
      (node (ref "U14F") (pin "15") (pinfunction "2G_15") (pintype "unspecified"))
      (node (ref "U2E") (pin "9") (pinfunction "4A_9") (pintype "unspecified"))
    )
    (net (code "219") (name "U3D_11") (class "Default")
      (node (ref "U1B") (pin "10") (pinfunction "/5Y_10") (pintype "unspecified"))
      (node (ref "U3D") (pin "11") (pinfunction "2E_11") (pintype "unspecified"))
    )
    (net (code "220") (name "U4D_6") (class "Default")
      (node (ref "U15F") (pin "2") (pinfunction "1B_2") (pintype "unspecified"))
      (node (ref "U2D") (pin "9") (pinfunction "A3_9") (pintype "unspecified"))
      (node (ref "U4D") (pin "6") (pinfunction "2Y_6") (pintype "unspecified"))
    )
    (net (code "221") (name "U5A_2") (class "Default")
      (node (ref "U2D") (pin "3") (pinfunction "Y1_3") (pintype "unspecified"))
      (node (ref "U5A") (pin "2") (pinfunction "1B_2") (pintype "unspecified"))
    )
    (net (code "222") (name "U5A_6") (class "Default")
      (node (ref "U3C") (pin "11") (pinfunction "2PR_11") (pintype "unspecified"))
      (node (ref "U5A") (pin "6") (pinfunction "2Y_6") (pintype "unspecified"))
    )
    (net (code "223") (name "U5A_13") (class "Default")
      (node (ref "U4D") (pin "3") (pinfunction "1Y_3") (pintype "unspecified"))
      (node (ref "U5A") (pin "13") (pinfunction "1C_13") (pintype "unspecified"))
    )
    (net (code "224") (name "U5B_1") (class "Default")
      (node (ref "U3D") (pin "4") (pinfunction "2A_4") (pintype "unspecified"))
      (node (ref "U5A") (pin "1") (pinfunction "1A_1") (pintype "unspecified"))
      (node (ref "U5B") (pin "1") (pinfunction "1Y_1") (pintype "unspecified"))
    )
    (net (code "225") (name "U5B_3") (class "Default")
      (node (ref "U2B") (pin "7") (pinfunction "/1Q_7") (pintype "unspecified"))
      (node (ref "U2C") (pin "3") (pinfunction "1C_3") (pintype "unspecified"))
      (node (ref "U3D") (pin "13") (pinfunction "1E_13") (pintype "unspecified"))
      (node (ref "U3D") (pin "9") (pinfunction "2C_9") (pintype "unspecified"))
      (node (ref "U5B") (pin "3") (pinfunction "1B_3") (pintype "unspecified"))
      (node (ref "U5B") (pin "5") (pinfunction "2A_5") (pintype "unspecified"))
    )
    (net (code "226") (name "U5D_13") (class "Default")
      (node (ref "U2D") (pin "6") (pinfunction "Y2_6") (pintype "unspecified"))
      (node (ref "U5D") (pin "13") (pinfunction "2K_13") (pintype "unspecified"))
    )
    (net (code "227") (name "U6A_4") (class "Default")
      (node (ref "U4B") (pin "14") (pinfunction "2J_14") (pintype "unspecified"))
      (node (ref "U6A") (pin "4") (pinfunction "2Y_4") (pintype "unspecified"))
    )
    (net (code "228") (name "U6A_8") (class "Default")
      (node (ref "U3A") (pin "7") (pinfunction "/1Q_7") (pintype "unspecified"))
      (node (ref "U6A") (pin "8") (pinfunction "3A_8") (pintype "unspecified"))
    )
    (net (code "229") (name "U6D_1") (class "Default")
      (node (ref "U6B") (pin "15") (pinfunction "6Q_15") (pintype "unspecified"))
      (node (ref "U6D") (pin "1") (pinfunction "1A_1") (pintype "unspecified"))
    )
    (net (code "230") (name "U6D_2") (class "Default")
      (node (ref "U5E") (pin "9") (pinfunction "2QC_9") (pintype "unspecified"))
      (node (ref "U6C") (pin "19") (pinfunction "A7_19") (pintype "unspecified"))
      (node (ref "U6D") (pin "2") (pinfunction "1B_2") (pintype "unspecified"))
      (node (ref "U7F") (pin "6") (pinfunction "INH_6") (pintype "unspecified"))
      (node (ref "U8F") (pin "6") (pinfunction "INH_6") (pintype "unspecified"))
    )
    (net (code "231") (name "U7A_10") (class "Default")
      (node (ref "U4E") (pin "4") (pinfunction "Q0_4") (pintype "unspecified"))
      (node (ref "U7A") (pin "10") (pinfunction "3B_10") (pintype "unspecified"))
    )
    (net (code "232") (name "U7A_13") (class "Default")
      (node (ref "U4E") (pin "5") (pinfunction "Q1_5") (pintype "unspecified"))
      (node (ref "U7A") (pin "13") (pinfunction "4B_13") (pintype "unspecified"))
    )
    (net (code "233") (name "U7C_11") (class "Default")
      (node (ref "U5A") (pin "4") (pinfunction "2B_4") (pintype "unspecified"))
      (node (ref "U7C") (pin "11") (pinfunction "/4Y_11") (pintype "unspecified"))
    )
    (net (code "234") (name "U8C_2") (class "Default")
      (node (ref "U5E") (pin "3") (pinfunction "1QA_3") (pintype "unspecified"))
      (node (ref "U6C") (pin "18") (pinfunction "A6_18") (pintype "unspecified"))
      (node (ref "U7E") (pin "3") (pinfunction "1C3_3") (pintype "unspecified"))
      (node (ref "U8C") (pin "2") (pinfunction "1A1_2") (pintype "unspecified"))
    )
    (net (code "235") (name "U8C_4") (class "Default")
      (node (ref "U5E") (pin "4") (pinfunction "1QB_4") (pintype "unspecified"))
      (node (ref "U7E") (pin "13") (pinfunction "2C3_13") (pintype "unspecified"))
      (node (ref "U8C") (pin "4") (pinfunction "1A2_4") (pintype "unspecified"))
    )
    (net (code "236") (name "U15F_4") (class "Default")
      (node (ref "U14F") (pin "1") (pinfunction "1G_1") (pintype "unspecified"))
      (node (ref "U15F") (pin "4") (pinfunction "2A_4") (pintype "unspecified"))
      (node (ref "U3B") (pin "7") (pinfunction "/1Q_7") (pintype "unspecified"))
      (node (ref "U5A") (pin "11") (pinfunction "3C_11") (pintype "unspecified"))
    )
    (net (code "237") (name "UA1") (class "Default")
      (node (ref "U13A") (pin "29") (pinfunction "A1_29") (pintype "unspecified"))
      (node (ref "U13D") (pin "10") (pinfunction "A0_10") (pintype "unspecified"))
      (node (ref "U14D") (pin "10") (pinfunction "A0_10") (pintype "unspecified"))
      (node (ref "U15C") (pin "17") (pinfunction "2A4_17") (pintype "unspecified"))
    )
    (net (code "238") (name "UA2") (class "Default")
      (node (ref "U13A") (pin "30") (pinfunction "A2_30") (pintype "unspecified"))
      (node (ref "U13D") (pin "9") (pinfunction "A1_9") (pintype "unspecified"))
      (node (ref "U14D") (pin "9") (pinfunction "A1_9") (pintype "unspecified"))
      (node (ref "U15C") (pin "15") (pinfunction "2A3_15") (pintype "unspecified"))
    )
    (net (code "239") (name "UA3") (class "Default")
      (node (ref "U13A") (pin "31") (pinfunction "A3_31") (pintype "unspecified"))
      (node (ref "U13D") (pin "8") (pinfunction "A2_8") (pintype "unspecified"))
      (node (ref "U14D") (pin "8") (pinfunction "A2_8") (pintype "unspecified"))
      (node (ref "U15C") (pin "13") (pinfunction "2A2_13") (pintype "unspecified"))
      (node (ref "U6D") (pin "13") (pinfunction "4B_13") (pintype "unspecified"))
    )
    (net (code "240") (name "UA4") (class "Default")
      (node (ref "U13A") (pin "32") (pinfunction "A4_32") (pintype "unspecified"))
      (node (ref "U13D") (pin "7") (pinfunction "A3_7") (pintype "unspecified"))
      (node (ref "U14D") (pin "7") (pinfunction "A3_7") (pintype "unspecified"))
      (node (ref "U15C") (pin "11") (pinfunction "2A1_11") (pintype "unspecified"))
    )
    (net (code "241") (name "UA5") (class "Default")
      (node (ref "U13A") (pin "33") (pinfunction "A5_33") (pintype "unspecified"))
      (node (ref "U13D") (pin "6") (pinfunction "A4_6") (pintype "unspecified"))
      (node (ref "U14D") (pin "6") (pinfunction "A4_6") (pintype "unspecified"))
      (node (ref "U15C") (pin "8") (pinfunction "1A4_8") (pintype "unspecified"))
    )
    (net (code "242") (name "UA6") (class "Default")
      (node (ref "U13A") (pin "34") (pinfunction "A6_34") (pintype "unspecified"))
      (node (ref "U13D") (pin "5") (pinfunction "A5_5") (pintype "unspecified"))
      (node (ref "U14D") (pin "5") (pinfunction "A5_5") (pintype "unspecified"))
      (node (ref "U15C") (pin "6") (pinfunction "1A3_6") (pintype "unspecified"))
    )
    (net (code "243") (name "UA7") (class "Default")
      (node (ref "U13A") (pin "35") (pinfunction "A7_35") (pintype "unspecified"))
      (node (ref "U13D") (pin "4") (pinfunction "A6_4") (pintype "unspecified"))
      (node (ref "U14D") (pin "4") (pinfunction "A6_4") (pintype "unspecified"))
      (node (ref "U15C") (pin "4") (pinfunction "1A2_4") (pintype "unspecified"))
    )
    (net (code "244") (name "UA8") (class "Default")
      (node (ref "U13A") (pin "36") (pinfunction "A8_36") (pintype "unspecified"))
      (node (ref "U13D") (pin "3") (pinfunction "A7_3") (pintype "unspecified"))
      (node (ref "U14D") (pin "3") (pinfunction "A7_3") (pintype "unspecified"))
      (node (ref "U15C") (pin "2") (pinfunction "1A1_2") (pintype "unspecified"))
    )
    (net (code "245") (name "UA9") (class "Default")
      (node (ref "U13A") (pin "37") (pinfunction "A9_37") (pintype "unspecified"))
      (node (ref "U13D") (pin "25") (pinfunction "A8_25") (pintype "unspecified"))
      (node (ref "U14D") (pin "25") (pinfunction "A8_25") (pintype "unspecified"))
      (node (ref "U8B") (pin "6") (pinfunction "B1_6") (pintype "unspecified"))
    )
    (net (code "246") (name "UA10") (class "Default")
      (node (ref "U13A") (pin "38") (pinfunction "A10_38") (pintype "unspecified"))
      (node (ref "U13D") (pin "24") (pinfunction "A9_24") (pintype "unspecified"))
      (node (ref "U14D") (pin "24") (pinfunction "A9_24") (pintype "unspecified"))
      (node (ref "U8B") (pin "2") (pinfunction "B2_2") (pintype "unspecified"))
    )
    (net (code "247") (name "UA11") (class "Default")
      (node (ref "U13A") (pin "39") (pinfunction "A11_39") (pintype "unspecified"))
      (node (ref "U13D") (pin "21") (pinfunction "A10_21") (pintype "unspecified"))
      (node (ref "U14D") (pin "21") (pinfunction "A10_21") (pintype "unspecified"))
      (node (ref "U8B") (pin "15") (pinfunction "B3_15") (pintype "unspecified"))
    )
    (net (code "248") (name "UA12") (class "Default")
      (node (ref "J1") (pin "2") (pinfunction "2_2") (pintype "unspecified"))
      (node (ref "U13A") (pin "40") (pinfunction "A12_40") (pintype "unspecified"))
      (node (ref "U13D") (pin "23") (pinfunction "A11_23") (pintype "unspecified"))
      (node (ref "U14D") (pin "23") (pinfunction "A11_23") (pintype "unspecified"))
      (node (ref "U8B") (pin "11") (pinfunction "B4_11") (pintype "unspecified"))
    )
    (net (code "249") (name "UA13") (class "Default")
      (node (ref "U13A") (pin "41") (pinfunction "A13_41") (pintype "unspecified"))
      (node (ref "U13D") (pin "2") (pinfunction "A12_2") (pintype "unspecified"))
      (node (ref "U14D") (pin "2") (pinfunction "A12_2") (pintype "unspecified"))
      (node (ref "U9B") (pin "6") (pinfunction "B1_6") (pintype "unspecified"))
    )
    (net (code "250") (name "UA14") (class "Default")
      (node (ref "U13A") (pin "42") (pinfunction "A14_42") (pintype "unspecified"))
      (node (ref "U5B") (pin "12") (pinfunction "4B_12") (pintype "unspecified"))
      (node (ref "U9B") (pin "2") (pinfunction "B2_2") (pintype "unspecified"))
    )
    (net (code "251") (name "UA15") (class "Default")
      (node (ref "U13A") (pin "43") (pinfunction "A15_43") (pintype "unspecified"))
      (node (ref "U14F") (pin "2") (pinfunction "1A_2") (pintype "unspecified"))
      (node (ref "U9B") (pin "15") (pinfunction "B3_15") (pintype "unspecified"))
    )
    (net (code "252") (name "UA16") (class "Default")
      (node (ref "U13A") (pin "44") (pinfunction "A16_44") (pintype "unspecified"))
      (node (ref "U14F") (pin "3") (pinfunction "1B_3") (pintype "unspecified"))
      (node (ref "U9B") (pin "11") (pinfunction "B4_11") (pintype "unspecified"))
    )
    (net (code "253") (name "UA17") (class "Default")
      (node (ref "U10A") (pin "17") (pinfunction "A7_17") (pintype "unspecified"))
      (node (ref "U13A") (pin "45") (pinfunction "A17_45") (pintype "unspecified"))
      (node (ref "U8A") (pin "17") (pinfunction "A7_17") (pintype "unspecified"))
      (node (ref "U9A") (pin "17") (pinfunction "A7_17") (pintype "unspecified"))
    )
    (net (code "254") (name "UA18") (class "Default")
      (node (ref "U10A") (pin "16") (pinfunction "A8_16") (pintype "unspecified"))
      (node (ref "U13A") (pin "46") (pinfunction "A18_46") (pintype "unspecified"))
      (node (ref "U8A") (pin "16") (pinfunction "A8_16") (pintype "unspecified"))
      (node (ref "U9A") (pin "16") (pinfunction "A8_16") (pintype "unspecified"))
    )
    (net (code "255") (name "UA19") (class "Default")
      (node (ref "U10A") (pin "15") (pinfunction "A9_15") (pintype "unspecified"))
      (node (ref "U13A") (pin "47") (pinfunction "A19_47") (pintype "unspecified"))
      (node (ref "U8A") (pin "15") (pinfunction "A9_15") (pintype "unspecified"))
      (node (ref "U9A") (pin "15") (pinfunction "A9_15") (pintype "unspecified"))
    )
    (net (code "256") (name "UA20") (class "Default")
      (node (ref "U10A") (pin "7") (pinfunction "A2_7") (pintype "unspecified"))
      (node (ref "U13A") (pin "48") (pinfunction "A20_48") (pintype "unspecified"))
      (node (ref "U8A") (pin "7") (pinfunction "A2_7") (pintype "unspecified"))
      (node (ref "U9A") (pin "7") (pinfunction "A2_7") (pintype "unspecified"))
    )
    (net (code "257") (name "UA21") (class "Default")
      (node (ref "U10A") (pin "1") (pinfunction "A6_1") (pintype "unspecified"))
      (node (ref "U13A") (pin "50") (pinfunction "A21_50") (pintype "unspecified"))
      (node (ref "U8A") (pin "1") (pinfunction "A6_1") (pintype "unspecified"))
      (node (ref "U9A") (pin "1") (pinfunction "A6_1") (pintype "unspecified"))
    )
    (net (code "258") (name "UA22") (class "Default")
      (node (ref "U10A") (pin "2") (pinfunction "A5_2") (pintype "unspecified"))
      (node (ref "U13A") (pin "51") (pinfunction "A22_51") (pintype "unspecified"))
      (node (ref "U8A") (pin "2") (pinfunction "A5_2") (pintype "unspecified"))
      (node (ref "U9A") (pin "2") (pinfunction "A5_2") (pintype "unspecified"))
    )
    (net (code "259") (name "UA23") (class "Default")
      (node (ref "U10A") (pin "3") (pinfunction "A4_3") (pintype "unspecified"))
      (node (ref "U13A") (pin "52") (pinfunction "A23_52") (pintype "unspecified"))
      (node (ref "U8A") (pin "3") (pinfunction "A4_3") (pintype "unspecified"))
      (node (ref "U9A") (pin "3") (pinfunction "A4_3") (pintype "unspecified"))
    )
    (net (code "260") (name "UD0") (class "Default")
      (node (ref "U11B") (pin "18") (pinfunction "B1_18") (pintype "unspecified"))
      (node (ref "U11C") (pin "7") (pinfunction "3D_7") (pintype "unspecified"))
      (node (ref "U13A") (pin "5") (pinfunction "D0_5") (pintype "unspecified"))
      (node (ref "U14D") (pin "11") (pinfunction "O0_11") (pintype "unspecified"))
      (node (ref "U15E") (pin "18") (pinfunction "B1_18") (pintype "unspecified"))
    )
    (net (code "261") (name "UD1") (class "Default")
      (node (ref "U11B") (pin "17") (pinfunction "B2_17") (pintype "unspecified"))
      (node (ref "U11C") (pin "8") (pinfunction "4D_8") (pintype "unspecified"))
      (node (ref "U13A") (pin "4") (pinfunction "D1_4") (pintype "unspecified"))
      (node (ref "U14D") (pin "12") (pinfunction "O1_12") (pintype "unspecified"))
      (node (ref "U15E") (pin "17") (pinfunction "B2_17") (pintype "unspecified"))
    )
    (net (code "262") (name "UD2") (class "Default")
      (node (ref "U11B") (pin "16") (pinfunction "B3_16") (pintype "unspecified"))
      (node (ref "U11C") (pin "13") (pinfunction "5D_13") (pintype "unspecified"))
      (node (ref "U13A") (pin "3") (pinfunction "D2_3") (pintype "unspecified"))
      (node (ref "U14D") (pin "13") (pinfunction "O2_13") (pintype "unspecified"))
      (node (ref "U15E") (pin "16") (pinfunction "B3_16") (pintype "unspecified"))
    )
    (net (code "263") (name "UD3") (class "Default")
      (node (ref "U11B") (pin "15") (pinfunction "B4_15") (pintype "unspecified"))
      (node (ref "U11C") (pin "14") (pinfunction "6D_14") (pintype "unspecified"))
      (node (ref "U13A") (pin "2") (pinfunction "D3_2") (pintype "unspecified"))
      (node (ref "U14D") (pin "15") (pinfunction "O3_15") (pintype "unspecified"))
      (node (ref "U15E") (pin "15") (pinfunction "B4_15") (pintype "unspecified"))
    )
    (net (code "264") (name "UD4") (class "Default")
      (node (ref "U11B") (pin "14") (pinfunction "B5_14") (pintype "unspecified"))
      (node (ref "U11C") (pin "17") (pinfunction "7D_17") (pintype "unspecified"))
      (node (ref "U13A") (pin "1") (pinfunction "D4_1") (pintype "unspecified"))
      (node (ref "U14D") (pin "16") (pinfunction "O4_16") (pintype "unspecified"))
      (node (ref "U15E") (pin "14") (pinfunction "B5_14") (pintype "unspecified"))
    )
    (net (code "265") (name "UD5") (class "Default")
      (node (ref "U11B") (pin "13") (pinfunction "B6_13") (pintype "unspecified"))
      (node (ref "U11C") (pin "18") (pinfunction "8D_18") (pintype "unspecified"))
      (node (ref "U13A") (pin "64") (pinfunction "D5_64") (pintype "unspecified"))
      (node (ref "U14D") (pin "17") (pinfunction "O5_17") (pintype "unspecified"))
      (node (ref "U15E") (pin "13") (pinfunction "B6_13") (pintype "unspecified"))
    )
    (net (code "266") (name "UD6") (class "Default")
      (node (ref "U11B") (pin "12") (pinfunction "B7_12") (pintype "unspecified"))
      (node (ref "U13A") (pin "63") (pinfunction "D6_63") (pintype "unspecified"))
      (node (ref "U14D") (pin "18") (pinfunction "O6_18") (pintype "unspecified"))
      (node (ref "U15E") (pin "12") (pinfunction "B7_12") (pintype "unspecified"))
    )
    (net (code "267") (name "UD7") (class "Default")
      (node (ref "U11B") (pin "11") (pinfunction "B8_11") (pintype "unspecified"))
      (node (ref "U13A") (pin "62") (pinfunction "D7_62") (pintype "unspecified"))
      (node (ref "U14D") (pin "19") (pinfunction "O7_19") (pintype "unspecified"))
      (node (ref "U15E") (pin "11") (pinfunction "B8_11") (pintype "unspecified"))
    )
    (net (code "268") (name "UD8") (class "Default")
      (node (ref "U11A") (pin "18") (pinfunction "B1_18") (pintype "unspecified"))
      (node (ref "U13A") (pin "61") (pinfunction "D8_61") (pintype "unspecified"))
      (node (ref "U13D") (pin "11") (pinfunction "O0_11") (pintype "unspecified"))
      (node (ref "U14E") (pin "18") (pinfunction "B1_18") (pintype "unspecified"))
    )
    (net (code "269") (name "UD9") (class "Default")
      (node (ref "U11A") (pin "17") (pinfunction "B2_17") (pintype "unspecified"))
      (node (ref "U13A") (pin "60") (pinfunction "D9_60") (pintype "unspecified"))
      (node (ref "U13D") (pin "12") (pinfunction "O1_12") (pintype "unspecified"))
      (node (ref "U14E") (pin "17") (pinfunction "B2_17") (pintype "unspecified"))
    )
    (net (code "270") (name "UD10") (class "Default")
      (node (ref "U11A") (pin "16") (pinfunction "B3_16") (pintype "unspecified"))
      (node (ref "U13A") (pin "59") (pinfunction "D10_59") (pintype "unspecified"))
      (node (ref "U13D") (pin "13") (pinfunction "O2_13") (pintype "unspecified"))
      (node (ref "U14E") (pin "16") (pinfunction "B3_16") (pintype "unspecified"))
    )
    (net (code "271") (name "UD11") (class "Default")
      (node (ref "U11A") (pin "15") (pinfunction "B4_15") (pintype "unspecified"))
      (node (ref "U13A") (pin "58") (pinfunction "D11_58") (pintype "unspecified"))
      (node (ref "U13D") (pin "15") (pinfunction "O3_15") (pintype "unspecified"))
      (node (ref "U14E") (pin "15") (pinfunction "B4_15") (pintype "unspecified"))
    )
    (net (code "272") (name "UD12") (class "Default")
      (node (ref "U13A") (pin "57") (pinfunction "D12_57") (pintype "unspecified"))
      (node (ref "U13D") (pin "16") (pinfunction "O4_16") (pintype "unspecified"))
      (node (ref "U14E") (pin "14") (pinfunction "B5_14") (pintype "unspecified"))
    )
    (net (code "273") (name "UD13") (class "Default")
      (node (ref "U13A") (pin "56") (pinfunction "D13_56") (pintype "unspecified"))
      (node (ref "U13D") (pin "17") (pinfunction "O5_17") (pintype "unspecified"))
      (node (ref "U14E") (pin "13") (pinfunction "B6_13") (pintype "unspecified"))
    )
    (net (code "274") (name "UD14") (class "Default")
      (node (ref "U11A") (pin "12") (pinfunction "B7_12") (pintype "unspecified"))
      (node (ref "U13A") (pin "55") (pinfunction "D14_55") (pintype "unspecified"))
      (node (ref "U13D") (pin "18") (pinfunction "O6_18") (pintype "unspecified"))
      (node (ref "U14E") (pin "12") (pinfunction "B7_12") (pintype "unspecified"))
    )
    (net (code "275") (name "UD15") (class "Default")
      (node (ref "U11A") (pin "11") (pinfunction "B8_11") (pintype "unspecified"))
      (node (ref "U13A") (pin "54") (pinfunction "D15_54") (pintype "unspecified"))
      (node (ref "U13D") (pin "19") (pinfunction "O7_19") (pintype "unspecified"))
      (node (ref "U14E") (pin "11") (pinfunction "B8_11") (pintype "unspecified"))
    )
    (net (code "276") (name "VA1") (class "Default")
      (node (ref "U6F") (pin "3") (pinfunction "1QA_3") (pintype "unspecified"))
      (node (ref "U7E") (pin "5") (pinfunction "1C1_5") (pintype "unspecified"))
    )
    (net (code "277") (name "VA2") (class "Default")
      (node (ref "U6F") (pin "4") (pinfunction "1QB_4") (pintype "unspecified"))
      (node (ref "U7E") (pin "11") (pinfunction "2C1_11") (pintype "unspecified"))
    )
    (net (code "278") (name "VA3") (class "Default")
      (node (ref "U6E") (pin "5") (pinfunction "1C1_5") (pintype "unspecified"))
      (node (ref "U6F") (pin "5") (pinfunction "1QC_5") (pintype "unspecified"))
    )
    (net (code "279") (name "VA4") (class "Default")
      (node (ref "U6E") (pin "11") (pinfunction "2C1_11") (pintype "unspecified"))
      (node (ref "U6F") (pin "13") (pinfunction "2ACLK_13") (pintype "unspecified"))
      (node (ref "U6F") (pin "6") (pinfunction "1QD_6") (pintype "unspecified"))
    )
    (net (code "280") (name "VA5") (class "Default")
      (node (ref "U5F") (pin "5") (pinfunction "1C1_5") (pintype "unspecified"))
      (node (ref "U6F") (pin "11") (pinfunction "2QA_11") (pintype "unspecified"))
    )
    (net (code "281") (name "VA6") (class "Default")
      (node (ref "U5F") (pin "11") (pinfunction "2C1_11") (pintype "unspecified"))
      (node (ref "U6F") (pin "10") (pinfunction "2QB_10") (pintype "unspecified"))
    )
    (net (code "282") (name "VA7") (class "Default")
      (node (ref "U6F") (pin "9") (pinfunction "2QC_9") (pintype "unspecified"))
      (node (ref "U8E") (pin "5") (pinfunction "1C1_5") (pintype "unspecified"))
    )
    (net (code "283") (name "VA8") (class "Default")
      (node (ref "U4A") (pin "1") (pinfunction "1A_1") (pintype "unspecified"))
      (node (ref "U4D") (pin "4") (pinfunction "2A_4") (pintype "unspecified"))
      (node (ref "U5E") (pin "1") (pinfunction "1ACLK_1") (pintype "unspecified"))
      (node (ref "U6F") (pin "8") (pinfunction "2QD_8") (pintype "unspecified"))
      (node (ref "U8E") (pin "11") (pinfunction "2C1_11") (pintype "unspecified"))
    )
    (net (code "284") (name "VA9B") (class "Default")
      (node (ref "CN1") (pin "70") (pinfunction "VA9B_70") (pintype "unspecified"))
      (node (ref "U8C") (pin "18") (pinfunction "1Y1_18") (pintype "unspecified"))
    )
    (net (code "285") (name "VA10B") (class "Default")
      (node (ref "CN1") (pin "69") (pinfunction "VA10B_69") (pintype "unspecified"))
      (node (ref "U8C") (pin "16") (pinfunction "1Y2_16") (pintype "unspecified"))
    )
    (net (code "286") (name "VA11") (class "Default")
      (node (ref "U4D") (pin "5") (pinfunction "2B_5") (pintype "unspecified"))
      (node (ref "U5E") (pin "5") (pinfunction "1QC_5") (pintype "unspecified"))
      (node (ref "U6E") (pin "3") (pinfunction "1C3_3") (pintype "unspecified"))
    )
    (net (code "287") (name "VA12") (class "Default")
      (node (ref "U5E") (pin "13") (pinfunction "2ACLK_13") (pintype "unspecified"))
      (node (ref "U5E") (pin "6") (pinfunction "1QD_6") (pintype "unspecified"))
      (node (ref "U6E") (pin "13") (pinfunction "2C3_13") (pintype "unspecified"))
    )
    (net (code "288") (name "VA13") (class "Default")
      (node (ref "U5E") (pin "11") (pinfunction "2QA_11") (pintype "unspecified"))
      (node (ref "U5F") (pin "3") (pinfunction "1C3_3") (pintype "unspecified"))
    )
    (net (code "289") (name "VA14") (class "Default")
      (node (ref "U5E") (pin "10") (pinfunction "2QB_10") (pintype "unspecified"))
      (node (ref "U5F") (pin "13") (pinfunction "2C3_13") (pintype "unspecified"))
    )
    (net (code "290") (name "VID") (class "Default")
      (node (ref "CN1") (pin "115") (pinfunction "VID_115") (pintype "unspecified"))
      (node (ref "U4D") (pin "8") (pinfunction "3Y_8") (pintype "unspecified"))
      (node (ref "U9E") (pin "11") (pinfunction "2A1_11") (pintype "unspecified"))
    )
    (net (code "291") (name "unconnected-(U2A-Pad1)") (class "Default")
      (node (ref "U2A") (pin "1") (pinfunction "1_1") (pintype "unspecified+no_connect"))
    )
    (net (code "292") (name "unconnected-(U2A-Pad2)") (class "Default")
      (node (ref "U2A") (pin "2") (pinfunction "2_2") (pintype "unspecified+no_connect"))
    )
    (net (code "293") (name "unconnected-(U2A-Pad3)") (class "Default")
      (node (ref "U2A") (pin "3") (pinfunction "3_3") (pintype "unspecified+no_connect"))
    )
    (net (code "294") (name "unconnected-(U2A-Pad4)") (class "Default")
      (node (ref "U2A") (pin "4") (pinfunction "4_4") (pintype "unspecified+no_connect"))
    )
    (net (code "295") (name "unconnected-(U2A-Pad5)") (class "Default")
      (node (ref "U2A") (pin "5") (pinfunction "5_5") (pintype "unspecified+no_connect"))
    )
    (net (code "296") (name "unconnected-(U2A-Pad6)") (class "Default")
      (node (ref "U2A") (pin "6") (pinfunction "6_6") (pintype "unspecified+no_connect"))
    )
    (net (code "297") (name "unconnected-(U2A-Pad7)") (class "Default")
      (node (ref "U2A") (pin "7") (pinfunction "7_7") (pintype "unspecified+no_connect"))
    )
    (net (code "298") (name "unconnected-(U2A-Pad8)") (class "Default")
      (node (ref "U2A") (pin "8") (pinfunction "8_8") (pintype "unspecified+no_connect"))
    )
    (net (code "299") (name "unconnected-(U2A-Pad9)") (class "Default")
      (node (ref "U2A") (pin "9") (pinfunction "9_9") (pintype "unspecified+no_connect"))
    )
    (net (code "300") (name "unconnected-(U2A-Pad10)") (class "Default")
      (node (ref "U2A") (pin "10") (pinfunction "10_10") (pintype "unspecified+no_connect"))
    )
    (net (code "301") (name "unconnected-(U2A-Pad11)") (class "Default")
      (node (ref "U2A") (pin "11") (pinfunction "11_11") (pintype "unspecified+no_connect"))
    )
    (net (code "302") (name "unconnected-(U2A-Pad12)") (class "Default")
      (node (ref "U2A") (pin "12") (pinfunction "12_12") (pintype "unspecified+no_connect"))
    )
    (net (code "303") (name "unconnected-(U2A-Pad13)") (class "Default")
      (node (ref "U2A") (pin "13") (pinfunction "13_13") (pintype "unspecified+no_connect"))
    )
    (net (code "304") (name "unconnected-(U2A-Pad14)") (class "Default")
      (node (ref "U2A") (pin "14") (pinfunction "14_14") (pintype "unspecified+no_connect"))
    )
    (net (code "305") (name "unconnected-(U2A-Pad15)") (class "Default")
      (node (ref "U2A") (pin "15") (pinfunction "15_15") (pintype "unspecified+no_connect"))
    )
    (net (code "306") (name "unconnected-(U2A-Pad16)") (class "Default")
      (node (ref "U2A") (pin "16") (pinfunction "16_16") (pintype "unspecified+no_connect"))
    )
    (net (code "307") (name "unconnected-(U3A-{slash}2Q-Pad9)") (class "Default")
      (node (ref "U3A") (pin "9") (pinfunction "/2Q_9") (pintype "unspecified+no_connect"))
    )
    (net (code "308") (name "unconnected-(U3E-{slash}1Q-Pad7)") (class "Default")
      (node (ref "U3E") (pin "7") (pinfunction "/1Q_7") (pintype "unspecified+no_connect"))
    )
    (net (code "309") (name "unconnected-(U3E-{slash}2Q-Pad9)") (class "Default")
      (node (ref "U3E") (pin "9") (pinfunction "/2Q_9") (pintype "unspecified+no_connect"))
    )
    (net (code "310") (name "unconnected-(U3F-Pad1)") (class "Default")
      (node (ref "U3F") (pin "1") (pinfunction "1_1") (pintype "unspecified+no_connect"))
    )
    (net (code "311") (name "unconnected-(U3F-Pad2)") (class "Default")
      (node (ref "U3F") (pin "2") (pinfunction "2_2") (pintype "unspecified+no_connect"))
    )
    (net (code "312") (name "unconnected-(U3F-Pad3)") (class "Default")
      (node (ref "U3F") (pin "3") (pinfunction "3_3") (pintype "unspecified+no_connect"))
    )
    (net (code "313") (name "unconnected-(U3F-Pad4)") (class "Default")
      (node (ref "U3F") (pin "4") (pinfunction "4_4") (pintype "unspecified+no_connect"))
    )
    (net (code "314") (name "unconnected-(U3F-Pad5)") (class "Default")
      (node (ref "U3F") (pin "5") (pinfunction "5_5") (pintype "unspecified+no_connect"))
    )
    (net (code "315") (name "unconnected-(U3F-Pad6)") (class "Default")
      (node (ref "U3F") (pin "6") (pinfunction "6_6") (pintype "unspecified+no_connect"))
    )
    (net (code "316") (name "unconnected-(U3F-Pad7)") (class "Default")
      (node (ref "U3F") (pin "7") (pinfunction "7_7") (pintype "unspecified+no_connect"))
    )
    (net (code "317") (name "unconnected-(U3F-Pad8)") (class "Default")
      (node (ref "U3F") (pin "8") (pinfunction "8_8") (pintype "unspecified+no_connect"))
    )
    (net (code "318") (name "unconnected-(U3F-Pad9)") (class "Default")
      (node (ref "U3F") (pin "9") (pinfunction "9_9") (pintype "unspecified+no_connect"))
    )
    (net (code "319") (name "unconnected-(U3F-Pad10)") (class "Default")
      (node (ref "U3F") (pin "10") (pinfunction "10_10") (pintype "unspecified+no_connect"))
    )
    (net (code "320") (name "unconnected-(U3F-Pad11)") (class "Default")
      (node (ref "U3F") (pin "11") (pinfunction "11_11") (pintype "unspecified+no_connect"))
    )
    (net (code "321") (name "unconnected-(U3F-Pad12)") (class "Default")
      (node (ref "U3F") (pin "12") (pinfunction "12_12") (pintype "unspecified+no_connect"))
    )
    (net (code "322") (name "unconnected-(U3F-Pad13)") (class "Default")
      (node (ref "U3F") (pin "13") (pinfunction "13_13") (pintype "unspecified+no_connect"))
    )
    (net (code "323") (name "unconnected-(U3F-Pad14)") (class "Default")
      (node (ref "U3F") (pin "14") (pinfunction "14_14") (pintype "unspecified+no_connect"))
    )
    (net (code "324") (name "unconnected-(U3F-Pad15)") (class "Default")
      (node (ref "U3F") (pin "15") (pinfunction "15_15") (pintype "unspecified+no_connect"))
    )
    (net (code "325") (name "unconnected-(U3F-Pad16)") (class "Default")
      (node (ref "U3F") (pin "16") (pinfunction "16_16") (pintype "unspecified+no_connect"))
    )
    (net (code "326") (name "unconnected-(U3F-Pad17)") (class "Default")
      (node (ref "U3F") (pin "17") (pinfunction "17_17") (pintype "unspecified+no_connect"))
    )
    (net (code "327") (name "unconnected-(U3F-Pad18)") (class "Default")
      (node (ref "U3F") (pin "18") (pinfunction "18_18") (pintype "unspecified+no_connect"))
    )
    (net (code "328") (name "unconnected-(U3F-Pad19)") (class "Default")
      (node (ref "U3F") (pin "19") (pinfunction "19_19") (pintype "unspecified+no_connect"))
    )
    (net (code "329") (name "unconnected-(U3F-Pad20)") (class "Default")
      (node (ref "U3F") (pin "20") (pinfunction "20_20") (pintype "unspecified+no_connect"))
    )
    (net (code "330") (name "unconnected-(U4A-3Y-Pad8)") (class "Default")
      (node (ref "U4A") (pin "8") (pinfunction "3Y_8") (pintype "unspecified+no_connect"))
    )
    (net (code "331") (name "unconnected-(U5D-{slash}1Q-Pad7)") (class "Default")
      (node (ref "U5D") (pin "7") (pinfunction "/1Q_7") (pintype "unspecified+no_connect"))
    )
    (net (code "332") (name "unconnected-(U5D-{slash}2Q-Pad9)") (class "Default")
      (node (ref "U5D") (pin "9") (pinfunction "/2Q_9") (pintype "unspecified+no_connect"))
    )
    (net (code "333") (name "unconnected-(U5E-2QD-Pad8)") (class "Default")
      (node (ref "U5E") (pin "8") (pinfunction "2QD_8") (pintype "unspecified+no_connect"))
    )
    (net (code "334") (name "unconnected-(U6B-8Q-Pad19)") (class "Default")
      (node (ref "U6B") (pin "19") (pinfunction "8Q_19") (pintype "unspecified+no_connect"))
    )
    (net (code "335") (name "unconnected-(U7A-2A-Pad4)") (class "Default")
      (node (ref "U7A") (pin "4") (pinfunction "2A_4") (pintype "unspecified"))
    )
    (net (code "336") (name "unconnected-(U7A-2B-Pad5)") (class "Default")
      (node (ref "U7A") (pin "5") (pinfunction "2B_5") (pintype "unspecified"))
    )
    (net (code "337") (name "unconnected-(U7A-2Y-Pad6)") (class "Default")
      (node (ref "U7A") (pin "6") (pinfunction "2Y_6") (pintype "unspecified"))
    )
    (net (code "338") (name "unconnected-(U7B-2QC-Pad9)") (class "Default")
      (node (ref "U7B") (pin "9") (pinfunction "2QC_9") (pintype "unspecified+no_connect"))
    )
    (net (code "339") (name "unconnected-(U7B-2QD-Pad8)") (class "Default")
      (node (ref "U7B") (pin "8") (pinfunction "2QD_8") (pintype "unspecified+no_connect"))
    )
    (net (code "340") (name "unconnected-(U10B-C4-Pad9)") (class "Default")
      (node (ref "U10B") (pin "9") (pinfunction "C4_9") (pintype "unspecified+no_connect"))
    )
    (net (code "341") (name "unconnected-(U11A-A5-Pad6)") (class "Default")
      (node (ref "U11A") (pin "6") (pinfunction "A5_6") (pintype "unspecified+no_connect"))
    )
    (net (code "342") (name "unconnected-(U11A-A6-Pad7)") (class "Default")
      (node (ref "U11A") (pin "7") (pinfunction "A6_7") (pintype "unspecified+no_connect"))
    )
    (net (code "343") (name "unconnected-(U11A-A7-Pad8)") (class "Default")
      (node (ref "U11A") (pin "8") (pinfunction "A7_8") (pintype "unspecified+no_connect"))
    )
    (net (code "344") (name "unconnected-(U11A-B5-Pad14)") (class "Default")
      (node (ref "U11A") (pin "14") (pinfunction "B5_14") (pintype "unspecified+no_connect"))
    )
    (net (code "345") (name "unconnected-(U11A-B6-Pad13)") (class "Default")
      (node (ref "U11A") (pin "13") (pinfunction "B6_13") (pintype "unspecified+no_connect"))
    )
    (net (code "346") (name "unconnected-(U11C-1Q-Pad2)") (class "Default")
      (node (ref "U11C") (pin "2") (pinfunction "1Q_2") (pintype "unspecified+no_connect"))
    )
    (net (code "347") (name "unconnected-(U11C-2Q-Pad5)") (class "Default")
      (node (ref "U11C") (pin "5") (pinfunction "2Q_5") (pintype "unspecified+no_connect"))
    )
    (net (code "348") (name "unconnected-(U14F-1Y2-Pad6)") (class "Default")
      (node (ref "U14F") (pin "6") (pinfunction "1Y2_6") (pintype "unspecified+no_connect"))
    )
    (net (code "349") (name "unconnected-(U14F-1Y3-Pad7)") (class "Default")
      (node (ref "U14F") (pin "7") (pinfunction "1Y3_7") (pintype "unspecified+no_connect"))
    )
    (net (code "350") (name "unconnected-(U15B-C1-Pad3)") (class "Default")
      (node (ref "U15B") (pin "3") (pinfunction "C1_3") (pintype "unspecified+no_connect"))
    )
    (net (code "351") (name "unconnected-(U15B-C2-Pad11)") (class "Default")
      (node (ref "U15B") (pin "11") (pinfunction "C2_11") (pintype "unspecified+no_connect"))
    )
    (net (code "352") (name "unconnected-(U15B-D1-Pad1)") (class "Default")
      (node (ref "U15B") (pin "1") (pinfunction "D1_1") (pintype "unspecified+no_connect"))
    )
    (net (code "353") (name "unconnected-(U15B-D2-Pad13)") (class "Default")
      (node (ref "U15B") (pin "13") (pinfunction "D2_13") (pintype "unspecified+no_connect"))
    )
    (net (code "354") (name "{slash}BERR") (class "Default")
      (node (ref "U13A") (pin "22") (pinfunction "BERR_22") (pintype "unspecified"))
      (node (ref "U3B") (pin "9") (pinfunction "/2Q_9") (pintype "unspecified"))
    )
    (net (code "355") (name "{slash}BG") (class "Default")
      (node (ref "CN1") (pin "26") (pinfunction "/BG_26") (pintype "unspecified"))
      (node (ref "U13A") (pin "11") (pinfunction "BG_11") (pintype "unspecified"))
    )
    (net (code "356") (name "{slash}BR") (class "Default")
      (node (ref "CN1") (pin "25") (pinfunction "/BR_25") (pintype "unspecified"))
      (node (ref "RP2") (pin "12") (pinfunction "+5V_12") (pintype "unspecified"))
      (node (ref "U13A") (pin "13") (pinfunction "BR_13") (pintype "unspecified"))
    )
    (net (code "357") (name "{slash}BUST") (class "Default")
      (node (ref "U15B") (pin "9") (pinfunction "Q2_9") (pintype "unspecified"))
      (node (ref "U3B") (pin "11") (pinfunction "2PR_11") (pintype "unspecified"))
      (node (ref "U5C") (pin "14") (pinfunction "4R_14") (pintype "unspecified"))
    )
    (net (code "358") (name "{slash}CAS") (class "Default")
      (node (ref "CN1") (pin "108") (pinfunction "/CAS_108") (pintype "unspecified"))
      (node (ref "U3C") (pin "10") (pinfunction "2Q_10") (pintype "unspecified"))
    )
    (net (code "359") (name "{slash}CDACK") (class "Default")
      (node (ref "U13A") (pin "10") (pinfunction "DTACK_10") (pintype "unspecified"))
      (node (ref "U6A") (pin "10") (pinfunction "3Y_10") (pintype "unspecified"))
    )
    (net (code "360") (name "{slash}CMUX") (class "Default")
      (node (ref "U15F") (pin "1") (pinfunction "1A_1") (pintype "unspecified"))
      (node (ref "U4B") (pin "9") (pinfunction "/2Q_9") (pintype "unspecified"))
      (node (ref "U5F") (pin "14") (pinfunction "A_14") (pintype "unspecified"))
      (node (ref "U6E") (pin "14") (pinfunction "A_14") (pintype "unspecified"))
      (node (ref "U7E") (pin "14") (pinfunction "A_14") (pintype "unspecified"))
      (node (ref "U8E") (pin "14") (pinfunction "A_14") (pintype "unspecified"))
    )
    (net (code "361") (name "{slash}CSYNC") (class "Default")
      (node (ref "CN1") (pin "67") (pinfunction "/CSYNC_67") (pintype "unspecified"))
      (node (ref "U6B") (pin "12") (pinfunction "5Q_12") (pintype "unspecified"))
      (node (ref "U9E") (pin "13") (pinfunction "2A2_13") (pintype "unspecified"))
    )
    (net (code "362") (name "{slash}DBON") (class "Default")
      (node (ref "U14E") (pin "19") (pinfunction "G_19") (pintype "unspecified"))
      (node (ref "U15E") (pin "19") (pinfunction "G_19") (pintype "unspecified"))
      (node (ref "U15F") (pin "6") (pinfunction "/2Y_6") (pintype "unspecified"))
    )
    (net (code "363") (name "{slash}HDER") (class "Default")
      (node (ref "CN1") (pin "112") (pinfunction "/HDER_112") (pintype "unspecified"))
      (node (ref "R7") (pin "1") (pinfunction "1_1") (pintype "unspecified"))
      (node (ref "U7A") (pin "11") (pinfunction "4Y_11") (pintype "unspecified"))
    )
    (net (code "364") (name "{slash}HDMSK") (class "Default")
      (node (ref "C43") (pin "2") (pinfunction "2_2") (pintype "unspecified"))
      (node (ref "U4E") (pin "12") (pinfunction "Q7_12") (pintype "unspecified"))
      (node (ref "U5C") (pin "11") (pinfunction "3S1_11") (pintype "unspecified"))
      (node (ref "U5C") (pin "12") (pinfunction "3S2_12") (pintype "unspecified"))
    )
    (net (code "365") (name "{slash}HPIR") (class "Default")
      (node (ref "U10C") (pin "12") (pinfunction "1Y_12") (pintype "unspecified"))
      (node (ref "U12F") (pin "4") (pinfunction "7_4") (pintype "unspecified"))
    )
    (net (code "366") (name "{slash}HSYNC") (class "Default")
      (node (ref "CN1") (pin "111") (pinfunction "/HSYNC_111") (pintype "unspecified"))
      (node (ref "U6B") (pin "16") (pinfunction "7Q_16") (pintype "unspecified"))
    )
    (net (code "367") (name "{slash}IAK0") (class "Default")
      (node (ref "CN1") (pin "8") (pinfunction "/IAK0_8") (pintype "unspecified"))
      (node (ref "U4F") (pin "6") (pinfunction "1Y1_6") (pintype "unspecified"))
    )
    (net (code "368") (name "{slash}IAK1") (class "Default")
      (node (ref "CN1") (pin "10") (pinfunction "/IAK1_10") (pintype "unspecified"))
      (node (ref "U4F") (pin "7") (pinfunction "1Y0_7") (pintype "unspecified"))
    )
    (net (code "369") (name "{slash}IAK2") (class "Default")
      (node (ref "CN1") (pin "12") (pinfunction "/IAK2_12") (pintype "unspecified"))
      (node (ref "U4F") (pin "12") (pinfunction "2Y3_12") (pintype "unspecified"))
    )
    (net (code "370") (name "{slash}INITIO") (class "Default")
      (node (ref "CN1") (pin "68") (pinfunction "/INITIO_68") (pintype "unspecified"))
      (node (ref "U13F") (pin "9") (pinfunction "Y6_9") (pintype "unspecified"))
    )
    (net (code "371") (name "{slash}INT0") (class "Default")
      (node (ref "CN1") (pin "7") (pinfunction "/INT0_7") (pintype "unspecified"))
      (node (ref "RP2") (pin "7") (pinfunction "+5V_7") (pintype "unspecified"))
      (node (ref "U12F") (pin "2") (pinfunction "5_2") (pintype "unspecified"))
    )
    (net (code "372") (name "{slash}INT1") (class "Default")
      (node (ref "CN1") (pin "9") (pinfunction "/INT1_9") (pintype "unspecified"))
      (node (ref "RP2") (pin "8") (pinfunction "+5V_8") (pintype "unspecified"))
      (node (ref "U12F") (pin "1") (pinfunction "4_1") (pintype "unspecified"))
    )
    (net (code "373") (name "{slash}INT2") (class "Default")
      (node (ref "CN1") (pin "11") (pinfunction "/INT2_11") (pintype "unspecified"))
      (node (ref "RP2") (pin "9") (pinfunction "+5V_9") (pintype "unspecified"))
      (node (ref "U12F") (pin "13") (pinfunction "3_13") (pintype "unspecified"))
    )
    (net (code "374") (name "{slash}IO") (class "Default")
      (node (ref "RP1") (pin "1") (pinfunction "+5V_1") (pintype "unspecified"))
      (node (ref "U10A") (pin "12") (pinfunction "VO3_12") (pintype "unspecified"))
      (node (ref "U10B") (pin "14") (pinfunction "A3_14") (pintype "unspecified"))
      (node (ref "U11A") (pin "4") (pinfunction "A3_4") (pintype "unspecified"))
      (node (ref "U3D") (pin "2") (pinfunction "1B_2") (pintype "unspecified"))
    )
    (net (code "375") (name "{slash}IOCY") (class "Default")
      (node (ref "U4B") (pin "7") (pinfunction "/1Q_7") (pintype "unspecified"))
      (node (ref "U5A") (pin "10") (pinfunction "3B_10") (pintype "unspecified"))
    )
    (net (code "376") (name "{slash}IOIR") (class "Default")
      (node (ref "CN1") (pin "15") (pinfunction "/IOIR_15") (pintype "unspecified"))
      (node (ref "RP2") (pin "10") (pinfunction "+5V_10") (pintype "unspecified"))
      (node (ref "U12F") (pin "10") (pinfunction "0_10") (pintype "unspecified"))
      (node (ref "U12F") (pin "11") (pinfunction "1_11") (pintype "unspecified"))
      (node (ref "U2E") (pin "10") (pinfunction "5Y_10") (pintype "unspecified"))
    )
    (net (code "377") (name "{slash}KBIR") (class "Default")
      (node (ref "CN1") (pin "14") (pinfunction "/KBIR_14") (pintype "unspecified"))
      (node (ref "RP2") (pin "14") (pinfunction "+5V_14") (pintype "unspecified"))
      (node (ref "U12F") (pin "12") (pinfunction "2_12") (pintype "unspecified"))
    )
    (net (code "378") (name "{slash}LDMA") (class "Default")
      (node (ref "CN1") (pin "23") (pinfunction "/LDMA_23") (pintype "unspecified"))
      (node (ref "R11") (pin "2") (pinfunction "2_2") (pintype "unspecified"))
      (node (ref "U7D") (pin "11") (pinfunction "G_11") (pintype "unspecified"))
    )
    (net (code "379") (name "{slash}MALE") (class "Default")
      (node (ref "U11D") (pin "11") (pinfunction "G_11") (pintype "unspecified"))
      (node (ref "U2B") (pin "10") (pinfunction "2Q_10") (pintype "unspecified"))
      (node (ref "U6D") (pin "9") (pinfunction "3A_9") (pintype "unspecified"))
    )
    (net (code "380") (name "{slash}MDEN") (class "Default")
      (node (ref "U11F") (pin "19") (pinfunction "G_19") (pintype "unspecified"))
      (node (ref "U5A") (pin "8") (pinfunction "3Y_8") (pintype "unspecified"))
      (node (ref "U9F") (pin "19") (pinfunction "G_19") (pintype "unspecified"))
    )
    (net (code "381") (name "{slash}MEM") (class "Default")
      (node (ref "RP1") (pin "15") (pinfunction "+5V_15") (pintype "unspecified"))
      (node (ref "U10A") (pin "11") (pinfunction "VO4_11") (pintype "unspecified"))
      (node (ref "U10B") (pin "12") (pinfunction "A4_12") (pintype "unspecified"))
      (node (ref "U11A") (pin "5") (pinfunction "A4_5") (pintype "unspecified"))
      (node (ref "U5B") (pin "2") (pinfunction "1A_2") (pintype "unspecified"))
    )
    (net (code "382") (name "{slash}RAS") (class "Default")
      (node (ref "CN1") (pin "109") (pinfunction "/RAS_109") (pintype "unspecified"))
      (node (ref "U3C") (pin "6") (pinfunction "1Q_6") (pintype "unspecified"))
    )
    (net (code "383") (name "{slash}RBES") (class "Default")
      (node (ref "U14F") (pin "9") (pinfunction "2Y3_9") (pintype "unspecified"))
      (node (ref "U9E") (pin "1") (pinfunction "1G_1") (pintype "unspecified"))
      (node (ref "U9E") (pin "19") (pinfunction "2G_19") (pintype "unspecified"))
    )
    (net (code "384") (name "{slash}RESET") (class "Default")
      (node (ref "CN1") (pin "21") (pinfunction "/RESET_21") (pintype "unspecified"))
      (node (ref "R12") (pin "1") (pinfunction "1_1") (pintype "unspecified"))
      (node (ref "U2E") (pin "4") (pinfunction "2Y_4") (pintype "unspecified"))
    )
    (net (code "385") (name "{slash}RMEA") (class "Default")
      (node (ref "U11E") (pin "1") (pinfunction "/OE_1") (pintype "unspecified"))
      (node (ref "U13E") (pin "1") (pinfunction "/OE_1") (pintype "unspecified"))
      (node (ref "U14F") (pin "10") (pinfunction "2Y2_10") (pintype "unspecified"))
      (node (ref "U5C") (pin "15") (pinfunction "4S_15") (pintype "unspecified"))
    )
    (net (code "386") (name "{slash}RO") (class "Default")
      (node (ref "RP1") (pin "14") (pinfunction "+5V_14") (pintype "unspecified"))
      (node (ref "U10A") (pin "13") (pinfunction "VO2_13") (pintype "unspecified"))
      (node (ref "U10B") (pin "3") (pinfunction "A2_3") (pintype "unspecified"))
      (node (ref "U11A") (pin "3") (pinfunction "A2_3") (pintype "unspecified"))
      (node (ref "U1B") (pin "11") (pinfunction "5A_11") (pintype "unspecified"))
      (node (ref "U2D") (pin "2") (pinfunction "B1_2") (pintype "unspecified"))
    )
    (net (code "387") (name "{slash}ROM") (class "Default")
      (node (ref "U13D") (pin "22") (pinfunction "OE_22") (pintype "unspecified"))
      (node (ref "U14D") (pin "22") (pinfunction "OE_22") (pintype "unspecified"))
      (node (ref "U14F") (pin "4") (pinfunction "1Y0_4") (pintype "unspecified"))
    )
    (net (code "388") (name "{slash}RSIR") (class "Default")
      (node (ref "CN1") (pin "13") (pinfunction "/RSIR_13") (pintype "unspecified"))
      (node (ref "RP2") (pin "13") (pinfunction "+5V_13") (pintype "unspecified"))
      (node (ref "U12F") (pin "3") (pinfunction "6_3") (pintype "unspecified"))
    )
    (net (code "389") (name "{slash}RSTSW") (class "Default")
      (node (ref "C8") (pin "1") (pinfunction "1_1") (pintype "unspecified"))
      (node (ref "CN1") (pin "101") (pinfunction "/RSTSW_101") (pintype "unspecified"))
      (node (ref "CR1") (pin "1") (pinfunction "1_1") (pintype "unspecified"))
      (node (ref "R2") (pin "1") (pinfunction "1_1") (pintype "unspecified"))
      (node (ref "U15B") (pin "2") (pinfunction "TH1_2") (pintype "unspecified"))
      (node (ref "U15B") (pin "6") (pinfunction "TR1_6") (pintype "unspecified"))
    )
    (net (code "390") (name "{slash}SFER") (class "Default")
      (node (ref "CN1") (pin "114") (pinfunction "/SFER_114") (pintype "unspecified"))
      (node (ref "R4") (pin "1") (pinfunction "1_1") (pintype "unspecified"))
      (node (ref "U7A") (pin "8") (pinfunction "3Y_8") (pintype "unspecified"))
    )
    (net (code "391") (name "{slash}SFMSK") (class "Default")
      (node (ref "U4E") (pin "10") (pinfunction "Q5_10") (pintype "unspecified"))
      (node (ref "U5C") (pin "2") (pinfunction "1S1_2") (pintype "unspecified"))
      (node (ref "U5C") (pin "3") (pinfunction "1S2_3") (pintype "unspecified"))
    )
    (net (code "392") (name "{slash}SH0") (class "Default")
      (node (ref "CN1") (pin "2") (pinfunction "/SL0_2") (pintype "unspecified"))
      (node (ref "U13F") (pin "14") (pinfunction "Y1_14") (pintype "unspecified"))
    )
    (net (code "393") (name "{slash}SH1") (class "Default")
      (node (ref "CN1") (pin "4") (pinfunction "/SH1_4") (pintype "unspecified"))
      (node (ref "U13F") (pin "12") (pinfunction "Y3_12") (pintype "unspecified"))
    )
    (net (code "394") (name "{slash}SH2") (class "Default")
      (node (ref "CN1") (pin "6") (pinfunction "/SH2_6") (pintype "unspecified"))
      (node (ref "U13F") (pin "10") (pinfunction "Y5_10") (pintype "unspecified"))
    )
    (net (code "395") (name "{slash}SL0") (class "Default")
      (node (ref "CN1") (pin "1") (pinfunction "/SH0_1") (pintype "unspecified"))
      (node (ref "U13F") (pin "15") (pinfunction "Y0_15") (pintype "unspecified"))
    )
    (net (code "396") (name "{slash}SL1") (class "Default")
      (node (ref "CN1") (pin "3") (pinfunction "/SL1_3") (pintype "unspecified"))
      (node (ref "U13F") (pin "13") (pinfunction "Y2_13") (pintype "unspecified"))
    )
    (net (code "397") (name "{slash}SL2") (class "Default")
      (node (ref "CN1") (pin "5") (pinfunction "/SL2_5") (pintype "unspecified"))
      (node (ref "U13F") (pin "11") (pinfunction "Y4_11") (pintype "unspecified"))
    )
    (net (code "398") (name "{slash}START") (class "Default")
      (node (ref "U1A") (pin "5") (pinfunction "B2_5") (pintype "unspecified"))
      (node (ref "U4E") (pin "9") (pinfunction "Q4_9") (pintype "unspecified"))
    )
    (net (code "399") (name "{slash}STK") (class "Default")
      (node (ref "RP1") (pin "9") (pinfunction "+5V_9") (pintype "unspecified"))
      (node (ref "U10A") (pin "14") (pinfunction "VO1_14") (pintype "unspecified"))
      (node (ref "U10B") (pin "5") (pinfunction "A1_5") (pintype "unspecified"))
      (node (ref "U11A") (pin "2") (pinfunction "A1_2") (pintype "unspecified"))
      (node (ref "U4D") (pin "2") (pinfunction "1B_2") (pintype "unspecified"))
      (node (ref "U5B") (pin "9") (pinfunction "3B_9") (pintype "unspecified"))
    )
    (net (code "400") (name "{slash}T0") (class "Default")
      (node (ref "U1D") (pin "15") (pinfunction "Y0_15") (pintype "unspecified"))
      (node (ref "U3C") (pin "3") (pinfunction "1K_3") (pintype "unspecified"))
    )
    (net (code "401") (name "{slash}T1") (class "Default")
      (node (ref "U1D") (pin "14") (pinfunction "Y1_14") (pintype "unspecified"))
    )
    (net (code "402") (name "{slash}T2") (class "Default")
      (node (ref "U1D") (pin "13") (pinfunction "Y2_13") (pintype "unspecified"))
      (node (ref "U3C") (pin "13") (pinfunction "2K_13") (pintype "unspecified"))
      (node (ref "U3D") (pin "10") (pinfunction "2D_10") (pintype "unspecified"))
      (node (ref "U3D") (pin "12") (pinfunction "1D_12") (pintype "unspecified"))
    )
    (net (code "403") (name "{slash}T3") (class "Default")
      (node (ref "U1D") (pin "12") (pinfunction "Y3_12") (pintype "unspecified"))
      (node (ref "U2C") (pin "12") (pinfunction "1D_12") (pintype "unspecified"))
    )
    (net (code "404") (name "{slash}T4") (class "Default")
      (node (ref "U1D") (pin "11") (pinfunction "Y4_11") (pintype "unspecified"))
      (node (ref "U2D") (pin "4") (pinfunction "A2_4") (pintype "unspecified"))
      (node (ref "U5D") (pin "3") (pinfunction "1K_3") (pintype "unspecified"))
    )
    (net (code "405") (name "{slash}T7") (class "Default")
      (node (ref "U1D") (pin "7") (pinfunction "Y7_7") (pintype "unspecified"))
    )
    (net (code "406") (name "{slash}VAL") (class "Default")
      (node (ref "U14F") (pin "11") (pinfunction "2Y1_11") (pintype "unspecified"))
      (node (ref "U15F") (pin "12") (pinfunction "4A_12") (pintype "unspecified"))
      (node (ref "U15F") (pin "13") (pinfunction "4B_13") (pintype "unspecified"))
    )
    (net (code "407") (name "{slash}VMA") (class "Default")
      (node (ref "CN1") (pin "59") (pinfunction "/VMA_59") (pintype "unspecified"))
      (node (ref "U8C") (pin "12") (pinfunction "1Y4_12") (pintype "unspecified"))
    )
    (net (code "408") (name "{slash}VPA") (class "Default")
      (node (ref "CN1") (pin "60") (pinfunction "/VPA_60") (pintype "unspecified"))
      (node (ref "RP1") (pin "13") (pinfunction "+5V_13") (pintype "unspecified"))
      (node (ref "U13A") (pin "21") (pinfunction "VPA_21") (pintype "unspecified"))
      (node (ref "U4F") (pin "10") (pinfunction "2Y1_10") (pintype "unspecified"))
      (node (ref "U4F") (pin "11") (pinfunction "2Y2_11") (pintype "unspecified"))
      (node (ref "U4F") (pin "4") (pinfunction "1Y3_4") (pintype "unspecified"))
      (node (ref "U4F") (pin "5") (pinfunction "1Y2_5") (pintype "unspecified"))
      (node (ref "U4F") (pin "9") (pinfunction "2Y0_9") (pintype "unspecified"))
    )
    (net (code "409") (name "{slash}VSIR") (class "Default")
      (node (ref "U5C") (pin "5") (pinfunction "2R_5") (pintype "unspecified"))
      (node (ref "U6D") (pin "3") (pinfunction "/1Y_3") (pintype "unspecified"))
    )
    (net (code "410") (name "{slash}VSYNC") (class "Default")
      (node (ref "CN1") (pin "113") (pinfunction "/VSYNC_113") (pintype "unspecified"))
      (node (ref "U6B") (pin "5") (pinfunction "2Q_5") (pintype "unspecified"))
    )
    (net (code "411") (name "{slash}VTIR") (class "Default")
      (node (ref "U2E") (pin "11") (pinfunction "5A_11") (pintype "unspecified"))
      (node (ref "U5C") (pin "7") (pinfunction "2Q_7") (pintype "unspecified"))
      (node (ref "U9E") (pin "6") (pinfunction "1A3_6") (pintype "unspecified"))
    )
    (net (code "412") (name "{slash}VTMSK") (class "Default")
      (node (ref "U4E") (pin "11") (pinfunction "Q6_11") (pintype "unspecified"))
      (node (ref "U5C") (pin "6") (pinfunction "2S_6") (pintype "unspecified"))
    )
  )
)
